# BreakOutBoard_Cyclone.net
KiCad netlist of a schematic drawn in Altium Designer
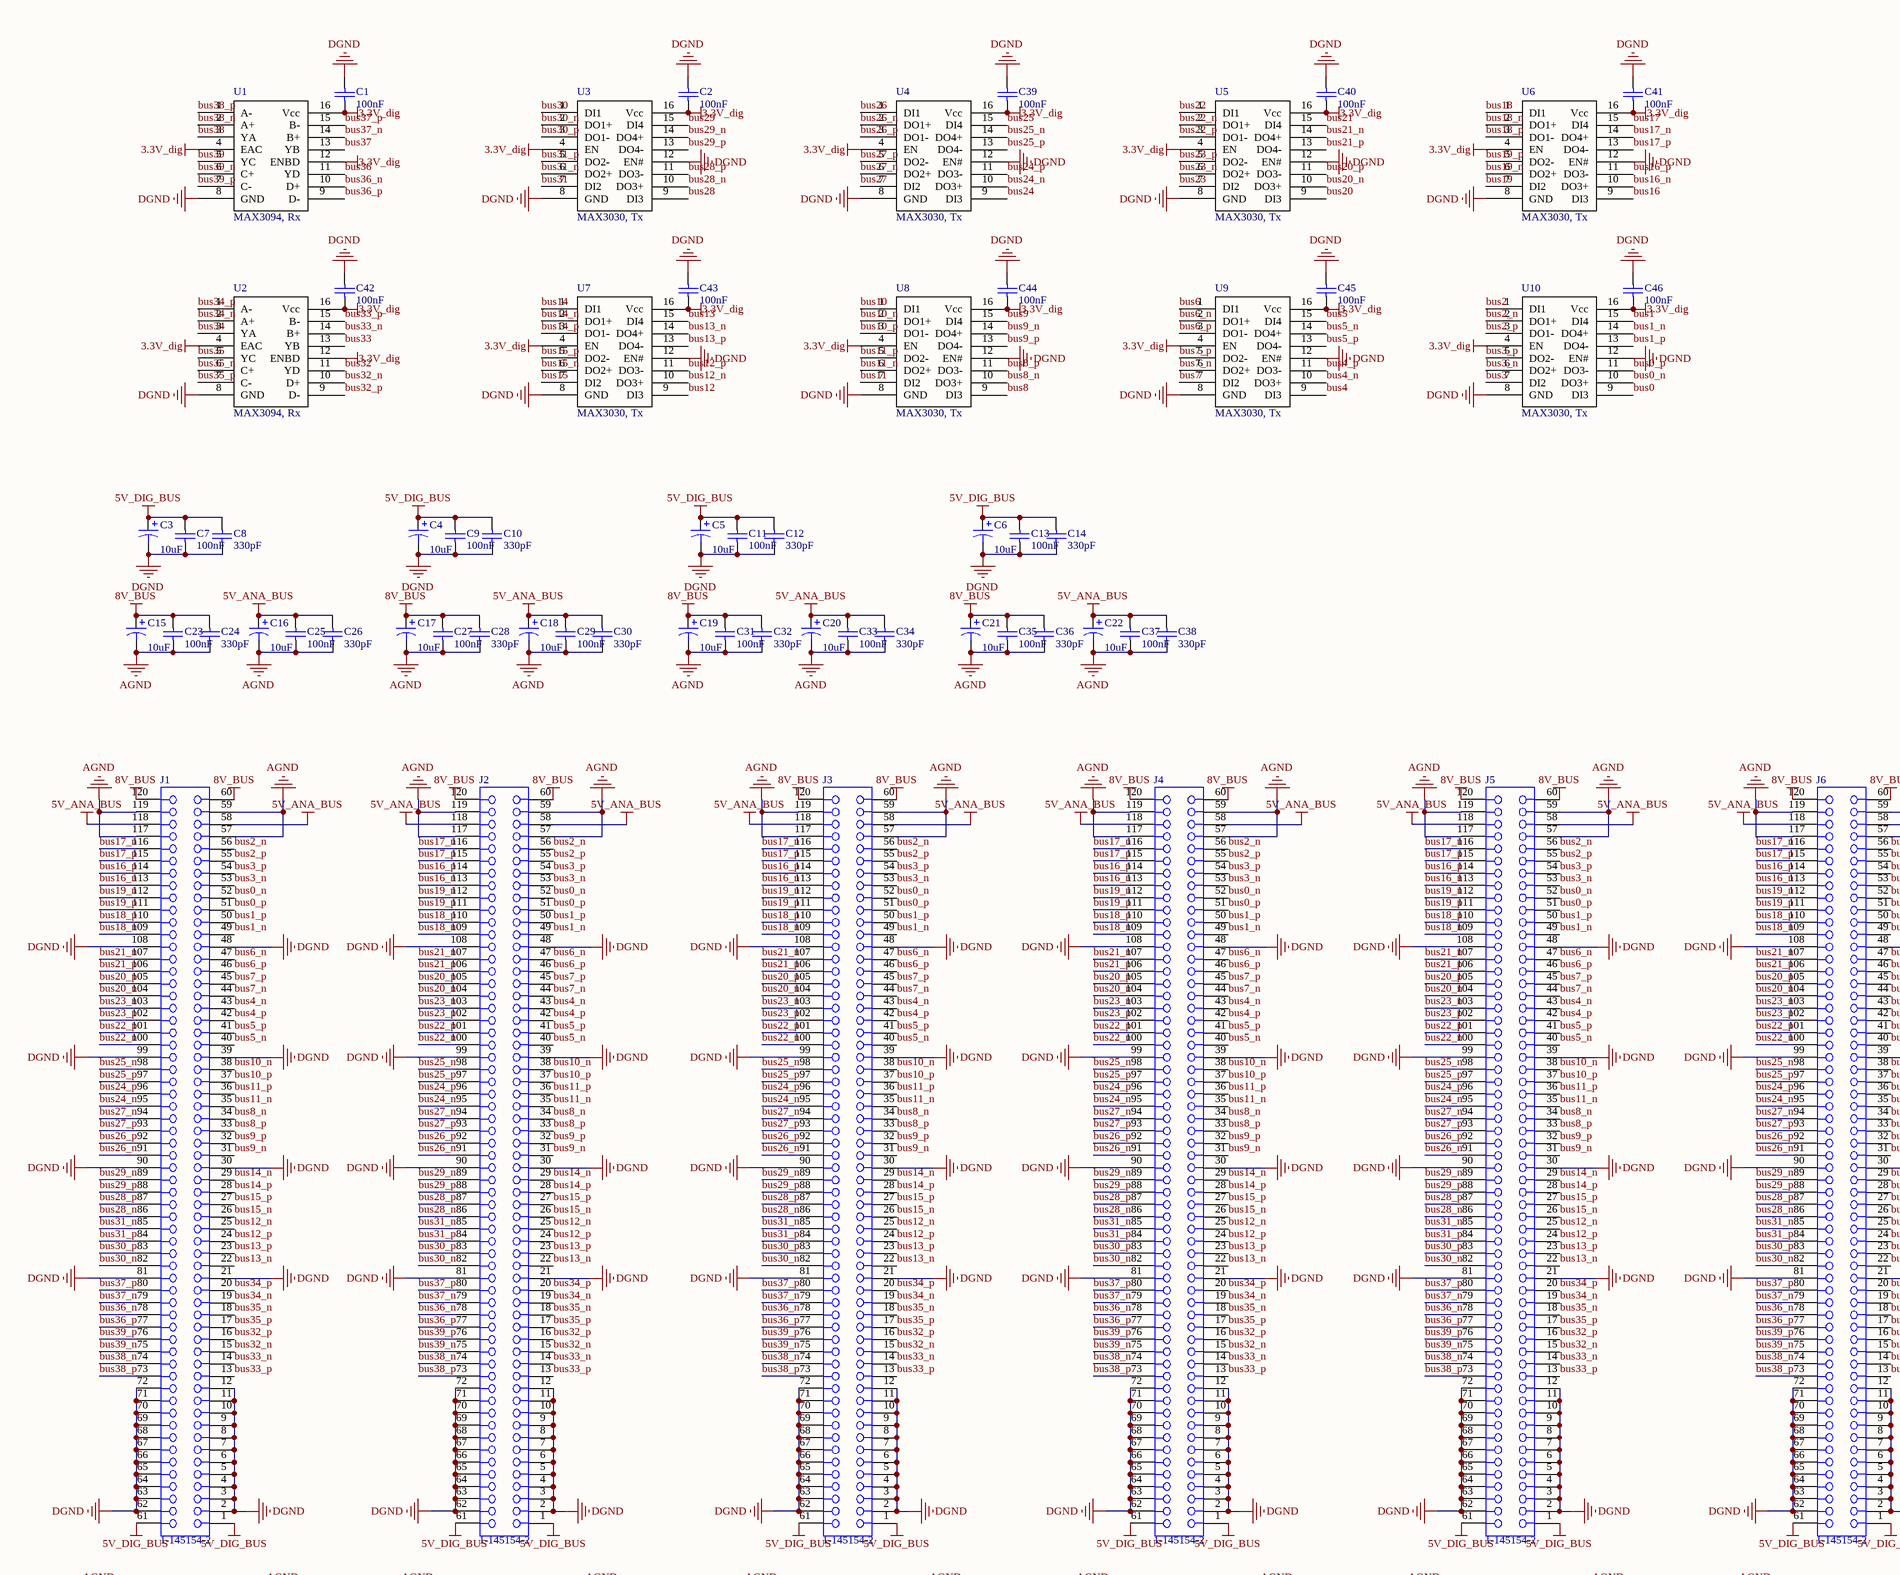
[diagram p0: BreakOutBoard_Cyclone.SchDoc, top left]
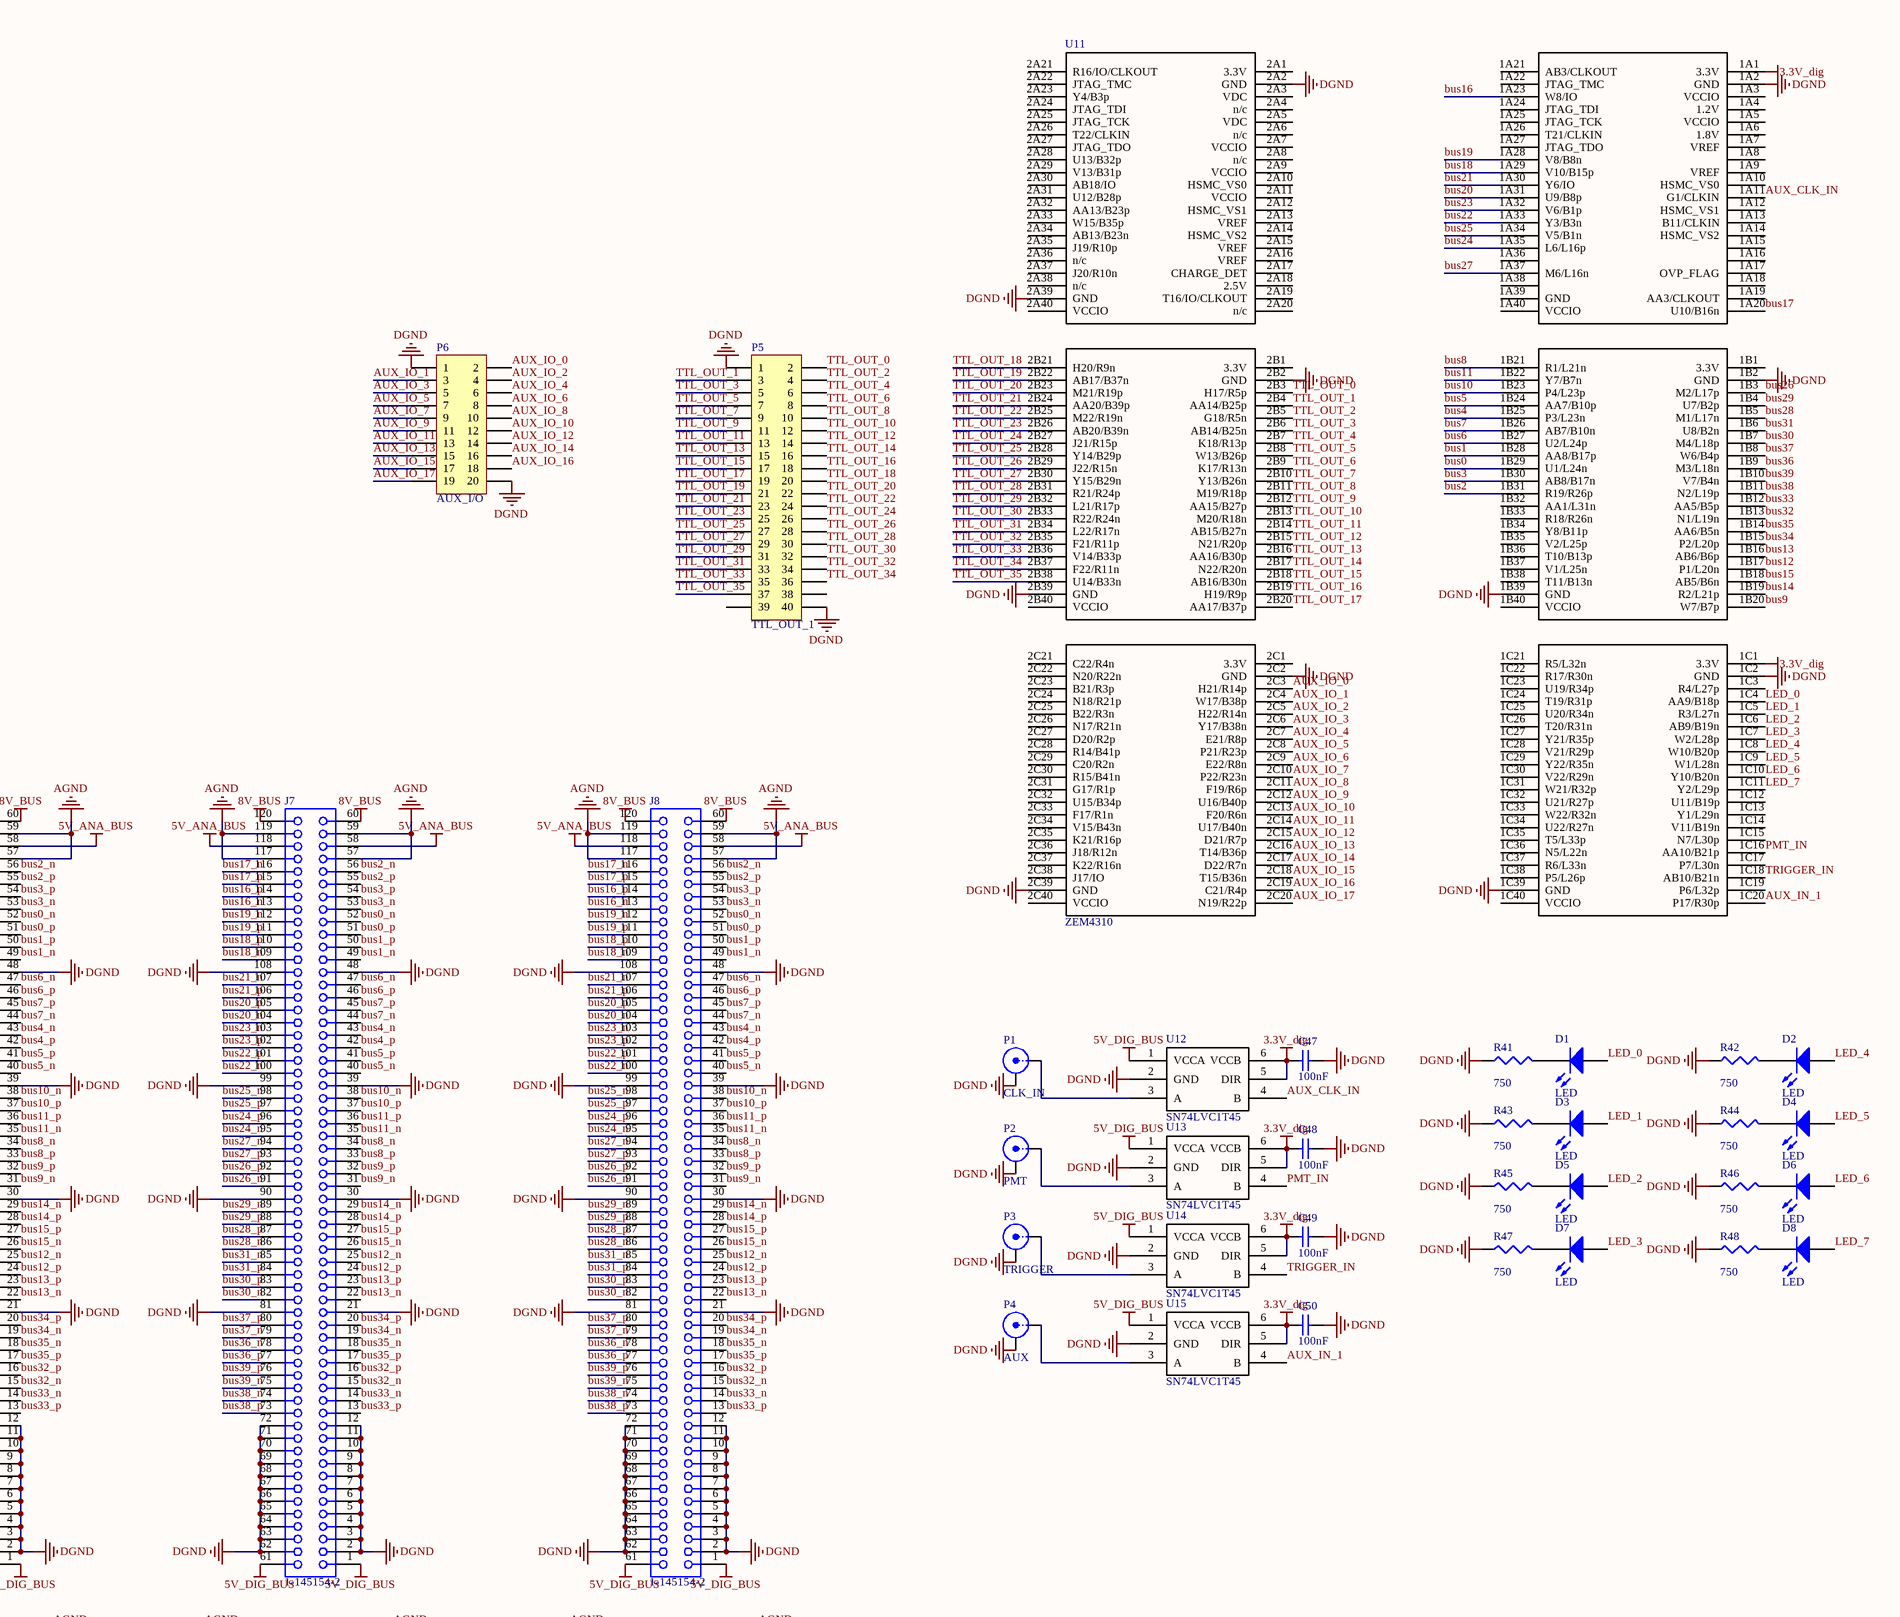
[diagram p1: BreakOutBoard_Cyclone.SchDoc, top right]
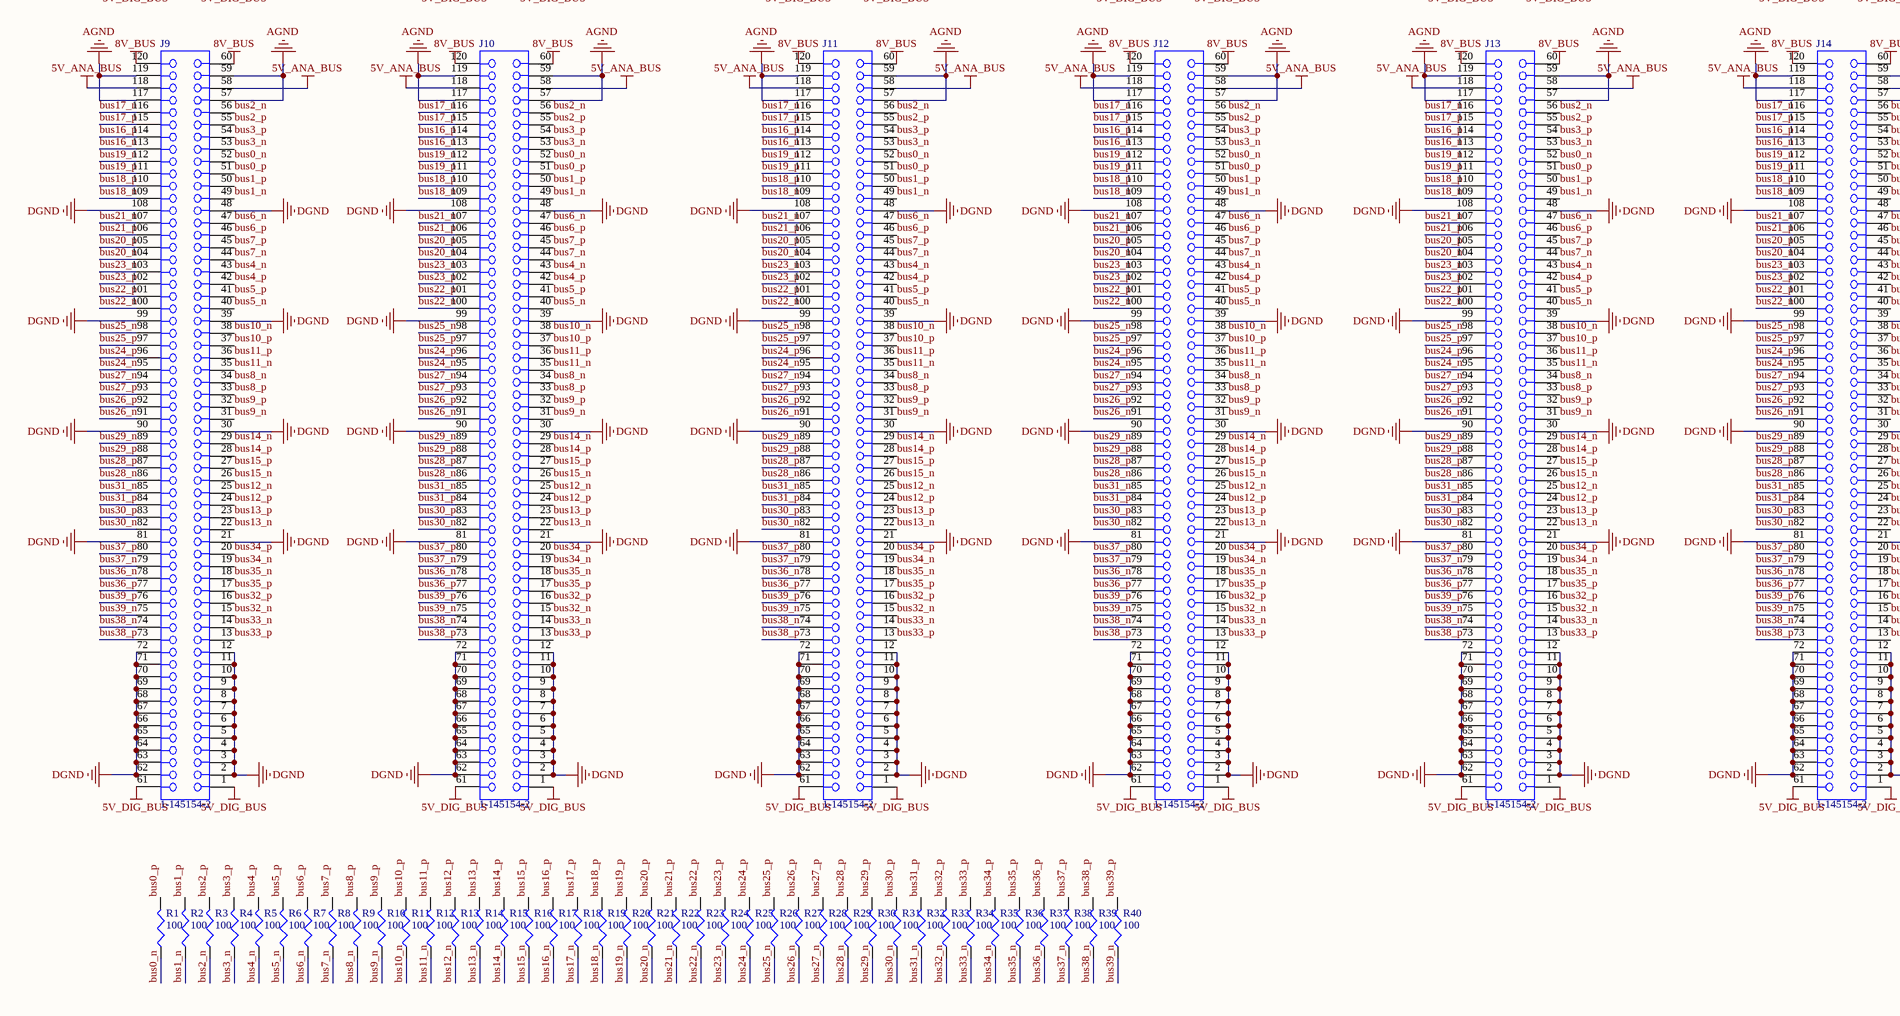
[diagram p2: BreakOutBoard_Cyclone.SchDoc, bottom left]
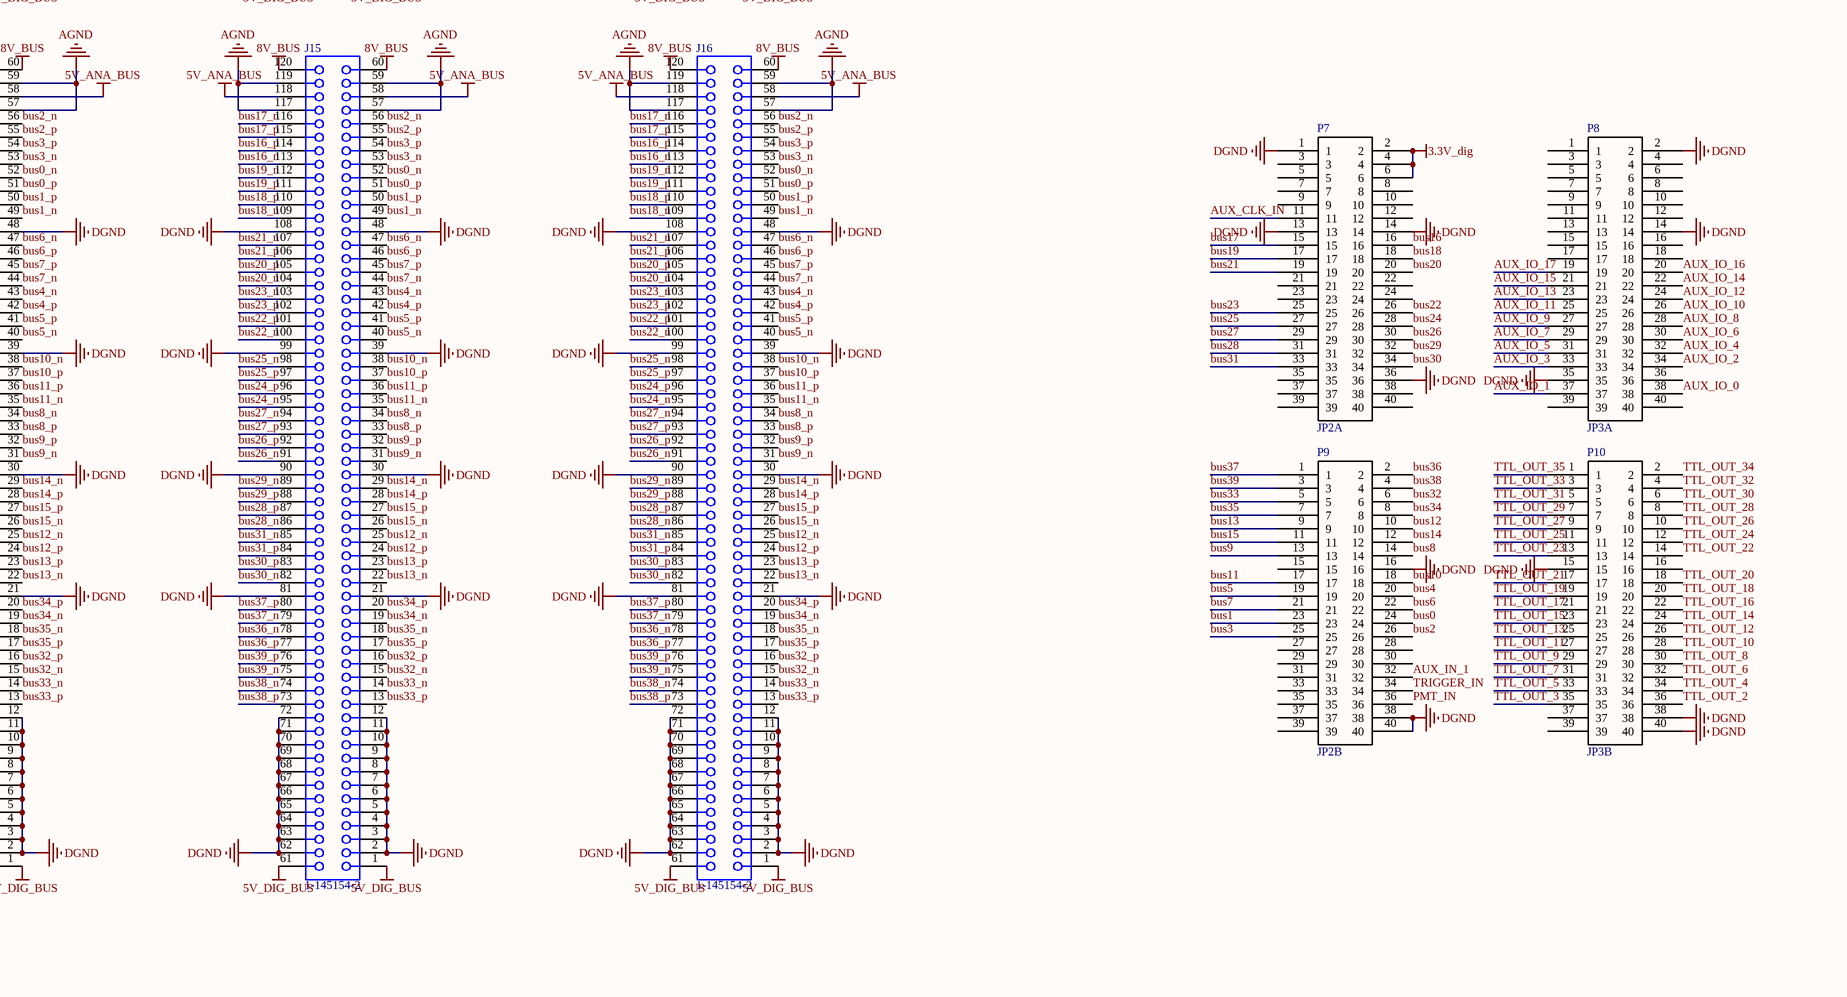
[diagram p3: BreakOutBoard_Cyclone.SchDoc, bottom right]

(export (version "E")
  (design (tool "Eeschema 10.0.6"))
  (components
    (comp (ref "C1")
      (value "100nF")
      (footprint "CAPC2012L")
      (description "Capacitor (Semiconductor SIM Model)")
      (fields (field (name "Comment") "Cap Semi") (field (name "PUBLISHER") "Altium Limited"))
      (libsource (lib "Miscellaneous Devices") (part "Cap Semi"))
    )
    (comp (ref "C2")
      (value "100nF")
      (footprint "CAPC2012L")
      (description "Capacitor (Semiconductor SIM Model)")
      (fields (field (name "Comment") "Cap Semi") (field (name "PUBLISHER") "Altium Limited"))
      (libsource (lib "Miscellaneous Devices") (part "Cap Semi"))
    )
    (comp (ref "C3")
      (value "10uF")
      (footprint "B")
      (description "Polarized Capacitor (Radial)")
      (fields
        (field (name "VOLTAGE") "16V")
        (field (name "Comment") "Cap Pol1")
        (field (name "PUBLISHER") "Altium Limited")
      )
      (libsource (lib "Miscellaneous Devices") (part "Cap Pol1"))
    )
    (comp (ref "C4")
      (value "10uF")
      (footprint "B")
      (description "Polarized Capacitor (Radial)")
      (fields
        (field (name "VOLTAGE") "16V")
        (field (name "Comment") "Cap Pol1")
        (field (name "PUBLISHER") "Altium Limited")
      )
      (libsource (lib "Miscellaneous Devices") (part "Cap Pol1"))
    )
    (comp (ref "C5")
      (value "10uF")
      (footprint "B")
      (description "Polarized Capacitor (Radial)")
      (fields
        (field (name "VOLTAGE") "16V")
        (field (name "Comment") "Cap Pol1")
        (field (name "PUBLISHER") "Altium Limited")
      )
      (libsource (lib "Miscellaneous Devices") (part "Cap Pol1"))
    )
    (comp (ref "C6")
      (value "10uF")
      (footprint "B")
      (description "Polarized Capacitor (Radial)")
      (fields
        (field (name "VOLTAGE") "16V")
        (field (name "Comment") "Cap Pol1")
        (field (name "PUBLISHER") "Altium Limited")
      )
      (libsource (lib "Miscellaneous Devices") (part "Cap Pol1"))
    )
    (comp (ref "C7")
      (value "100nF")
      (footprint "CAPC2012L")
      (description "Capacitor (Semiconductor SIM Model)")
      (fields (field (name "Comment") "Cap Semi") (field (name "PUBLISHER") "Altium Limited"))
      (libsource (lib "Miscellaneous Devices") (part "Cap Semi"))
    )
    (comp (ref "C8")
      (value "330pF")
      (footprint "CAPC2012L")
      (description "Capacitor (Semiconductor SIM Model)")
      (fields (field (name "Comment") "Cap Semi") (field (name "PUBLISHER") "Altium Limited"))
      (libsource (lib "Miscellaneous Devices") (part "Cap Semi"))
    )
    (comp (ref "C9")
      (value "100nF")
      (footprint "CAPC2012L")
      (description "Capacitor (Semiconductor SIM Model)")
      (fields (field (name "Comment") "Cap Semi") (field (name "PUBLISHER") "Altium Limited"))
      (libsource (lib "Miscellaneous Devices") (part "Cap Semi"))
    )
    (comp (ref "C10")
      (value "330pF")
      (footprint "CAPC2012L")
      (description "Capacitor (Semiconductor SIM Model)")
      (fields (field (name "Comment") "Cap Semi") (field (name "PUBLISHER") "Altium Limited"))
      (libsource (lib "Miscellaneous Devices") (part "Cap Semi"))
    )
    (comp (ref "C11")
      (value "100nF")
      (footprint "CAPC2012L")
      (description "Capacitor (Semiconductor SIM Model)")
      (fields (field (name "Comment") "Cap Semi") (field (name "PUBLISHER") "Altium Limited"))
      (libsource (lib "Miscellaneous Devices") (part "Cap Semi"))
    )
    (comp (ref "C12")
      (value "330pF")
      (footprint "CAPC2012L")
      (description "Capacitor (Semiconductor SIM Model)")
      (fields (field (name "Comment") "Cap Semi") (field (name "PUBLISHER") "Altium Limited"))
      (libsource (lib "Miscellaneous Devices") (part "Cap Semi"))
    )
    (comp (ref "C13")
      (value "100nF")
      (footprint "CAPC2012L")
      (description "Capacitor (Semiconductor SIM Model)")
      (fields (field (name "Comment") "Cap Semi") (field (name "PUBLISHER") "Altium Limited"))
      (libsource (lib "Miscellaneous Devices") (part "Cap Semi"))
    )
    (comp (ref "C14")
      (value "330pF")
      (footprint "CAPC2012L")
      (description "Capacitor (Semiconductor SIM Model)")
      (fields (field (name "Comment") "Cap Semi") (field (name "PUBLISHER") "Altium Limited"))
      (libsource (lib "Miscellaneous Devices") (part "Cap Semi"))
    )
    (comp (ref "C15")
      (value "10uF")
      (footprint "B")
      (description "Polarized Capacitor (Radial)")
      (fields
        (field (name "VOLTAGE") "16V")
        (field (name "Comment") "Cap Pol1")
        (field (name "PUBLISHER") "Altium Limited")
      )
      (libsource (lib "Miscellaneous Devices") (part "Cap Pol1"))
    )
    (comp (ref "C16")
      (value "10uF")
      (footprint "B")
      (description "Polarized Capacitor (Radial)")
      (fields
        (field (name "VOLTAGE") "16V")
        (field (name "Comment") "Cap Pol1")
        (field (name "PUBLISHER") "Altium Limited")
      )
      (libsource (lib "Miscellaneous Devices") (part "Cap Pol1"))
    )
    (comp (ref "C17")
      (value "10uF")
      (footprint "B")
      (description "Polarized Capacitor (Radial)")
      (fields
        (field (name "VOLTAGE") "16V")
        (field (name "Comment") "Cap Pol1")
        (field (name "PUBLISHER") "Altium Limited")
      )
      (libsource (lib "Miscellaneous Devices") (part "Cap Pol1"))
    )
    (comp (ref "C18")
      (value "10uF")
      (footprint "B")
      (description "Polarized Capacitor (Radial)")
      (fields
        (field (name "VOLTAGE") "16V")
        (field (name "Comment") "Cap Pol1")
        (field (name "PUBLISHER") "Altium Limited")
      )
      (libsource (lib "Miscellaneous Devices") (part "Cap Pol1"))
    )
    (comp (ref "C19")
      (value "10uF")
      (footprint "B")
      (description "Polarized Capacitor (Radial)")
      (fields
        (field (name "VOLTAGE") "16V")
        (field (name "Comment") "Cap Pol1")
        (field (name "PUBLISHER") "Altium Limited")
      )
      (libsource (lib "Miscellaneous Devices") (part "Cap Pol1"))
    )
    (comp (ref "C20")
      (value "10uF")
      (footprint "B")
      (description "Polarized Capacitor (Radial)")
      (fields
        (field (name "VOLTAGE") "16V")
        (field (name "Comment") "Cap Pol1")
        (field (name "PUBLISHER") "Altium Limited")
      )
      (libsource (lib "Miscellaneous Devices") (part "Cap Pol1"))
    )
    (comp (ref "C21")
      (value "10uF")
      (footprint "B")
      (description "Polarized Capacitor (Radial)")
      (fields
        (field (name "VOLTAGE") "16V")
        (field (name "Comment") "Cap Pol1")
        (field (name "PUBLISHER") "Altium Limited")
      )
      (libsource (lib "Miscellaneous Devices") (part "Cap Pol1"))
    )
    (comp (ref "C22")
      (value "10uF")
      (footprint "B")
      (description "Polarized Capacitor (Radial)")
      (fields
        (field (name "VOLTAGE") "16V")
        (field (name "Comment") "Cap Pol1")
        (field (name "PUBLISHER") "Altium Limited")
      )
      (libsource (lib "Miscellaneous Devices") (part "Cap Pol1"))
    )
    (comp (ref "C23")
      (value "100nF")
      (footprint "CAPC2012L")
      (description "Capacitor (Semiconductor SIM Model)")
      (fields (field (name "Comment") "Cap Semi") (field (name "PUBLISHER") "Altium Limited"))
      (libsource (lib "Miscellaneous Devices") (part "Cap Semi"))
    )
    (comp (ref "C24")
      (value "330pF")
      (footprint "CAPC2012L")
      (description "Capacitor (Semiconductor SIM Model)")
      (fields (field (name "Comment") "Cap Semi") (field (name "PUBLISHER") "Altium Limited"))
      (libsource (lib "Miscellaneous Devices") (part "Cap Semi"))
    )
    (comp (ref "C25")
      (value "100nF")
      (footprint "CAPC2012L")
      (description "Capacitor (Semiconductor SIM Model)")
      (fields (field (name "Comment") "Cap Semi") (field (name "PUBLISHER") "Altium Limited"))
      (libsource (lib "Miscellaneous Devices") (part "Cap Semi"))
    )
    (comp (ref "C26")
      (value "330pF")
      (footprint "CAPC2012L")
      (description "Capacitor (Semiconductor SIM Model)")
      (fields (field (name "Comment") "Cap Semi") (field (name "PUBLISHER") "Altium Limited"))
      (libsource (lib "Miscellaneous Devices") (part "Cap Semi"))
    )
    (comp (ref "C27")
      (value "100nF")
      (footprint "CAPC2012L")
      (description "Capacitor (Semiconductor SIM Model)")
      (fields (field (name "Comment") "Cap Semi") (field (name "PUBLISHER") "Altium Limited"))
      (libsource (lib "Miscellaneous Devices") (part "Cap Semi"))
    )
    (comp (ref "C28")
      (value "330pF")
      (footprint "CAPC2012L")
      (description "Capacitor (Semiconductor SIM Model)")
      (fields (field (name "Comment") "Cap Semi") (field (name "PUBLISHER") "Altium Limited"))
      (libsource (lib "Miscellaneous Devices") (part "Cap Semi"))
    )
    (comp (ref "C29")
      (value "100nF")
      (footprint "CAPC2012L")
      (description "Capacitor (Semiconductor SIM Model)")
      (fields (field (name "Comment") "Cap Semi") (field (name "PUBLISHER") "Altium Limited"))
      (libsource (lib "Miscellaneous Devices") (part "Cap Semi"))
    )
    (comp (ref "C30")
      (value "330pF")
      (footprint "CAPC2012L")
      (description "Capacitor (Semiconductor SIM Model)")
      (fields (field (name "Comment") "Cap Semi") (field (name "PUBLISHER") "Altium Limited"))
      (libsource (lib "Miscellaneous Devices") (part "Cap Semi"))
    )
    (comp (ref "C31")
      (value "100nF")
      (footprint "CAPC2012L")
      (description "Capacitor (Semiconductor SIM Model)")
      (fields (field (name "Comment") "Cap Semi") (field (name "PUBLISHER") "Altium Limited"))
      (libsource (lib "Miscellaneous Devices") (part "Cap Semi"))
    )
    (comp (ref "C32")
      (value "330pF")
      (footprint "CAPC2012L")
      (description "Capacitor (Semiconductor SIM Model)")
      (fields (field (name "Comment") "Cap Semi") (field (name "PUBLISHER") "Altium Limited"))
      (libsource (lib "Miscellaneous Devices") (part "Cap Semi"))
    )
    (comp (ref "C33")
      (value "100nF")
      (footprint "CAPC2012L")
      (description "Capacitor (Semiconductor SIM Model)")
      (fields (field (name "Comment") "Cap Semi") (field (name "PUBLISHER") "Altium Limited"))
      (libsource (lib "Miscellaneous Devices") (part "Cap Semi"))
    )
    (comp (ref "C34")
      (value "330pF")
      (footprint "CAPC2012L")
      (description "Capacitor (Semiconductor SIM Model)")
      (fields (field (name "Comment") "Cap Semi") (field (name "PUBLISHER") "Altium Limited"))
      (libsource (lib "Miscellaneous Devices") (part "Cap Semi"))
    )
    (comp (ref "C35")
      (value "100nF")
      (footprint "CAPC2012L")
      (description "Capacitor (Semiconductor SIM Model)")
      (fields (field (name "Comment") "Cap Semi") (field (name "PUBLISHER") "Altium Limited"))
      (libsource (lib "Miscellaneous Devices") (part "Cap Semi"))
    )
    (comp (ref "C36")
      (value "330pF")
      (footprint "CAPC2012L")
      (description "Capacitor (Semiconductor SIM Model)")
      (fields (field (name "Comment") "Cap Semi") (field (name "PUBLISHER") "Altium Limited"))
      (libsource (lib "Miscellaneous Devices") (part "Cap Semi"))
    )
    (comp (ref "C37")
      (value "100nF")
      (footprint "CAPC2012L")
      (description "Capacitor (Semiconductor SIM Model)")
      (fields (field (name "Comment") "Cap Semi") (field (name "PUBLISHER") "Altium Limited"))
      (libsource (lib "Miscellaneous Devices") (part "Cap Semi"))
    )
    (comp (ref "C38")
      (value "330pF")
      (footprint "CAPC2012L")
      (description "Capacitor (Semiconductor SIM Model)")
      (fields (field (name "Comment") "Cap Semi") (field (name "PUBLISHER") "Altium Limited"))
      (libsource (lib "Miscellaneous Devices") (part "Cap Semi"))
    )
    (comp (ref "C39")
      (value "100nF")
      (footprint "CAPC2012L")
      (description "Capacitor (Semiconductor SIM Model)")
      (fields (field (name "Comment") "Cap Semi") (field (name "PUBLISHER") "Altium Limited"))
      (libsource (lib "Miscellaneous Devices") (part "Cap Semi"))
    )
    (comp (ref "C40")
      (value "100nF")
      (footprint "CAPC2012L")
      (description "Capacitor (Semiconductor SIM Model)")
      (fields (field (name "Comment") "Cap Semi") (field (name "PUBLISHER") "Altium Limited"))
      (libsource (lib "Miscellaneous Devices") (part "Cap Semi"))
    )
    (comp (ref "C41")
      (value "100nF")
      (footprint "CAPC2012L")
      (description "Capacitor (Semiconductor SIM Model)")
      (fields (field (name "Comment") "Cap Semi") (field (name "PUBLISHER") "Altium Limited"))
      (libsource (lib "Miscellaneous Devices") (part "Cap Semi"))
    )
    (comp (ref "C42")
      (value "100nF")
      (footprint "CAPC2012L")
      (description "Capacitor (Semiconductor SIM Model)")
      (fields (field (name "Comment") "Cap Semi") (field (name "PUBLISHER") "Altium Limited"))
      (libsource (lib "Miscellaneous Devices") (part "Cap Semi"))
    )
    (comp (ref "C43")
      (value "100nF")
      (footprint "CAPC2012L")
      (description "Capacitor (Semiconductor SIM Model)")
      (fields (field (name "Comment") "Cap Semi") (field (name "PUBLISHER") "Altium Limited"))
      (libsource (lib "Miscellaneous Devices") (part "Cap Semi"))
    )
    (comp (ref "C44")
      (value "100nF")
      (footprint "CAPC2012L")
      (description "Capacitor (Semiconductor SIM Model)")
      (fields (field (name "Comment") "Cap Semi") (field (name "PUBLISHER") "Altium Limited"))
      (libsource (lib "Miscellaneous Devices") (part "Cap Semi"))
    )
    (comp (ref "C45")
      (value "100nF")
      (footprint "CAPC2012L")
      (description "Capacitor (Semiconductor SIM Model)")
      (fields (field (name "Comment") "Cap Semi") (field (name "PUBLISHER") "Altium Limited"))
      (libsource (lib "Miscellaneous Devices") (part "Cap Semi"))
    )
    (comp (ref "C46")
      (value "100nF")
      (footprint "CAPC2012L")
      (description "Capacitor (Semiconductor SIM Model)")
      (fields (field (name "Comment") "Cap Semi") (field (name "PUBLISHER") "Altium Limited"))
      (libsource (lib "Miscellaneous Devices") (part "Cap Semi"))
    )
    (comp (ref "C47")
      (value "100nF")
      (footprint "CAPC2012L")
      (description "Capacitor (Semiconductor SIM Model)")
      (fields (field (name "Comment") "Cap Semi") (field (name "PUBLISHER") "Altium Limited"))
      (libsource (lib "Miscellaneous Devices") (part "Cap Semi"))
    )
    (comp (ref "C48")
      (value "100nF")
      (footprint "CAPC2012L")
      (description "Capacitor (Semiconductor SIM Model)")
      (fields (field (name "Comment") "Cap Semi") (field (name "PUBLISHER") "Altium Limited"))
      (libsource (lib "Miscellaneous Devices") (part "Cap Semi"))
    )
    (comp (ref "C49")
      (value "100nF")
      (footprint "CAPC2012L")
      (description "Capacitor (Semiconductor SIM Model)")
      (fields (field (name "Comment") "Cap Semi") (field (name "PUBLISHER") "Altium Limited"))
      (libsource (lib "Miscellaneous Devices") (part "Cap Semi"))
    )
    (comp (ref "C50")
      (value "100nF")
      (footprint "CAPC2012L")
      (description "Capacitor (Semiconductor SIM Model)")
      (fields (field (name "Comment") "Cap Semi") (field (name "PUBLISHER") "Altium Limited"))
      (libsource (lib "Miscellaneous Devices") (part "Cap Semi"))
    )
    (comp (ref "D1")
      (value "LED")
      (footprint "RESC2012M")
      (description "Typical BLUE SiC LED")
      (fields (field (name "PUBLISHER") "Altium Limited"))
      (libsource (lib "Miscellaneous Devices") (part "LED3"))
    )
    (comp (ref "D2")
      (value "LED")
      (footprint "RESC2012M")
      (description "Typical BLUE SiC LED")
      (fields (field (name "PUBLISHER") "Altium Limited"))
      (libsource (lib "Miscellaneous Devices") (part "LED3"))
    )
    (comp (ref "D3")
      (value "LED")
      (footprint "RESC2012M")
      (description "Typical BLUE SiC LED")
      (fields (field (name "PUBLISHER") "Altium Limited"))
      (libsource (lib "Miscellaneous Devices") (part "LED3"))
    )
    (comp (ref "D4")
      (value "LED")
      (footprint "RESC2012M")
      (description "Typical BLUE SiC LED")
      (fields (field (name "PUBLISHER") "Altium Limited"))
      (libsource (lib "Miscellaneous Devices") (part "LED3"))
    )
    (comp (ref "D5")
      (value "LED")
      (footprint "RESC2012M")
      (description "Typical BLUE SiC LED")
      (fields (field (name "PUBLISHER") "Altium Limited"))
      (libsource (lib "Miscellaneous Devices") (part "LED3"))
    )
    (comp (ref "D6")
      (value "LED")
      (footprint "RESC2012M")
      (description "Typical BLUE SiC LED")
      (fields (field (name "PUBLISHER") "Altium Limited"))
      (libsource (lib "Miscellaneous Devices") (part "LED3"))
    )
    (comp (ref "D7")
      (value "LED")
      (footprint "RESC2012M")
      (description "Typical BLUE SiC LED")
      (fields (field (name "PUBLISHER") "Altium Limited"))
      (libsource (lib "Miscellaneous Devices") (part "LED3"))
    )
    (comp (ref "D8")
      (value "LED")
      (footprint "RESC2012M")
      (description "Typical BLUE SiC LED")
      (fields (field (name "PUBLISHER") "Altium Limited"))
      (libsource (lib "Miscellaneous Devices") (part "LED3"))
    )
    (comp (ref "J1")
      (value "1-145154-2")
      (footprint "1-145154-2")
      (description "Connector Assembly, 60 Dual Position, 1.27 [.050] Series, Standard Edge")
      (fields (field (name "VOLTAGE") "3.3V, 5V") (field (name "PUBLISHER") "Altium Limited"))
      (libsource (lib "AMP Card Edge 050 Series PCI") (part "1-145154-2"))
    )
    (comp (ref "J2")
      (value "1-145154-2")
      (footprint "1-145154-2")
      (description "Connector Assembly, 60 Dual Position, 1.27 [.050] Series, Standard Edge")
      (fields (field (name "VOLTAGE") "3.3V, 5V") (field (name "PUBLISHER") "Altium Limited"))
      (libsource (lib "AMP Card Edge 050 Series PCI") (part "1-145154-2"))
    )
    (comp (ref "J3")
      (value "1-145154-2")
      (footprint "1-145154-2")
      (description "Connector Assembly, 60 Dual Position, 1.27 [.050] Series, Standard Edge")
      (fields (field (name "VOLTAGE") "3.3V, 5V") (field (name "PUBLISHER") "Altium Limited"))
      (libsource (lib "AMP Card Edge 050 Series PCI") (part "1-145154-2"))
    )
    (comp (ref "J4")
      (value "1-145154-2")
      (footprint "1-145154-2")
      (description "Connector Assembly, 60 Dual Position, 1.27 [.050] Series, Standard Edge")
      (fields (field (name "VOLTAGE") "3.3V, 5V") (field (name "PUBLISHER") "Altium Limited"))
      (libsource (lib "AMP Card Edge 050 Series PCI") (part "1-145154-2"))
    )
    (comp (ref "J5")
      (value "1-145154-2")
      (footprint "1-145154-2")
      (description "Connector Assembly, 60 Dual Position, 1.27 [.050] Series, Standard Edge")
      (fields (field (name "VOLTAGE") "3.3V, 5V") (field (name "PUBLISHER") "Altium Limited"))
      (libsource (lib "AMP Card Edge 050 Series PCI") (part "1-145154-2"))
    )
    (comp (ref "J6")
      (value "1-145154-2")
      (footprint "1-145154-2")
      (description "Connector Assembly, 60 Dual Position, 1.27 [.050] Series, Standard Edge")
      (fields (field (name "VOLTAGE") "3.3V, 5V") (field (name "PUBLISHER") "Altium Limited"))
      (libsource (lib "AMP Card Edge 050 Series PCI") (part "1-145154-2"))
    )
    (comp (ref "J7")
      (value "1-145154-2")
      (footprint "1-145154-2")
      (description "Connector Assembly, 60 Dual Position, 1.27 [.050] Series, Standard Edge")
      (fields (field (name "VOLTAGE") "3.3V, 5V") (field (name "PUBLISHER") "Altium Limited"))
      (libsource (lib "AMP Card Edge 050 Series PCI") (part "1-145154-2"))
    )
    (comp (ref "J8")
      (value "1-145154-2")
      (footprint "1-145154-2")
      (description "Connector Assembly, 60 Dual Position, 1.27 [.050] Series, Standard Edge")
      (fields (field (name "VOLTAGE") "3.3V, 5V") (field (name "PUBLISHER") "Altium Limited"))
      (libsource (lib "AMP Card Edge 050 Series PCI") (part "1-145154-2"))
    )
    (comp (ref "J9")
      (value "1-145154-2")
      (footprint "1-145154-2")
      (description "Connector Assembly, 60 Dual Position, 1.27 [.050] Series, Standard Edge")
      (fields (field (name "VOLTAGE") "3.3V, 5V") (field (name "PUBLISHER") "Altium Limited"))
      (libsource (lib "AMP Card Edge 050 Series PCI") (part "1-145154-2"))
    )
    (comp (ref "J10")
      (value "1-145154-2")
      (footprint "1-145154-2")
      (description "Connector Assembly, 60 Dual Position, 1.27 [.050] Series, Standard Edge")
      (fields (field (name "VOLTAGE") "3.3V, 5V") (field (name "PUBLISHER") "Altium Limited"))
      (libsource (lib "AMP Card Edge 050 Series PCI") (part "1-145154-2"))
    )
    (comp (ref "J11")
      (value "1-145154-2")
      (footprint "1-145154-2")
      (description "Connector Assembly, 60 Dual Position, 1.27 [.050] Series, Standard Edge")
      (fields (field (name "VOLTAGE") "3.3V, 5V") (field (name "PUBLISHER") "Altium Limited"))
      (libsource (lib "AMP Card Edge 050 Series PCI") (part "1-145154-2"))
    )
    (comp (ref "J12")
      (value "1-145154-2")
      (footprint "1-145154-2")
      (description "Connector Assembly, 60 Dual Position, 1.27 [.050] Series, Standard Edge")
      (fields (field (name "VOLTAGE") "3.3V, 5V") (field (name "PUBLISHER") "Altium Limited"))
      (libsource (lib "AMP Card Edge 050 Series PCI") (part "1-145154-2"))
    )
    (comp (ref "J13")
      (value "1-145154-2")
      (footprint "1-145154-2")
      (description "Connector Assembly, 60 Dual Position, 1.27 [.050] Series, Standard Edge")
      (fields (field (name "VOLTAGE") "3.3V, 5V") (field (name "PUBLISHER") "Altium Limited"))
      (libsource (lib "AMP Card Edge 050 Series PCI") (part "1-145154-2"))
    )
    (comp (ref "J14")
      (value "1-145154-2")
      (footprint "1-145154-2")
      (description "Connector Assembly, 60 Dual Position, 1.27 [.050] Series, Standard Edge")
      (fields (field (name "VOLTAGE") "3.3V, 5V") (field (name "PUBLISHER") "Altium Limited"))
      (libsource (lib "AMP Card Edge 050 Series PCI") (part "1-145154-2"))
    )
    (comp (ref "J15")
      (value "1-145154-2")
      (footprint "1-145154-2")
      (description "Connector Assembly, 60 Dual Position, 1.27 [.050] Series, Standard Edge")
      (fields (field (name "VOLTAGE") "3.3V, 5V") (field (name "PUBLISHER") "Altium Limited"))
      (libsource (lib "AMP Card Edge 050 Series PCI") (part "1-145154-2"))
    )
    (comp (ref "J16")
      (value "1-145154-2")
      (footprint "1-145154-2")
      (description "Connector Assembly, 60 Dual Position, 1.27 [.050] Series, Standard Edge")
      (fields (field (name "VOLTAGE") "3.3V, 5V") (field (name "PUBLISHER") "Altium Limited"))
      (libsource (lib "AMP Card Edge 050 Series PCI") (part "1-145154-2"))
    )
    (comp (ref "P1")
      (value "CLK_IN")
      (footprint "BNC_RA CON")
      (description "BNC Elbow Connector")
      (fields (field (name "PUBLISHER") "Altium Limited"))
      (libsource (lib "Miscellaneous Connectors") (part "BNC"))
    )
    (comp (ref "P2")
      (value "PMT")
      (footprint "BNC_RA CON")
      (description "BNC Elbow Connector")
      (fields (field (name "PUBLISHER") "Altium Limited"))
      (libsource (lib "Miscellaneous Connectors") (part "BNC"))
    )
    (comp (ref "P3")
      (value "TRIGGER")
      (footprint "BNC_RA CON")
      (description "BNC Elbow Connector")
      (fields (field (name "PUBLISHER") "Altium Limited"))
      (libsource (lib "Miscellaneous Connectors") (part "BNC"))
    )
    (comp (ref "P4")
      (value "AUX")
      (footprint "BNC_RA CON")
      (description "BNC Elbow Connector")
      (fields (field (name "PUBLISHER") "Altium Limited"))
      (libsource (lib "Miscellaneous Connectors") (part "BNC"))
    )
    (comp (ref "P5")
      (value "TTL_OUT_1")
      (footprint "HDR2X20")
      (description "Header, 20-Pin, Dual row")
      (fields (field (name "PUBLISHER") "Altium Limited"))
      (libsource (lib "Miscellaneous Connectors") (part "Header 20X2"))
    )
    (comp (ref "P6")
      (value "AUX_I/O")
      (footprint "HDR2X10")
      (description "Header, 10-Pin, Dual row")
      (fields (field (name "PUBLISHER") "Altium Limited"))
      (libsource (lib "Miscellaneous Connectors") (part "Header 10X2"))
    )
    (comp (ref "P7")
      (value "JP2A")
      (footprint "connector_40pos_2mm")
      (description "2 mm connector 40 positions")
      (fields (field (name "PUBLISHER") "Altium Limited"))
      (libsource (lib "HH_chips") (part "CONN_40_2mm"))
    )
    (comp (ref "P8")
      (value "JP3A")
      (footprint "connector_40pos_2mm")
      (description "2 mm connector 40 positions")
      (fields (field (name "PUBLISHER") "Altium Limited"))
      (libsource (lib "HH_chips") (part "CONN_40_2mm"))
    )
    (comp (ref "P9")
      (value "JP2B")
      (footprint "connector_40pos_2mm")
      (description "2 mm connector 40 positions")
      (fields (field (name "PUBLISHER") "Altium Limited"))
      (libsource (lib "HH_chips") (part "CONN_40_2mm"))
    )
    (comp (ref "P10")
      (value "JP3B")
      (footprint "connector_40pos_2mm")
      (description "2 mm connector 40 positions")
      (fields (field (name "PUBLISHER") "Altium Limited"))
      (libsource (lib "HH_chips") (part "CONN_40_2mm"))
    )
    (comp (ref "R1")
      (value "100")
      (footprint "RESC3216L")
      (description "Resistor")
      (fields (field (name "PUBLISHER") "Altium Limited"))
      (libsource (lib "Miscellaneous Devices") (part "Res3"))
    )
    (comp (ref "R2")
      (value "100")
      (footprint "RESC3216L")
      (description "Resistor")
      (fields (field (name "PUBLISHER") "Altium Limited"))
      (libsource (lib "Miscellaneous Devices") (part "Res3"))
    )
    (comp (ref "R3")
      (value "100")
      (footprint "RESC3216L")
      (description "Resistor")
      (fields (field (name "PUBLISHER") "Altium Limited"))
      (libsource (lib "Miscellaneous Devices") (part "Res3"))
    )
    (comp (ref "R4")
      (value "100")
      (footprint "RESC3216L")
      (description "Resistor")
      (fields (field (name "PUBLISHER") "Altium Limited"))
      (libsource (lib "Miscellaneous Devices") (part "Res3"))
    )
    (comp (ref "R5")
      (value "100")
      (footprint "RESC3216L")
      (description "Resistor")
      (fields (field (name "PUBLISHER") "Altium Limited"))
      (libsource (lib "Miscellaneous Devices") (part "Res3"))
    )
    (comp (ref "R6")
      (value "100")
      (footprint "RESC3216L")
      (description "Resistor")
      (fields (field (name "PUBLISHER") "Altium Limited"))
      (libsource (lib "Miscellaneous Devices") (part "Res3"))
    )
    (comp (ref "R7")
      (value "100")
      (footprint "RESC3216L")
      (description "Resistor")
      (fields (field (name "PUBLISHER") "Altium Limited"))
      (libsource (lib "Miscellaneous Devices") (part "Res3"))
    )
    (comp (ref "R8")
      (value "100")
      (footprint "RESC3216L")
      (description "Resistor")
      (fields (field (name "PUBLISHER") "Altium Limited"))
      (libsource (lib "Miscellaneous Devices") (part "Res3"))
    )
    (comp (ref "R9")
      (value "100")
      (footprint "RESC3216L")
      (description "Resistor")
      (fields (field (name "PUBLISHER") "Altium Limited"))
      (libsource (lib "Miscellaneous Devices") (part "Res3"))
    )
    (comp (ref "R10")
      (value "100")
      (footprint "RESC3216L")
      (description "Resistor")
      (fields (field (name "PUBLISHER") "Altium Limited"))
      (libsource (lib "Miscellaneous Devices") (part "Res3"))
    )
    (comp (ref "R11")
      (value "100")
      (footprint "RESC3216L")
      (description "Resistor")
      (fields (field (name "PUBLISHER") "Altium Limited"))
      (libsource (lib "Miscellaneous Devices") (part "Res3"))
    )
    (comp (ref "R12")
      (value "100")
      (footprint "RESC3216L")
      (description "Resistor")
      (fields (field (name "PUBLISHER") "Altium Limited"))
      (libsource (lib "Miscellaneous Devices") (part "Res3"))
    )
    (comp (ref "R13")
      (value "100")
      (footprint "RESC3216L")
      (description "Resistor")
      (fields (field (name "PUBLISHER") "Altium Limited"))
      (libsource (lib "Miscellaneous Devices") (part "Res3"))
    )
    (comp (ref "R14")
      (value "100")
      (footprint "RESC3216L")
      (description "Resistor")
      (fields (field (name "PUBLISHER") "Altium Limited"))
      (libsource (lib "Miscellaneous Devices") (part "Res3"))
    )
    (comp (ref "R15")
      (value "100")
      (footprint "RESC3216L")
      (description "Resistor")
      (fields (field (name "PUBLISHER") "Altium Limited"))
      (libsource (lib "Miscellaneous Devices") (part "Res3"))
    )
    (comp (ref "R16")
      (value "100")
      (footprint "RESC3216L")
      (description "Resistor")
      (fields (field (name "PUBLISHER") "Altium Limited"))
      (libsource (lib "Miscellaneous Devices") (part "Res3"))
    )
    (comp (ref "R17")
      (value "100")
      (footprint "RESC3216L")
      (description "Resistor")
      (fields (field (name "PUBLISHER") "Altium Limited"))
      (libsource (lib "Miscellaneous Devices") (part "Res3"))
    )
    (comp (ref "R18")
      (value "100")
      (footprint "RESC3216L")
      (description "Resistor")
      (fields (field (name "PUBLISHER") "Altium Limited"))
      (libsource (lib "Miscellaneous Devices") (part "Res3"))
    )
    (comp (ref "R19")
      (value "100")
      (footprint "RESC3216L")
      (description "Resistor")
      (fields (field (name "PUBLISHER") "Altium Limited"))
      (libsource (lib "Miscellaneous Devices") (part "Res3"))
    )
    (comp (ref "R20")
      (value "100")
      (footprint "RESC3216L")
      (description "Resistor")
      (fields (field (name "PUBLISHER") "Altium Limited"))
      (libsource (lib "Miscellaneous Devices") (part "Res3"))
    )
    (comp (ref "R21")
      (value "100")
      (footprint "RESC3216L")
      (description "Resistor")
      (fields (field (name "PUBLISHER") "Altium Limited"))
      (libsource (lib "Miscellaneous Devices") (part "Res3"))
    )
    (comp (ref "R22")
      (value "100")
      (footprint "RESC3216L")
      (description "Resistor")
      (fields (field (name "PUBLISHER") "Altium Limited"))
      (libsource (lib "Miscellaneous Devices") (part "Res3"))
    )
    (comp (ref "R23")
      (value "100")
      (footprint "RESC3216L")
      (description "Resistor")
      (fields (field (name "PUBLISHER") "Altium Limited"))
      (libsource (lib "Miscellaneous Devices") (part "Res3"))
    )
    (comp (ref "R24")
      (value "100")
      (footprint "RESC3216L")
      (description "Resistor")
      (fields (field (name "PUBLISHER") "Altium Limited"))
      (libsource (lib "Miscellaneous Devices") (part "Res3"))
    )
    (comp (ref "R25")
      (value "100")
      (footprint "RESC3216L")
      (description "Resistor")
      (fields (field (name "PUBLISHER") "Altium Limited"))
      (libsource (lib "Miscellaneous Devices") (part "Res3"))
    )
    (comp (ref "R26")
      (value "100")
      (footprint "RESC3216L")
      (description "Resistor")
      (fields (field (name "PUBLISHER") "Altium Limited"))
      (libsource (lib "Miscellaneous Devices") (part "Res3"))
    )
    (comp (ref "R27")
      (value "100")
      (footprint "RESC3216L")
      (description "Resistor")
      (fields (field (name "PUBLISHER") "Altium Limited"))
      (libsource (lib "Miscellaneous Devices") (part "Res3"))
    )
    (comp (ref "R28")
      (value "100")
      (footprint "RESC3216L")
      (description "Resistor")
      (fields (field (name "PUBLISHER") "Altium Limited"))
      (libsource (lib "Miscellaneous Devices") (part "Res3"))
    )
    (comp (ref "R29")
      (value "100")
      (footprint "RESC3216L")
      (description "Resistor")
      (fields (field (name "PUBLISHER") "Altium Limited"))
      (libsource (lib "Miscellaneous Devices") (part "Res3"))
    )
    (comp (ref "R30")
      (value "100")
      (footprint "RESC3216L")
      (description "Resistor")
      (fields (field (name "PUBLISHER") "Altium Limited"))
      (libsource (lib "Miscellaneous Devices") (part "Res3"))
    )
    (comp (ref "R31")
      (value "100")
      (footprint "RESC3216L")
      (description "Resistor")
      (fields (field (name "PUBLISHER") "Altium Limited"))
      (libsource (lib "Miscellaneous Devices") (part "Res3"))
    )
    (comp (ref "R32")
      (value "100")
      (footprint "RESC3216L")
      (description "Resistor")
      (fields (field (name "PUBLISHER") "Altium Limited"))
      (libsource (lib "Miscellaneous Devices") (part "Res3"))
    )
    (comp (ref "R33")
      (value "100")
      (footprint "RESC3216L")
      (description "Resistor")
      (fields (field (name "PUBLISHER") "Altium Limited"))
      (libsource (lib "Miscellaneous Devices") (part "Res3"))
    )
    (comp (ref "R34")
      (value "100")
      (footprint "RESC3216L")
      (description "Resistor")
      (fields (field (name "PUBLISHER") "Altium Limited"))
      (libsource (lib "Miscellaneous Devices") (part "Res3"))
    )
    (comp (ref "R35")
      (value "100")
      (footprint "RESC3216L")
      (description "Resistor")
      (fields (field (name "PUBLISHER") "Altium Limited"))
      (libsource (lib "Miscellaneous Devices") (part "Res3"))
    )
    (comp (ref "R36")
      (value "100")
      (footprint "RESC3216L")
      (description "Resistor")
      (fields (field (name "PUBLISHER") "Altium Limited"))
      (libsource (lib "Miscellaneous Devices") (part "Res3"))
    )
    (comp (ref "R37")
      (value "100")
      (footprint "RESC3216L")
      (description "Resistor")
      (fields (field (name "PUBLISHER") "Altium Limited"))
      (libsource (lib "Miscellaneous Devices") (part "Res3"))
    )
    (comp (ref "R38")
      (value "100")
      (footprint "RESC3216L")
      (description "Resistor")
      (fields (field (name "PUBLISHER") "Altium Limited"))
      (libsource (lib "Miscellaneous Devices") (part "Res3"))
    )
    (comp (ref "R39")
      (value "100")
      (footprint "RESC3216L")
      (description "Resistor")
      (fields (field (name "PUBLISHER") "Altium Limited"))
      (libsource (lib "Miscellaneous Devices") (part "Res3"))
    )
    (comp (ref "R40")
      (value "100")
      (footprint "RESC3216L")
      (description "Resistor")
      (fields (field (name "PUBLISHER") "Altium Limited"))
      (libsource (lib "Miscellaneous Devices") (part "Res3"))
    )
    (comp (ref "R41")
      (value "750")
      (footprint "RESC2012M")
      (description "Resistor")
      (fields (field (name "Comment") "Res3") (field (name "PUBLISHER") "Altium Limited"))
      (libsource (lib "Miscellaneous Devices") (part "Res3"))
    )
    (comp (ref "R42")
      (value "750")
      (footprint "RESC2012M")
      (description "Resistor")
      (fields (field (name "Comment") "Res3") (field (name "PUBLISHER") "Altium Limited"))
      (libsource (lib "Miscellaneous Devices") (part "Res3"))
    )
    (comp (ref "R43")
      (value "750")
      (footprint "RESC2012M")
      (description "Resistor")
      (fields (field (name "Comment") "Res3") (field (name "PUBLISHER") "Altium Limited"))
      (libsource (lib "Miscellaneous Devices") (part "Res3"))
    )
    (comp (ref "R44")
      (value "750")
      (footprint "RESC2012M")
      (description "Resistor")
      (fields (field (name "Comment") "Res3") (field (name "PUBLISHER") "Altium Limited"))
      (libsource (lib "Miscellaneous Devices") (part "Res3"))
    )
    (comp (ref "R45")
      (value "750")
      (footprint "RESC2012M")
      (description "Resistor")
      (fields (field (name "Comment") "Res3") (field (name "PUBLISHER") "Altium Limited"))
      (libsource (lib "Miscellaneous Devices") (part "Res3"))
    )
    (comp (ref "R46")
      (value "750")
      (footprint "RESC2012M")
      (description "Resistor")
      (fields (field (name "Comment") "Res3") (field (name "PUBLISHER") "Altium Limited"))
      (libsource (lib "Miscellaneous Devices") (part "Res3"))
    )
    (comp (ref "R47")
      (value "750")
      (footprint "RESC2012M")
      (description "Resistor")
      (fields (field (name "Comment") "Res3") (field (name "PUBLISHER") "Altium Limited"))
      (libsource (lib "Miscellaneous Devices") (part "Res3"))
    )
    (comp (ref "R48")
      (value "750")
      (footprint "RESC2012M")
      (description "Resistor")
      (fields (field (name "Comment") "Res3") (field (name "PUBLISHER") "Altium Limited"))
      (libsource (lib "Miscellaneous Devices") (part "Res3"))
    )
    (comp (ref "U1")
      (value "MAX3094, Rx")
      (footprint "NSO16_N")
      (description "Differential Line Receivers")
      (libsource (lib "HH_chips") (part "MAX3094"))
    )
    (comp (ref "U2")
      (value "MAX3094, Rx")
      (footprint "NSO16_N")
      (description "Differential Line Receivers")
      (libsource (lib "HH_chips") (part "MAX3094"))
    )
    (comp (ref "U3")
      (value "MAX3030, Tx")
      (footprint "NSO16_N")
      (description "Differential Line Transmitter")
      (libsource (lib "HH_chips") (part "MAX3030"))
    )
    (comp (ref "U4")
      (value "MAX3030, Tx")
      (footprint "NSO16_N")
      (description "Differential Line Transmitter")
      (libsource (lib "HH_chips") (part "MAX3030"))
    )
    (comp (ref "U5")
      (value "MAX3030, Tx")
      (footprint "NSO16_N")
      (description "Differential Line Transmitter")
      (libsource (lib "HH_chips") (part "MAX3030"))
    )
    (comp (ref "U6")
      (value "MAX3030, Tx")
      (footprint "NSO16_N")
      (description "Differential Line Transmitter")
      (libsource (lib "HH_chips") (part "MAX3030"))
    )
    (comp (ref "U7")
      (value "MAX3030, Tx")
      (footprint "NSO16_N")
      (description "Differential Line Transmitter")
      (libsource (lib "HH_chips") (part "MAX3030"))
    )
    (comp (ref "U8")
      (value "MAX3030, Tx")
      (footprint "NSO16_N")
      (description "Differential Line Transmitter")
      (libsource (lib "HH_chips") (part "MAX3030"))
    )
    (comp (ref "U9")
      (value "MAX3030, Tx")
      (footprint "NSO16_N")
      (description "Differential Line Transmitter")
      (libsource (lib "HH_chips") (part "MAX3030"))
    )
    (comp (ref "U10")
      (value "MAX3030, Tx")
      (footprint "NSO16_N")
      (description "Differential Line Transmitter")
      (libsource (lib "HH_chips") (part "MAX3030"))
    )
    (comp (ref "U11")
      (value "ZEM4310")
      (footprint "ZEM4310")
      (description "ZEM4310 breakout module")
      (libsource (lib "HH_chips") (part "ZEM4310"))
    )
    (comp (ref "U12")
      (value "SN74LVC1T45")
      (footprint "SOT23-6")
      (description "Logic Translator (Bidirectional)")
      (libsource (lib "HH_chips") (part "SN74LVC1T45"))
    )
    (comp (ref "U13")
      (value "SN74LVC1T45")
      (footprint "SOT23-6")
      (description "Logic Translator (Bidirectional)")
      (libsource (lib "HH_chips") (part "SN74LVC1T45"))
    )
    (comp (ref "U14")
      (value "SN74LVC1T45")
      (footprint "SOT23-6")
      (description "Logic Translator (Bidirectional)")
      (libsource (lib "HH_chips") (part "SN74LVC1T45"))
    )
    (comp (ref "U15")
      (value "SN74LVC1T45")
      (footprint "SOT23-6")
      (description "Logic Translator (Bidirectional)")
      (libsource (lib "HH_chips") (part "SN74LVC1T45"))
    )
  )
  (nets
    (net (code "1") (name "/AUX_CLK_IN") (class "Default")
      (node (ref "P7") (pin "11") (pinfunction "11_11") (pintype "passive"))
      (node (ref "U11") (pin "1A11") (pinfunction "G1/CLKIN_1A11") (pintype "passive"))
      (node (ref "U12") (pin "4") (pinfunction "B_4") (pintype "passive"))
    )
    (net (code "2") (name "/AUX_IN_1") (class "Default")
      (node (ref "P9") (pin "32") (pinfunction "32_32") (pintype "passive"))
      (node (ref "U11") (pin "1C20") (pinfunction "P17/R30p_1C20") (pintype "passive"))
      (node (ref "U15") (pin "4") (pinfunction "B_4") (pintype "passive"))
    )
    (net (code "3") (name "/AUX_IO_0") (class "Default")
      (node (ref "P6") (pin "2") (pinfunction "2_2") (pintype "passive"))
      (node (ref "P8") (pin "38") (pinfunction "38_38") (pintype "passive"))
      (node (ref "U11") (pin "2C3") (pinfunction "H21/R14p_2C3") (pintype "passive"))
    )
    (net (code "4") (name "/AUX_IO_1") (class "Default")
      (node (ref "P6") (pin "3") (pinfunction "3_3") (pintype "passive"))
      (node (ref "P8") (pin "37") (pinfunction "37_37") (pintype "passive"))
      (node (ref "U11") (pin "2C4") (pinfunction "W17/B38p_2C4") (pintype "passive"))
    )
    (net (code "5") (name "/AUX_IO_2") (class "Default")
      (node (ref "P6") (pin "4") (pinfunction "4_4") (pintype "passive"))
      (node (ref "P8") (pin "34") (pinfunction "34_34") (pintype "passive"))
      (node (ref "U11") (pin "2C5") (pinfunction "H22/R14n_2C5") (pintype "passive"))
    )
    (net (code "6") (name "/AUX_IO_3") (class "Default")
      (node (ref "P6") (pin "5") (pinfunction "5_5") (pintype "passive"))
      (node (ref "P8") (pin "33") (pinfunction "33_33") (pintype "passive"))
      (node (ref "U11") (pin "2C6") (pinfunction "Y17/B38n_2C6") (pintype "passive"))
    )
    (net (code "7") (name "/AUX_IO_4") (class "Default")
      (node (ref "P6") (pin "6") (pinfunction "6_6") (pintype "passive"))
      (node (ref "P8") (pin "32") (pinfunction "32_32") (pintype "passive"))
      (node (ref "U11") (pin "2C7") (pinfunction "E21/R8p_2C7") (pintype "passive"))
    )
    (net (code "8") (name "/AUX_IO_5") (class "Default")
      (node (ref "P6") (pin "7") (pinfunction "7_7") (pintype "passive"))
      (node (ref "P8") (pin "31") (pinfunction "31_31") (pintype "passive"))
      (node (ref "U11") (pin "2C8") (pinfunction "P21/R23p_2C8") (pintype "passive"))
    )
    (net (code "9") (name "/AUX_IO_6") (class "Default")
      (node (ref "P6") (pin "8") (pinfunction "8_8") (pintype "passive"))
      (node (ref "P8") (pin "30") (pinfunction "30_30") (pintype "passive"))
      (node (ref "U11") (pin "2C9") (pinfunction "E22/R8n_2C9") (pintype "passive"))
    )
    (net (code "10") (name "/AUX_IO_7") (class "Default")
      (node (ref "P6") (pin "9") (pinfunction "9_9") (pintype "passive"))
      (node (ref "P8") (pin "29") (pinfunction "29_29") (pintype "passive"))
      (node (ref "U11") (pin "2C10") (pinfunction "P22/R23n_2C10") (pintype "passive"))
    )
    (net (code "11") (name "/AUX_IO_8") (class "Default")
      (node (ref "P6") (pin "10") (pinfunction "10_10") (pintype "passive"))
      (node (ref "P8") (pin "28") (pinfunction "28_28") (pintype "passive"))
      (node (ref "U11") (pin "2C11") (pinfunction "F19/R6p_2C11") (pintype "passive"))
    )
    (net (code "12") (name "/AUX_IO_9") (class "Default")
      (node (ref "P6") (pin "11") (pinfunction "11_11") (pintype "passive"))
      (node (ref "P8") (pin "27") (pinfunction "27_27") (pintype "passive"))
      (node (ref "U11") (pin "2C12") (pinfunction "U16/B40p_2C12") (pintype "passive"))
    )
    (net (code "13") (name "/AUX_IO_10") (class "Default")
      (node (ref "P6") (pin "12") (pinfunction "12_12") (pintype "passive"))
      (node (ref "P8") (pin "26") (pinfunction "26_26") (pintype "passive"))
      (node (ref "U11") (pin "2C13") (pinfunction "F20/R6n_2C13") (pintype "passive"))
    )
    (net (code "14") (name "/AUX_IO_11") (class "Default")
      (node (ref "P6") (pin "13") (pinfunction "13_13") (pintype "passive"))
      (node (ref "P8") (pin "25") (pinfunction "25_25") (pintype "passive"))
      (node (ref "U11") (pin "2C14") (pinfunction "U17/B40n_2C14") (pintype "passive"))
    )
    (net (code "15") (name "/AUX_IO_12") (class "Default")
      (node (ref "P6") (pin "14") (pinfunction "14_14") (pintype "passive"))
      (node (ref "P8") (pin "24") (pinfunction "24_24") (pintype "passive"))
      (node (ref "U11") (pin "2C15") (pinfunction "D21/R7p_2C15") (pintype "passive"))
    )
    (net (code "16") (name "/AUX_IO_13") (class "Default")
      (node (ref "P6") (pin "15") (pinfunction "15_15") (pintype "passive"))
      (node (ref "P8") (pin "23") (pinfunction "23_23") (pintype "passive"))
      (node (ref "U11") (pin "2C16") (pinfunction "T14/B36p_2C16") (pintype "passive"))
    )
    (net (code "17") (name "/AUX_IO_14") (class "Default")
      (node (ref "P6") (pin "16") (pinfunction "16_16") (pintype "passive"))
      (node (ref "P8") (pin "22") (pinfunction "22_22") (pintype "passive"))
      (node (ref "U11") (pin "2C17") (pinfunction "D22/R7n_2C17") (pintype "passive"))
    )
    (net (code "18") (name "/AUX_IO_15") (class "Default")
      (node (ref "P6") (pin "17") (pinfunction "17_17") (pintype "passive"))
      (node (ref "P8") (pin "21") (pinfunction "21_21") (pintype "passive"))
      (node (ref "U11") (pin "2C18") (pinfunction "T15/B36n_2C18") (pintype "passive"))
    )
    (net (code "19") (name "/AUX_IO_16") (class "Default")
      (node (ref "P6") (pin "18") (pinfunction "18_18") (pintype "passive"))
      (node (ref "P8") (pin "20") (pinfunction "20_20") (pintype "passive"))
      (node (ref "U11") (pin "2C19") (pinfunction "C21/R4p_2C19") (pintype "passive"))
    )
    (net (code "20") (name "/AUX_IO_17") (class "Default")
      (node (ref "P6") (pin "19") (pinfunction "19_19") (pintype "passive"))
      (node (ref "P8") (pin "19") (pinfunction "19_19") (pintype "passive"))
      (node (ref "U11") (pin "2C20") (pinfunction "N19/R22p_2C20") (pintype "passive"))
    )
    (net (code "21") (name "/LED_0") (class "Default")
      (node (ref "D1") (pin "1") (pinfunction "A_1") (pintype "passive"))
      (node (ref "U11") (pin "1C4") (pinfunction "AA9/B18p_1C4") (pintype "passive"))
    )
    (net (code "22") (name "/LED_1") (class "Default")
      (node (ref "D3") (pin "1") (pinfunction "A_1") (pintype "passive"))
      (node (ref "U11") (pin "1C5") (pinfunction "R3/L27n_1C5") (pintype "passive"))
    )
    (net (code "23") (name "/LED_2") (class "Default")
      (node (ref "D5") (pin "1") (pinfunction "A_1") (pintype "passive"))
      (node (ref "U11") (pin "1C6") (pinfunction "AB9/B19n_1C6") (pintype "passive"))
    )
    (net (code "24") (name "/LED_3") (class "Default")
      (node (ref "D7") (pin "1") (pinfunction "A_1") (pintype "passive"))
      (node (ref "U11") (pin "1C7") (pinfunction "W2/L28p_1C7") (pintype "passive"))
    )
    (net (code "25") (name "/LED_4") (class "Default")
      (node (ref "D2") (pin "1") (pinfunction "A_1") (pintype "passive"))
      (node (ref "U11") (pin "1C8") (pinfunction "W10/B20p_1C8") (pintype "passive"))
    )
    (net (code "26") (name "/LED_5") (class "Default")
      (node (ref "D4") (pin "1") (pinfunction "A_1") (pintype "passive"))
      (node (ref "U11") (pin "1C9") (pinfunction "W1/L28n_1C9") (pintype "passive"))
    )
    (net (code "27") (name "/LED_6") (class "Default")
      (node (ref "D6") (pin "1") (pinfunction "A_1") (pintype "passive"))
      (node (ref "U11") (pin "1C10") (pinfunction "Y10/B20n_1C10") (pintype "passive"))
    )
    (net (code "28") (name "/LED_7") (class "Default")
      (node (ref "D8") (pin "1") (pinfunction "A_1") (pintype "passive"))
      (node (ref "U11") (pin "1C11") (pinfunction "Y2/L29p_1C11") (pintype "passive"))
    )
    (net (code "29") (name "/PMT_IN") (class "Default")
      (node (ref "P9") (pin "36") (pinfunction "36_36") (pintype "passive"))
      (node (ref "U11") (pin "1C16") (pinfunction "AA10/B21p_1C16") (pintype "passive"))
      (node (ref "U13") (pin "4") (pinfunction "B_4") (pintype "passive"))
    )
    (net (code "30") (name "/TRIGGER_IN") (class "Default")
      (node (ref "P9") (pin "34") (pinfunction "34_34") (pintype "passive"))
      (node (ref "U11") (pin "1C18") (pinfunction "AB10/B21n_1C18") (pintype "passive"))
      (node (ref "U14") (pin "4") (pinfunction "B_4") (pintype "passive"))
    )
    (net (code "31") (name "/TTL_OUT_0") (class "Default")
      (node (ref "P5") (pin "2") (pinfunction "2_2") (pintype "passive"))
      (node (ref "U11") (pin "2B3") (pinfunction "H17/R5p_2B3") (pintype "passive"))
    )
    (net (code "32") (name "/TTL_OUT_1") (class "Default")
      (node (ref "P5") (pin "3") (pinfunction "3_3") (pintype "passive"))
      (node (ref "U11") (pin "2B4") (pinfunction "AA14/B25p_2B4") (pintype "passive"))
    )
    (net (code "33") (name "/TTL_OUT_2") (class "Default")
      (node (ref "P10") (pin "36") (pinfunction "36_36") (pintype "passive"))
      (node (ref "P5") (pin "4") (pinfunction "4_4") (pintype "passive"))
      (node (ref "U11") (pin "2B5") (pinfunction "G18/R5n_2B5") (pintype "passive"))
    )
    (net (code "34") (name "/TTL_OUT_3") (class "Default")
      (node (ref "P10") (pin "35") (pinfunction "35_35") (pintype "passive"))
      (node (ref "P5") (pin "5") (pinfunction "5_5") (pintype "passive"))
      (node (ref "U11") (pin "2B6") (pinfunction "AB14/B25n_2B6") (pintype "passive"))
    )
    (net (code "35") (name "/TTL_OUT_4") (class "Default")
      (node (ref "P10") (pin "34") (pinfunction "34_34") (pintype "passive"))
      (node (ref "P5") (pin "6") (pinfunction "6_6") (pintype "passive"))
      (node (ref "U11") (pin "2B7") (pinfunction "K18/R13p_2B7") (pintype "passive"))
    )
    (net (code "36") (name "/TTL_OUT_5") (class "Default")
      (node (ref "P10") (pin "33") (pinfunction "33_33") (pintype "passive"))
      (node (ref "P5") (pin "7") (pinfunction "7_7") (pintype "passive"))
      (node (ref "U11") (pin "2B8") (pinfunction "W13/B26p_2B8") (pintype "passive"))
    )
    (net (code "37") (name "/TTL_OUT_6") (class "Default")
      (node (ref "P10") (pin "32") (pinfunction "32_32") (pintype "passive"))
      (node (ref "P5") (pin "8") (pinfunction "8_8") (pintype "passive"))
      (node (ref "U11") (pin "2B9") (pinfunction "K17/R13n_2B9") (pintype "passive"))
    )
    (net (code "38") (name "/TTL_OUT_7") (class "Default")
      (node (ref "P10") (pin "31") (pinfunction "31_31") (pintype "passive"))
      (node (ref "P5") (pin "9") (pinfunction "9_9") (pintype "passive"))
      (node (ref "U11") (pin "2B10") (pinfunction "Y13/B26n_2B10") (pintype "passive"))
    )
    (net (code "39") (name "/TTL_OUT_8") (class "Default")
      (node (ref "P10") (pin "30") (pinfunction "30_30") (pintype "passive"))
      (node (ref "P5") (pin "10") (pinfunction "10_10") (pintype "passive"))
      (node (ref "U11") (pin "2B11") (pinfunction "M19/R18p_2B11") (pintype "passive"))
    )
    (net (code "40") (name "/TTL_OUT_9") (class "Default")
      (node (ref "P10") (pin "29") (pinfunction "29_29") (pintype "passive"))
      (node (ref "P5") (pin "11") (pinfunction "11_11") (pintype "passive"))
      (node (ref "U11") (pin "2B12") (pinfunction "AA15/B27p_2B12") (pintype "passive"))
    )
    (net (code "41") (name "/TTL_OUT_10") (class "Default")
      (node (ref "P10") (pin "28") (pinfunction "28_28") (pintype "passive"))
      (node (ref "P5") (pin "12") (pinfunction "12_12") (pintype "passive"))
      (node (ref "U11") (pin "2B13") (pinfunction "M20/R18n_2B13") (pintype "passive"))
    )
    (net (code "42") (name "/TTL_OUT_11") (class "Default")
      (node (ref "P10") (pin "27") (pinfunction "27_27") (pintype "passive"))
      (node (ref "P5") (pin "13") (pinfunction "13_13") (pintype "passive"))
      (node (ref "U11") (pin "2B14") (pinfunction "AB15/B27n_2B14") (pintype "passive"))
    )
    (net (code "43") (name "/TTL_OUT_12") (class "Default")
      (node (ref "P10") (pin "26") (pinfunction "26_26") (pintype "passive"))
      (node (ref "P5") (pin "14") (pinfunction "14_14") (pintype "passive"))
      (node (ref "U11") (pin "2B15") (pinfunction "N21/R20p_2B15") (pintype "passive"))
    )
    (net (code "44") (name "/TTL_OUT_13") (class "Default")
      (node (ref "P10") (pin "25") (pinfunction "25_25") (pintype "passive"))
      (node (ref "P5") (pin "15") (pinfunction "15_15") (pintype "passive"))
      (node (ref "U11") (pin "2B16") (pinfunction "AA16/B30p_2B16") (pintype "passive"))
    )
    (net (code "45") (name "/TTL_OUT_14") (class "Default")
      (node (ref "P10") (pin "24") (pinfunction "24_24") (pintype "passive"))
      (node (ref "P5") (pin "16") (pinfunction "16_16") (pintype "passive"))
      (node (ref "U11") (pin "2B17") (pinfunction "N22/R20n_2B17") (pintype "passive"))
    )
    (net (code "46") (name "/TTL_OUT_15") (class "Default")
      (node (ref "P10") (pin "23") (pinfunction "23_23") (pintype "passive"))
      (node (ref "P5") (pin "17") (pinfunction "17_17") (pintype "passive"))
      (node (ref "U11") (pin "2B18") (pinfunction "AB16/B30n_2B18") (pintype "passive"))
    )
    (net (code "47") (name "/TTL_OUT_16") (class "Default")
      (node (ref "P10") (pin "22") (pinfunction "22_22") (pintype "passive"))
      (node (ref "P5") (pin "18") (pinfunction "18_18") (pintype "passive"))
      (node (ref "U11") (pin "2B19") (pinfunction "H19/R9p_2B19") (pintype "passive"))
    )
    (net (code "48") (name "/TTL_OUT_17") (class "Default")
      (node (ref "P10") (pin "21") (pinfunction "21_21") (pintype "passive"))
      (node (ref "P5") (pin "19") (pinfunction "19_19") (pintype "passive"))
      (node (ref "U11") (pin "2B20") (pinfunction "AA17/B37p_2B20") (pintype "passive"))
    )
    (net (code "49") (name "/TTL_OUT_18") (class "Default")
      (node (ref "P10") (pin "20") (pinfunction "20_20") (pintype "passive"))
      (node (ref "P5") (pin "20") (pinfunction "20_20") (pintype "passive"))
      (node (ref "U11") (pin "2B21") (pinfunction "H20/R9n_2B21") (pintype "passive"))
    )
    (net (code "50") (name "/TTL_OUT_19") (class "Default")
      (node (ref "P10") (pin "19") (pinfunction "19_19") (pintype "passive"))
      (node (ref "P5") (pin "21") (pinfunction "21_21") (pintype "passive"))
      (node (ref "U11") (pin "2B22") (pinfunction "AB17/B37n_2B22") (pintype "passive"))
    )
    (net (code "51") (name "/TTL_OUT_20") (class "Default")
      (node (ref "P10") (pin "18") (pinfunction "18_18") (pintype "passive"))
      (node (ref "P5") (pin "22") (pinfunction "22_22") (pintype "passive"))
      (node (ref "U11") (pin "2B23") (pinfunction "M21/R19p_2B23") (pintype "passive"))
    )
    (net (code "52") (name "/TTL_OUT_21") (class "Default")
      (node (ref "P10") (pin "17") (pinfunction "17_17") (pintype "passive"))
      (node (ref "P5") (pin "23") (pinfunction "23_23") (pintype "passive"))
      (node (ref "U11") (pin "2B24") (pinfunction "AA20/B39p_2B24") (pintype "passive"))
    )
    (net (code "53") (name "/TTL_OUT_22") (class "Default")
      (node (ref "P10") (pin "14") (pinfunction "14_14") (pintype "passive"))
      (node (ref "P5") (pin "24") (pinfunction "24_24") (pintype "passive"))
      (node (ref "U11") (pin "2B25") (pinfunction "M22/R19n_2B25") (pintype "passive"))
    )
    (net (code "54") (name "/TTL_OUT_23") (class "Default")
      (node (ref "P10") (pin "13") (pinfunction "13_13") (pintype "passive"))
      (node (ref "P5") (pin "25") (pinfunction "25_25") (pintype "passive"))
      (node (ref "U11") (pin "2B26") (pinfunction "AB20/B39n_2B26") (pintype "passive"))
    )
    (net (code "55") (name "/TTL_OUT_24") (class "Default")
      (node (ref "P10") (pin "12") (pinfunction "12_12") (pintype "passive"))
      (node (ref "P5") (pin "26") (pinfunction "26_26") (pintype "passive"))
      (node (ref "U11") (pin "2B27") (pinfunction "J21/R15p_2B27") (pintype "passive"))
    )
    (net (code "56") (name "/TTL_OUT_25") (class "Default")
      (node (ref "P10") (pin "11") (pinfunction "11_11") (pintype "passive"))
      (node (ref "P5") (pin "27") (pinfunction "27_27") (pintype "passive"))
      (node (ref "U11") (pin "2B28") (pinfunction "Y14/B29p_2B28") (pintype "passive"))
    )
    (net (code "57") (name "/TTL_OUT_26") (class "Default")
      (node (ref "P10") (pin "10") (pinfunction "10_10") (pintype "passive"))
      (node (ref "P5") (pin "28") (pinfunction "28_28") (pintype "passive"))
      (node (ref "U11") (pin "2B29") (pinfunction "J22/R15n_2B29") (pintype "passive"))
    )
    (net (code "58") (name "/TTL_OUT_27") (class "Default")
      (node (ref "P10") (pin "9") (pinfunction "9_9") (pintype "passive"))
      (node (ref "P5") (pin "29") (pinfunction "29_29") (pintype "passive"))
      (node (ref "U11") (pin "2B30") (pinfunction "Y15/B29n_2B30") (pintype "passive"))
    )
    (net (code "59") (name "/TTL_OUT_28") (class "Default")
      (node (ref "P10") (pin "8") (pinfunction "8_8") (pintype "passive"))
      (node (ref "P5") (pin "30") (pinfunction "30_30") (pintype "passive"))
      (node (ref "U11") (pin "2B31") (pinfunction "R21/R24p_2B31") (pintype "passive"))
    )
    (net (code "60") (name "/TTL_OUT_29") (class "Default")
      (node (ref "P10") (pin "7") (pinfunction "7_7") (pintype "passive"))
      (node (ref "P5") (pin "31") (pinfunction "31_31") (pintype "passive"))
      (node (ref "U11") (pin "2B32") (pinfunction "L21/R17p_2B32") (pintype "passive"))
    )
    (net (code "61") (name "/TTL_OUT_30") (class "Default")
      (node (ref "P10") (pin "6") (pinfunction "6_6") (pintype "passive"))
      (node (ref "P5") (pin "32") (pinfunction "32_32") (pintype "passive"))
      (node (ref "U11") (pin "2B33") (pinfunction "R22/R24n_2B33") (pintype "passive"))
    )
    (net (code "62") (name "/TTL_OUT_31") (class "Default")
      (node (ref "P10") (pin "5") (pinfunction "5_5") (pintype "passive"))
      (node (ref "P5") (pin "33") (pinfunction "33_33") (pintype "passive"))
      (node (ref "U11") (pin "2B34") (pinfunction "L22/R17n_2B34") (pintype "passive"))
    )
    (net (code "63") (name "/TTL_OUT_32") (class "Default")
      (node (ref "P10") (pin "4") (pinfunction "4_4") (pintype "passive"))
      (node (ref "P5") (pin "34") (pinfunction "34_34") (pintype "passive"))
      (node (ref "U11") (pin "2B35") (pinfunction "F21/R11p_2B35") (pintype "passive"))
    )
    (net (code "64") (name "/TTL_OUT_33") (class "Default")
      (node (ref "P10") (pin "3") (pinfunction "3_3") (pintype "passive"))
      (node (ref "P5") (pin "35") (pinfunction "35_35") (pintype "passive"))
      (node (ref "U11") (pin "2B36") (pinfunction "V14/B33p_2B36") (pintype "passive"))
    )
    (net (code "65") (name "/TTL_OUT_34") (class "Default")
      (node (ref "P10") (pin "2") (pinfunction "2_2") (pintype "passive"))
      (node (ref "P5") (pin "36") (pinfunction "36_36") (pintype "passive"))
      (node (ref "U11") (pin "2B37") (pinfunction "F22/R11n_2B37") (pintype "passive"))
    )
    (net (code "66") (name "/TTL_OUT_35") (class "Default")
      (node (ref "P10") (pin "1") (pinfunction "1_1") (pintype "passive"))
      (node (ref "P5") (pin "37") (pinfunction "37_37") (pintype "passive"))
      (node (ref "U11") (pin "2B38") (pinfunction "U14/B33n_2B38") (pintype "passive"))
    )
    (net (code "67") (name "/bus0") (class "Default")
      (node (ref "P9") (pin "24") (pinfunction "24_24") (pintype "passive"))
      (node (ref "U10") (pin "9") (pinfunction "DI3_9") (pintype "passive"))
      (node (ref "U11") (pin "1B29") (pinfunction "U1/L24n_1B29") (pintype "passive"))
    )
    (net (code "68") (name "/bus0_n") (class "Default")
      (node (ref "J1") (pin "52") (pinfunction "A52_52") (pintype "passive"))
      (node (ref "J10") (pin "52") (pinfunction "A52_52") (pintype "passive"))
      (node (ref "J11") (pin "52") (pinfunction "A52_52") (pintype "passive"))
      (node (ref "J12") (pin "52") (pinfunction "A52_52") (pintype "passive"))
      (node (ref "J13") (pin "52") (pinfunction "A52_52") (pintype "passive"))
      (node (ref "J14") (pin "52") (pinfunction "A52_52") (pintype "passive"))
      (node (ref "J15") (pin "52") (pinfunction "A52_52") (pintype "passive"))
      (node (ref "J16") (pin "52") (pinfunction "A52_52") (pintype "passive"))
      (node (ref "J2") (pin "52") (pinfunction "A52_52") (pintype "passive"))
      (node (ref "J3") (pin "52") (pinfunction "A52_52") (pintype "passive"))
      (node (ref "J4") (pin "52") (pinfunction "A52_52") (pintype "passive"))
      (node (ref "J5") (pin "52") (pinfunction "A52_52") (pintype "passive"))
      (node (ref "J6") (pin "52") (pinfunction "A52_52") (pintype "passive"))
      (node (ref "J7") (pin "52") (pinfunction "A52_52") (pintype "passive"))
      (node (ref "J8") (pin "52") (pinfunction "A52_52") (pintype "passive"))
      (node (ref "J9") (pin "52") (pinfunction "A52_52") (pintype "passive"))
      (node (ref "R1") (pin "1") (pinfunction "1_1") (pintype "passive"))
      (node (ref "U10") (pin "10") (pinfunction "DO3+_10") (pintype "passive"))
    )
    (net (code "69") (name "/bus0_p") (class "Default")
      (node (ref "J1") (pin "51") (pinfunction "A51_51") (pintype "passive"))
      (node (ref "J10") (pin "51") (pinfunction "A51_51") (pintype "passive"))
      (node (ref "J11") (pin "51") (pinfunction "A51_51") (pintype "passive"))
      (node (ref "J12") (pin "51") (pinfunction "A51_51") (pintype "passive"))
      (node (ref "J13") (pin "51") (pinfunction "A51_51") (pintype "passive"))
      (node (ref "J14") (pin "51") (pinfunction "A51_51") (pintype "passive"))
      (node (ref "J15") (pin "51") (pinfunction "A51_51") (pintype "passive"))
      (node (ref "J16") (pin "51") (pinfunction "A51_51") (pintype "passive"))
      (node (ref "J2") (pin "51") (pinfunction "A51_51") (pintype "passive"))
      (node (ref "J3") (pin "51") (pinfunction "A51_51") (pintype "passive"))
      (node (ref "J4") (pin "51") (pinfunction "A51_51") (pintype "passive"))
      (node (ref "J5") (pin "51") (pinfunction "A51_51") (pintype "passive"))
      (node (ref "J6") (pin "51") (pinfunction "A51_51") (pintype "passive"))
      (node (ref "J7") (pin "51") (pinfunction "A51_51") (pintype "passive"))
      (node (ref "J8") (pin "51") (pinfunction "A51_51") (pintype "passive"))
      (node (ref "J9") (pin "51") (pinfunction "A51_51") (pintype "passive"))
      (node (ref "R1") (pin "2") (pinfunction "2_2") (pintype "passive"))
      (node (ref "U10") (pin "11") (pinfunction "DO3-_11") (pintype "passive"))
    )
    (net (code "70") (name "/bus1") (class "Default")
      (node (ref "P9") (pin "23") (pinfunction "23_23") (pintype "passive"))
      (node (ref "U10") (pin "15") (pinfunction "DI4_15") (pintype "passive"))
      (node (ref "U11") (pin "1B28") (pinfunction "AA8/B17p_1B28") (pintype "passive"))
    )
    (net (code "71") (name "/bus1_n") (class "Default")
      (node (ref "J1") (pin "49") (pinfunction "A49_49") (pintype "passive"))
      (node (ref "J10") (pin "49") (pinfunction "A49_49") (pintype "passive"))
      (node (ref "J11") (pin "49") (pinfunction "A49_49") (pintype "passive"))
      (node (ref "J12") (pin "49") (pinfunction "A49_49") (pintype "passive"))
      (node (ref "J13") (pin "49") (pinfunction "A49_49") (pintype "passive"))
      (node (ref "J14") (pin "49") (pinfunction "A49_49") (pintype "passive"))
      (node (ref "J15") (pin "49") (pinfunction "A49_49") (pintype "passive"))
      (node (ref "J16") (pin "49") (pinfunction "A49_49") (pintype "passive"))
      (node (ref "J2") (pin "49") (pinfunction "A49_49") (pintype "passive"))
      (node (ref "J3") (pin "49") (pinfunction "A49_49") (pintype "passive"))
      (node (ref "J4") (pin "49") (pinfunction "A49_49") (pintype "passive"))
      (node (ref "J5") (pin "49") (pinfunction "A49_49") (pintype "passive"))
      (node (ref "J6") (pin "49") (pinfunction "A49_49") (pintype "passive"))
      (node (ref "J7") (pin "49") (pinfunction "A49_49") (pintype "passive"))
      (node (ref "J8") (pin "49") (pinfunction "A49_49") (pintype "passive"))
      (node (ref "J9") (pin "49") (pinfunction "A49_49") (pintype "passive"))
      (node (ref "R2") (pin "1") (pinfunction "1_1") (pintype "passive"))
      (node (ref "U10") (pin "14") (pinfunction "DO4+_14") (pintype "passive"))
    )
    (net (code "72") (name "/bus1_p") (class "Default")
      (node (ref "J1") (pin "50") (pinfunction "A50_50") (pintype "passive"))
      (node (ref "J10") (pin "50") (pinfunction "A50_50") (pintype "passive"))
      (node (ref "J11") (pin "50") (pinfunction "A50_50") (pintype "passive"))
      (node (ref "J12") (pin "50") (pinfunction "A50_50") (pintype "passive"))
      (node (ref "J13") (pin "50") (pinfunction "A50_50") (pintype "passive"))
      (node (ref "J14") (pin "50") (pinfunction "A50_50") (pintype "passive"))
      (node (ref "J15") (pin "50") (pinfunction "A50_50") (pintype "passive"))
      (node (ref "J16") (pin "50") (pinfunction "A50_50") (pintype "passive"))
      (node (ref "J2") (pin "50") (pinfunction "A50_50") (pintype "passive"))
      (node (ref "J3") (pin "50") (pinfunction "A50_50") (pintype "passive"))
      (node (ref "J4") (pin "50") (pinfunction "A50_50") (pintype "passive"))
      (node (ref "J5") (pin "50") (pinfunction "A50_50") (pintype "passive"))
      (node (ref "J6") (pin "50") (pinfunction "A50_50") (pintype "passive"))
      (node (ref "J7") (pin "50") (pinfunction "A50_50") (pintype "passive"))
      (node (ref "J8") (pin "50") (pinfunction "A50_50") (pintype "passive"))
      (node (ref "J9") (pin "50") (pinfunction "A50_50") (pintype "passive"))
      (node (ref "R2") (pin "2") (pinfunction "2_2") (pintype "passive"))
      (node (ref "U10") (pin "13") (pinfunction "DO4-_13") (pintype "passive"))
    )
    (net (code "73") (name "/bus2") (class "Default")
      (node (ref "P9") (pin "26") (pinfunction "26_26") (pintype "passive"))
      (node (ref "U10") (pin "1") (pinfunction "DI1_1") (pintype "passive"))
      (node (ref "U11") (pin "1B31") (pinfunction "R19/R26p_1B31") (pintype "passive"))
    )
    (net (code "74") (name "/bus2_n") (class "Default")
      (node (ref "J1") (pin "56") (pinfunction "A56_56") (pintype "passive"))
      (node (ref "J10") (pin "56") (pinfunction "A56_56") (pintype "passive"))
      (node (ref "J11") (pin "56") (pinfunction "A56_56") (pintype "passive"))
      (node (ref "J12") (pin "56") (pinfunction "A56_56") (pintype "passive"))
      (node (ref "J13") (pin "56") (pinfunction "A56_56") (pintype "passive"))
      (node (ref "J14") (pin "56") (pinfunction "A56_56") (pintype "passive"))
      (node (ref "J15") (pin "56") (pinfunction "A56_56") (pintype "passive"))
      (node (ref "J16") (pin "56") (pinfunction "A56_56") (pintype "passive"))
      (node (ref "J2") (pin "56") (pinfunction "A56_56") (pintype "passive"))
      (node (ref "J3") (pin "56") (pinfunction "A56_56") (pintype "passive"))
      (node (ref "J4") (pin "56") (pinfunction "A56_56") (pintype "passive"))
      (node (ref "J5") (pin "56") (pinfunction "A56_56") (pintype "passive"))
      (node (ref "J6") (pin "56") (pinfunction "A56_56") (pintype "passive"))
      (node (ref "J7") (pin "56") (pinfunction "A56_56") (pintype "passive"))
      (node (ref "J8") (pin "56") (pinfunction "A56_56") (pintype "passive"))
      (node (ref "J9") (pin "56") (pinfunction "A56_56") (pintype "passive"))
      (node (ref "R3") (pin "1") (pinfunction "1_1") (pintype "passive"))
      (node (ref "U10") (pin "2") (pinfunction "DO1+_2") (pintype "passive"))
    )
    (net (code "75") (name "/bus2_p") (class "Default")
      (node (ref "J1") (pin "55") (pinfunction "A55_55") (pintype "passive"))
      (node (ref "J10") (pin "55") (pinfunction "A55_55") (pintype "passive"))
      (node (ref "J11") (pin "55") (pinfunction "A55_55") (pintype "passive"))
      (node (ref "J12") (pin "55") (pinfunction "A55_55") (pintype "passive"))
      (node (ref "J13") (pin "55") (pinfunction "A55_55") (pintype "passive"))
      (node (ref "J14") (pin "55") (pinfunction "A55_55") (pintype "passive"))
      (node (ref "J15") (pin "55") (pinfunction "A55_55") (pintype "passive"))
      (node (ref "J16") (pin "55") (pinfunction "A55_55") (pintype "passive"))
      (node (ref "J2") (pin "55") (pinfunction "A55_55") (pintype "passive"))
      (node (ref "J3") (pin "55") (pinfunction "A55_55") (pintype "passive"))
      (node (ref "J4") (pin "55") (pinfunction "A55_55") (pintype "passive"))
      (node (ref "J5") (pin "55") (pinfunction "A55_55") (pintype "passive"))
      (node (ref "J6") (pin "55") (pinfunction "A55_55") (pintype "passive"))
      (node (ref "J7") (pin "55") (pinfunction "A55_55") (pintype "passive"))
      (node (ref "J8") (pin "55") (pinfunction "A55_55") (pintype "passive"))
      (node (ref "J9") (pin "55") (pinfunction "A55_55") (pintype "passive"))
      (node (ref "R3") (pin "2") (pinfunction "2_2") (pintype "passive"))
      (node (ref "U10") (pin "3") (pinfunction "DO1-_3") (pintype "passive"))
    )
    (net (code "76") (name "/bus3") (class "Default")
      (node (ref "P9") (pin "25") (pinfunction "25_25") (pintype "passive"))
      (node (ref "U10") (pin "7") (pinfunction "DI2_7") (pintype "passive"))
      (node (ref "U11") (pin "1B30") (pinfunction "AB8/B17n_1B30") (pintype "passive"))
    )
    (net (code "77") (name "/bus3_n") (class "Default")
      (node (ref "J1") (pin "53") (pinfunction "A53_53") (pintype "passive"))
      (node (ref "J10") (pin "53") (pinfunction "A53_53") (pintype "passive"))
      (node (ref "J11") (pin "53") (pinfunction "A53_53") (pintype "passive"))
      (node (ref "J12") (pin "53") (pinfunction "A53_53") (pintype "passive"))
      (node (ref "J13") (pin "53") (pinfunction "A53_53") (pintype "passive"))
      (node (ref "J14") (pin "53") (pinfunction "A53_53") (pintype "passive"))
      (node (ref "J15") (pin "53") (pinfunction "A53_53") (pintype "passive"))
      (node (ref "J16") (pin "53") (pinfunction "A53_53") (pintype "passive"))
      (node (ref "J2") (pin "53") (pinfunction "A53_53") (pintype "passive"))
      (node (ref "J3") (pin "53") (pinfunction "A53_53") (pintype "passive"))
      (node (ref "J4") (pin "53") (pinfunction "A53_53") (pintype "passive"))
      (node (ref "J5") (pin "53") (pinfunction "A53_53") (pintype "passive"))
      (node (ref "J6") (pin "53") (pinfunction "A53_53") (pintype "passive"))
      (node (ref "J7") (pin "53") (pinfunction "A53_53") (pintype "passive"))
      (node (ref "J8") (pin "53") (pinfunction "A53_53") (pintype "passive"))
      (node (ref "J9") (pin "53") (pinfunction "A53_53") (pintype "passive"))
      (node (ref "R4") (pin "1") (pinfunction "1_1") (pintype "passive"))
      (node (ref "U10") (pin "6") (pinfunction "DO2+_6") (pintype "passive"))
    )
    (net (code "78") (name "/bus3_p") (class "Default")
      (node (ref "J1") (pin "54") (pinfunction "A54_54") (pintype "passive"))
      (node (ref "J10") (pin "54") (pinfunction "A54_54") (pintype "passive"))
      (node (ref "J11") (pin "54") (pinfunction "A54_54") (pintype "passive"))
      (node (ref "J12") (pin "54") (pinfunction "A54_54") (pintype "passive"))
      (node (ref "J13") (pin "54") (pinfunction "A54_54") (pintype "passive"))
      (node (ref "J14") (pin "54") (pinfunction "A54_54") (pintype "passive"))
      (node (ref "J15") (pin "54") (pinfunction "A54_54") (pintype "passive"))
      (node (ref "J16") (pin "54") (pinfunction "A54_54") (pintype "passive"))
      (node (ref "J2") (pin "54") (pinfunction "A54_54") (pintype "passive"))
      (node (ref "J3") (pin "54") (pinfunction "A54_54") (pintype "passive"))
      (node (ref "J4") (pin "54") (pinfunction "A54_54") (pintype "passive"))
      (node (ref "J5") (pin "54") (pinfunction "A54_54") (pintype "passive"))
      (node (ref "J6") (pin "54") (pinfunction "A54_54") (pintype "passive"))
      (node (ref "J7") (pin "54") (pinfunction "A54_54") (pintype "passive"))
      (node (ref "J8") (pin "54") (pinfunction "A54_54") (pintype "passive"))
      (node (ref "J9") (pin "54") (pinfunction "A54_54") (pintype "passive"))
      (node (ref "R4") (pin "2") (pinfunction "2_2") (pintype "passive"))
      (node (ref "U10") (pin "5") (pinfunction "DO2-_5") (pintype "passive"))
    )
    (net (code "79") (name "/bus4") (class "Default")
      (node (ref "P9") (pin "20") (pinfunction "20_20") (pintype "passive"))
      (node (ref "U11") (pin "1B25") (pinfunction "P3/L23n_1B25") (pintype "passive"))
      (node (ref "U9") (pin "9") (pinfunction "DI3_9") (pintype "passive"))
    )
    (net (code "80") (name "/bus4_n") (class "Default")
      (node (ref "J1") (pin "43") (pinfunction "A43_43") (pintype "passive"))
      (node (ref "J10") (pin "43") (pinfunction "A43_43") (pintype "passive"))
      (node (ref "J11") (pin "43") (pinfunction "A43_43") (pintype "passive"))
      (node (ref "J12") (pin "43") (pinfunction "A43_43") (pintype "passive"))
      (node (ref "J13") (pin "43") (pinfunction "A43_43") (pintype "passive"))
      (node (ref "J14") (pin "43") (pinfunction "A43_43") (pintype "passive"))
      (node (ref "J15") (pin "43") (pinfunction "A43_43") (pintype "passive"))
      (node (ref "J16") (pin "43") (pinfunction "A43_43") (pintype "passive"))
      (node (ref "J2") (pin "43") (pinfunction "A43_43") (pintype "passive"))
      (node (ref "J3") (pin "43") (pinfunction "A43_43") (pintype "passive"))
      (node (ref "J4") (pin "43") (pinfunction "A43_43") (pintype "passive"))
      (node (ref "J5") (pin "43") (pinfunction "A43_43") (pintype "passive"))
      (node (ref "J6") (pin "43") (pinfunction "A43_43") (pintype "passive"))
      (node (ref "J7") (pin "43") (pinfunction "A43_43") (pintype "passive"))
      (node (ref "J8") (pin "43") (pinfunction "A43_43") (pintype "passive"))
      (node (ref "J9") (pin "43") (pinfunction "A43_43") (pintype "passive"))
      (node (ref "R5") (pin "1") (pinfunction "1_1") (pintype "passive"))
      (node (ref "U9") (pin "10") (pinfunction "DO3+_10") (pintype "passive"))
    )
    (net (code "81") (name "/bus4_p") (class "Default")
      (node (ref "J1") (pin "42") (pinfunction "A42_42") (pintype "passive"))
      (node (ref "J10") (pin "42") (pinfunction "A42_42") (pintype "passive"))
      (node (ref "J11") (pin "42") (pinfunction "A42_42") (pintype "passive"))
      (node (ref "J12") (pin "42") (pinfunction "A42_42") (pintype "passive"))
      (node (ref "J13") (pin "42") (pinfunction "A42_42") (pintype "passive"))
      (node (ref "J14") (pin "42") (pinfunction "A42_42") (pintype "passive"))
      (node (ref "J15") (pin "42") (pinfunction "A42_42") (pintype "passive"))
      (node (ref "J16") (pin "42") (pinfunction "A42_42") (pintype "passive"))
      (node (ref "J2") (pin "42") (pinfunction "A42_42") (pintype "passive"))
      (node (ref "J3") (pin "42") (pinfunction "A42_42") (pintype "passive"))
      (node (ref "J4") (pin "42") (pinfunction "A42_42") (pintype "passive"))
      (node (ref "J5") (pin "42") (pinfunction "A42_42") (pintype "passive"))
      (node (ref "J6") (pin "42") (pinfunction "A42_42") (pintype "passive"))
      (node (ref "J7") (pin "42") (pinfunction "A42_42") (pintype "passive"))
      (node (ref "J8") (pin "42") (pinfunction "A42_42") (pintype "passive"))
      (node (ref "J9") (pin "42") (pinfunction "A42_42") (pintype "passive"))
      (node (ref "R5") (pin "2") (pinfunction "2_2") (pintype "passive"))
      (node (ref "U9") (pin "11") (pinfunction "DO3-_11") (pintype "passive"))
    )
    (net (code "82") (name "/bus5") (class "Default")
      (node (ref "P9") (pin "19") (pinfunction "19_19") (pintype "passive"))
      (node (ref "U11") (pin "1B24") (pinfunction "AA7/B10p_1B24") (pintype "passive"))
      (node (ref "U9") (pin "15") (pinfunction "DI4_15") (pintype "passive"))
    )
    (net (code "83") (name "/bus5_n") (class "Default")
      (node (ref "J1") (pin "40") (pinfunction "A40_40") (pintype "passive"))
      (node (ref "J10") (pin "40") (pinfunction "A40_40") (pintype "passive"))
      (node (ref "J11") (pin "40") (pinfunction "A40_40") (pintype "passive"))
      (node (ref "J12") (pin "40") (pinfunction "A40_40") (pintype "passive"))
      (node (ref "J13") (pin "40") (pinfunction "A40_40") (pintype "passive"))
      (node (ref "J14") (pin "40") (pinfunction "A40_40") (pintype "passive"))
      (node (ref "J15") (pin "40") (pinfunction "A40_40") (pintype "passive"))
      (node (ref "J16") (pin "40") (pinfunction "A40_40") (pintype "passive"))
      (node (ref "J2") (pin "40") (pinfunction "A40_40") (pintype "passive"))
      (node (ref "J3") (pin "40") (pinfunction "A40_40") (pintype "passive"))
      (node (ref "J4") (pin "40") (pinfunction "A40_40") (pintype "passive"))
      (node (ref "J5") (pin "40") (pinfunction "A40_40") (pintype "passive"))
      (node (ref "J6") (pin "40") (pinfunction "A40_40") (pintype "passive"))
      (node (ref "J7") (pin "40") (pinfunction "A40_40") (pintype "passive"))
      (node (ref "J8") (pin "40") (pinfunction "A40_40") (pintype "passive"))
      (node (ref "J9") (pin "40") (pinfunction "A40_40") (pintype "passive"))
      (node (ref "R6") (pin "1") (pinfunction "1_1") (pintype "passive"))
      (node (ref "U9") (pin "14") (pinfunction "DO4+_14") (pintype "passive"))
    )
    (net (code "84") (name "/bus5_p") (class "Default")
      (node (ref "J1") (pin "41") (pinfunction "A41_41") (pintype "passive"))
      (node (ref "J10") (pin "41") (pinfunction "A41_41") (pintype "passive"))
      (node (ref "J11") (pin "41") (pinfunction "A41_41") (pintype "passive"))
      (node (ref "J12") (pin "41") (pinfunction "A41_41") (pintype "passive"))
      (node (ref "J13") (pin "41") (pinfunction "A41_41") (pintype "passive"))
      (node (ref "J14") (pin "41") (pinfunction "A41_41") (pintype "passive"))
      (node (ref "J15") (pin "41") (pinfunction "A41_41") (pintype "passive"))
      (node (ref "J16") (pin "41") (pinfunction "A41_41") (pintype "passive"))
      (node (ref "J2") (pin "41") (pinfunction "A41_41") (pintype "passive"))
      (node (ref "J3") (pin "41") (pinfunction "A41_41") (pintype "passive"))
      (node (ref "J4") (pin "41") (pinfunction "A41_41") (pintype "passive"))
      (node (ref "J5") (pin "41") (pinfunction "A41_41") (pintype "passive"))
      (node (ref "J6") (pin "41") (pinfunction "A41_41") (pintype "passive"))
      (node (ref "J7") (pin "41") (pinfunction "A41_41") (pintype "passive"))
      (node (ref "J8") (pin "41") (pinfunction "A41_41") (pintype "passive"))
      (node (ref "J9") (pin "41") (pinfunction "A41_41") (pintype "passive"))
      (node (ref "R6") (pin "2") (pinfunction "2_2") (pintype "passive"))
      (node (ref "U9") (pin "13") (pinfunction "DO4-_13") (pintype "passive"))
    )
    (net (code "85") (name "/bus6") (class "Default")
      (node (ref "P9") (pin "22") (pinfunction "22_22") (pintype "passive"))
      (node (ref "U11") (pin "1B27") (pinfunction "U2/L24p_1B27") (pintype "passive"))
      (node (ref "U9") (pin "1") (pinfunction "DI1_1") (pintype "passive"))
    )
    (net (code "86") (name "/bus6_n") (class "Default")
      (node (ref "J1") (pin "47") (pinfunction "A47_47") (pintype "passive"))
      (node (ref "J10") (pin "47") (pinfunction "A47_47") (pintype "passive"))
      (node (ref "J11") (pin "47") (pinfunction "A47_47") (pintype "passive"))
      (node (ref "J12") (pin "47") (pinfunction "A47_47") (pintype "passive"))
      (node (ref "J13") (pin "47") (pinfunction "A47_47") (pintype "passive"))
      (node (ref "J14") (pin "47") (pinfunction "A47_47") (pintype "passive"))
      (node (ref "J15") (pin "47") (pinfunction "A47_47") (pintype "passive"))
      (node (ref "J16") (pin "47") (pinfunction "A47_47") (pintype "passive"))
      (node (ref "J2") (pin "47") (pinfunction "A47_47") (pintype "passive"))
      (node (ref "J3") (pin "47") (pinfunction "A47_47") (pintype "passive"))
      (node (ref "J4") (pin "47") (pinfunction "A47_47") (pintype "passive"))
      (node (ref "J5") (pin "47") (pinfunction "A47_47") (pintype "passive"))
      (node (ref "J6") (pin "47") (pinfunction "A47_47") (pintype "passive"))
      (node (ref "J7") (pin "47") (pinfunction "A47_47") (pintype "passive"))
      (node (ref "J8") (pin "47") (pinfunction "A47_47") (pintype "passive"))
      (node (ref "J9") (pin "47") (pinfunction "A47_47") (pintype "passive"))
      (node (ref "R7") (pin "1") (pinfunction "1_1") (pintype "passive"))
      (node (ref "U9") (pin "2") (pinfunction "DO1+_2") (pintype "passive"))
    )
    (net (code "87") (name "/bus6_p") (class "Default")
      (node (ref "J1") (pin "46") (pinfunction "A46_46") (pintype "passive"))
      (node (ref "J10") (pin "46") (pinfunction "A46_46") (pintype "passive"))
      (node (ref "J11") (pin "46") (pinfunction "A46_46") (pintype "passive"))
      (node (ref "J12") (pin "46") (pinfunction "A46_46") (pintype "passive"))
      (node (ref "J13") (pin "46") (pinfunction "A46_46") (pintype "passive"))
      (node (ref "J14") (pin "46") (pinfunction "A46_46") (pintype "passive"))
      (node (ref "J15") (pin "46") (pinfunction "A46_46") (pintype "passive"))
      (node (ref "J16") (pin "46") (pinfunction "A46_46") (pintype "passive"))
      (node (ref "J2") (pin "46") (pinfunction "A46_46") (pintype "passive"))
      (node (ref "J3") (pin "46") (pinfunction "A46_46") (pintype "passive"))
      (node (ref "J4") (pin "46") (pinfunction "A46_46") (pintype "passive"))
      (node (ref "J5") (pin "46") (pinfunction "A46_46") (pintype "passive"))
      (node (ref "J6") (pin "46") (pinfunction "A46_46") (pintype "passive"))
      (node (ref "J7") (pin "46") (pinfunction "A46_46") (pintype "passive"))
      (node (ref "J8") (pin "46") (pinfunction "A46_46") (pintype "passive"))
      (node (ref "J9") (pin "46") (pinfunction "A46_46") (pintype "passive"))
      (node (ref "R7") (pin "2") (pinfunction "2_2") (pintype "passive"))
      (node (ref "U9") (pin "3") (pinfunction "DO1-_3") (pintype "passive"))
    )
    (net (code "88") (name "/bus7") (class "Default")
      (node (ref "P9") (pin "21") (pinfunction "21_21") (pintype "passive"))
      (node (ref "U11") (pin "1B26") (pinfunction "AB7/B10n_1B26") (pintype "passive"))
      (node (ref "U9") (pin "7") (pinfunction "DI2_7") (pintype "passive"))
    )
    (net (code "89") (name "/bus7_n") (class "Default")
      (node (ref "J1") (pin "44") (pinfunction "A44_44") (pintype "passive"))
      (node (ref "J10") (pin "44") (pinfunction "A44_44") (pintype "passive"))
      (node (ref "J11") (pin "44") (pinfunction "A44_44") (pintype "passive"))
      (node (ref "J12") (pin "44") (pinfunction "A44_44") (pintype "passive"))
      (node (ref "J13") (pin "44") (pinfunction "A44_44") (pintype "passive"))
      (node (ref "J14") (pin "44") (pinfunction "A44_44") (pintype "passive"))
      (node (ref "J15") (pin "44") (pinfunction "A44_44") (pintype "passive"))
      (node (ref "J16") (pin "44") (pinfunction "A44_44") (pintype "passive"))
      (node (ref "J2") (pin "44") (pinfunction "A44_44") (pintype "passive"))
      (node (ref "J3") (pin "44") (pinfunction "A44_44") (pintype "passive"))
      (node (ref "J4") (pin "44") (pinfunction "A44_44") (pintype "passive"))
      (node (ref "J5") (pin "44") (pinfunction "A44_44") (pintype "passive"))
      (node (ref "J6") (pin "44") (pinfunction "A44_44") (pintype "passive"))
      (node (ref "J7") (pin "44") (pinfunction "A44_44") (pintype "passive"))
      (node (ref "J8") (pin "44") (pinfunction "A44_44") (pintype "passive"))
      (node (ref "J9") (pin "44") (pinfunction "A44_44") (pintype "passive"))
      (node (ref "R8") (pin "1") (pinfunction "1_1") (pintype "passive"))
      (node (ref "U9") (pin "6") (pinfunction "DO2+_6") (pintype "passive"))
    )
    (net (code "90") (name "/bus7_p") (class "Default")
      (node (ref "J1") (pin "45") (pinfunction "A45_45") (pintype "passive"))
      (node (ref "J10") (pin "45") (pinfunction "A45_45") (pintype "passive"))
      (node (ref "J11") (pin "45") (pinfunction "A45_45") (pintype "passive"))
      (node (ref "J12") (pin "45") (pinfunction "A45_45") (pintype "passive"))
      (node (ref "J13") (pin "45") (pinfunction "A45_45") (pintype "passive"))
      (node (ref "J14") (pin "45") (pinfunction "A45_45") (pintype "passive"))
      (node (ref "J15") (pin "45") (pinfunction "A45_45") (pintype "passive"))
      (node (ref "J16") (pin "45") (pinfunction "A45_45") (pintype "passive"))
      (node (ref "J2") (pin "45") (pinfunction "A45_45") (pintype "passive"))
      (node (ref "J3") (pin "45") (pinfunction "A45_45") (pintype "passive"))
      (node (ref "J4") (pin "45") (pinfunction "A45_45") (pintype "passive"))
      (node (ref "J5") (pin "45") (pinfunction "A45_45") (pintype "passive"))
      (node (ref "J6") (pin "45") (pinfunction "A45_45") (pintype "passive"))
      (node (ref "J7") (pin "45") (pinfunction "A45_45") (pintype "passive"))
      (node (ref "J8") (pin "45") (pinfunction "A45_45") (pintype "passive"))
      (node (ref "J9") (pin "45") (pinfunction "A45_45") (pintype "passive"))
      (node (ref "R8") (pin "2") (pinfunction "2_2") (pintype "passive"))
      (node (ref "U9") (pin "5") (pinfunction "DO2-_5") (pintype "passive"))
    )
    (net (code "91") (name "/bus8") (class "Default")
      (node (ref "P9") (pin "14") (pinfunction "14_14") (pintype "passive"))
      (node (ref "U11") (pin "1B21") (pinfunction "R1/L21n_1B21") (pintype "passive"))
      (node (ref "U8") (pin "9") (pinfunction "DI3_9") (pintype "passive"))
    )
    (net (code "92") (name "/bus8_n") (class "Default")
      (node (ref "J1") (pin "34") (pinfunction "A34_34") (pintype "passive"))
      (node (ref "J10") (pin "34") (pinfunction "A34_34") (pintype "passive"))
      (node (ref "J11") (pin "34") (pinfunction "A34_34") (pintype "passive"))
      (node (ref "J12") (pin "34") (pinfunction "A34_34") (pintype "passive"))
      (node (ref "J13") (pin "34") (pinfunction "A34_34") (pintype "passive"))
      (node (ref "J14") (pin "34") (pinfunction "A34_34") (pintype "passive"))
      (node (ref "J15") (pin "34") (pinfunction "A34_34") (pintype "passive"))
      (node (ref "J16") (pin "34") (pinfunction "A34_34") (pintype "passive"))
      (node (ref "J2") (pin "34") (pinfunction "A34_34") (pintype "passive"))
      (node (ref "J3") (pin "34") (pinfunction "A34_34") (pintype "passive"))
      (node (ref "J4") (pin "34") (pinfunction "A34_34") (pintype "passive"))
      (node (ref "J5") (pin "34") (pinfunction "A34_34") (pintype "passive"))
      (node (ref "J6") (pin "34") (pinfunction "A34_34") (pintype "passive"))
      (node (ref "J7") (pin "34") (pinfunction "A34_34") (pintype "passive"))
      (node (ref "J8") (pin "34") (pinfunction "A34_34") (pintype "passive"))
      (node (ref "J9") (pin "34") (pinfunction "A34_34") (pintype "passive"))
      (node (ref "R9") (pin "1") (pinfunction "1_1") (pintype "passive"))
      (node (ref "U8") (pin "10") (pinfunction "DO3+_10") (pintype "passive"))
    )
    (net (code "93") (name "/bus8_p") (class "Default")
      (node (ref "J1") (pin "33") (pinfunction "A33_33") (pintype "passive"))
      (node (ref "J10") (pin "33") (pinfunction "A33_33") (pintype "passive"))
      (node (ref "J11") (pin "33") (pinfunction "A33_33") (pintype "passive"))
      (node (ref "J12") (pin "33") (pinfunction "A33_33") (pintype "passive"))
      (node (ref "J13") (pin "33") (pinfunction "A33_33") (pintype "passive"))
      (node (ref "J14") (pin "33") (pinfunction "A33_33") (pintype "passive"))
      (node (ref "J15") (pin "33") (pinfunction "A33_33") (pintype "passive"))
      (node (ref "J16") (pin "33") (pinfunction "A33_33") (pintype "passive"))
      (node (ref "J2") (pin "33") (pinfunction "A33_33") (pintype "passive"))
      (node (ref "J3") (pin "33") (pinfunction "A33_33") (pintype "passive"))
      (node (ref "J4") (pin "33") (pinfunction "A33_33") (pintype "passive"))
      (node (ref "J5") (pin "33") (pinfunction "A33_33") (pintype "passive"))
      (node (ref "J6") (pin "33") (pinfunction "A33_33") (pintype "passive"))
      (node (ref "J7") (pin "33") (pinfunction "A33_33") (pintype "passive"))
      (node (ref "J8") (pin "33") (pinfunction "A33_33") (pintype "passive"))
      (node (ref "J9") (pin "33") (pinfunction "A33_33") (pintype "passive"))
      (node (ref "R9") (pin "2") (pinfunction "2_2") (pintype "passive"))
      (node (ref "U8") (pin "11") (pinfunction "DO3-_11") (pintype "passive"))
    )
    (net (code "94") (name "/bus9") (class "Default")
      (node (ref "P9") (pin "13") (pinfunction "13_13") (pintype "passive"))
      (node (ref "U11") (pin "1B20") (pinfunction "W7/B7p_1B20") (pintype "passive"))
      (node (ref "U8") (pin "15") (pinfunction "DI4_15") (pintype "passive"))
    )
    (net (code "95") (name "/bus9_n") (class "Default")
      (node (ref "J1") (pin "31") (pinfunction "A31_31") (pintype "passive"))
      (node (ref "J10") (pin "31") (pinfunction "A31_31") (pintype "passive"))
      (node (ref "J11") (pin "31") (pinfunction "A31_31") (pintype "passive"))
      (node (ref "J12") (pin "31") (pinfunction "A31_31") (pintype "passive"))
      (node (ref "J13") (pin "31") (pinfunction "A31_31") (pintype "passive"))
      (node (ref "J14") (pin "31") (pinfunction "A31_31") (pintype "passive"))
      (node (ref "J15") (pin "31") (pinfunction "A31_31") (pintype "passive"))
      (node (ref "J16") (pin "31") (pinfunction "A31_31") (pintype "passive"))
      (node (ref "J2") (pin "31") (pinfunction "A31_31") (pintype "passive"))
      (node (ref "J3") (pin "31") (pinfunction "A31_31") (pintype "passive"))
      (node (ref "J4") (pin "31") (pinfunction "A31_31") (pintype "passive"))
      (node (ref "J5") (pin "31") (pinfunction "A31_31") (pintype "passive"))
      (node (ref "J6") (pin "31") (pinfunction "A31_31") (pintype "passive"))
      (node (ref "J7") (pin "31") (pinfunction "A31_31") (pintype "passive"))
      (node (ref "J8") (pin "31") (pinfunction "A31_31") (pintype "passive"))
      (node (ref "J9") (pin "31") (pinfunction "A31_31") (pintype "passive"))
      (node (ref "R10") (pin "1") (pinfunction "1_1") (pintype "passive"))
      (node (ref "U8") (pin "14") (pinfunction "DO4+_14") (pintype "passive"))
    )
    (net (code "96") (name "/bus9_p") (class "Default")
      (node (ref "J1") (pin "32") (pinfunction "A32_32") (pintype "passive"))
      (node (ref "J10") (pin "32") (pinfunction "A32_32") (pintype "passive"))
      (node (ref "J11") (pin "32") (pinfunction "A32_32") (pintype "passive"))
      (node (ref "J12") (pin "32") (pinfunction "A32_32") (pintype "passive"))
      (node (ref "J13") (pin "32") (pinfunction "A32_32") (pintype "passive"))
      (node (ref "J14") (pin "32") (pinfunction "A32_32") (pintype "passive"))
      (node (ref "J15") (pin "32") (pinfunction "A32_32") (pintype "passive"))
      (node (ref "J16") (pin "32") (pinfunction "A32_32") (pintype "passive"))
      (node (ref "J2") (pin "32") (pinfunction "A32_32") (pintype "passive"))
      (node (ref "J3") (pin "32") (pinfunction "A32_32") (pintype "passive"))
      (node (ref "J4") (pin "32") (pinfunction "A32_32") (pintype "passive"))
      (node (ref "J5") (pin "32") (pinfunction "A32_32") (pintype "passive"))
      (node (ref "J6") (pin "32") (pinfunction "A32_32") (pintype "passive"))
      (node (ref "J7") (pin "32") (pinfunction "A32_32") (pintype "passive"))
      (node (ref "J8") (pin "32") (pinfunction "A32_32") (pintype "passive"))
      (node (ref "J9") (pin "32") (pinfunction "A32_32") (pintype "passive"))
      (node (ref "R10") (pin "2") (pinfunction "2_2") (pintype "passive"))
      (node (ref "U8") (pin "13") (pinfunction "DO4-_13") (pintype "passive"))
    )
    (net (code "97") (name "/bus10") (class "Default")
      (node (ref "P9") (pin "18") (pinfunction "18_18") (pintype "passive"))
      (node (ref "U11") (pin "1B23") (pinfunction "P4/L23p_1B23") (pintype "passive"))
      (node (ref "U8") (pin "1") (pinfunction "DI1_1") (pintype "passive"))
    )
    (net (code "98") (name "/bus10_n") (class "Default")
      (node (ref "J1") (pin "38") (pinfunction "A38_38") (pintype "passive"))
      (node (ref "J10") (pin "38") (pinfunction "A38_38") (pintype "passive"))
      (node (ref "J11") (pin "38") (pinfunction "A38_38") (pintype "passive"))
      (node (ref "J12") (pin "38") (pinfunction "A38_38") (pintype "passive"))
      (node (ref "J13") (pin "38") (pinfunction "A38_38") (pintype "passive"))
      (node (ref "J14") (pin "38") (pinfunction "A38_38") (pintype "passive"))
      (node (ref "J15") (pin "38") (pinfunction "A38_38") (pintype "passive"))
      (node (ref "J16") (pin "38") (pinfunction "A38_38") (pintype "passive"))
      (node (ref "J2") (pin "38") (pinfunction "A38_38") (pintype "passive"))
      (node (ref "J3") (pin "38") (pinfunction "A38_38") (pintype "passive"))
      (node (ref "J4") (pin "38") (pinfunction "A38_38") (pintype "passive"))
      (node (ref "J5") (pin "38") (pinfunction "A38_38") (pintype "passive"))
      (node (ref "J6") (pin "38") (pinfunction "A38_38") (pintype "passive"))
      (node (ref "J7") (pin "38") (pinfunction "A38_38") (pintype "passive"))
      (node (ref "J8") (pin "38") (pinfunction "A38_38") (pintype "passive"))
      (node (ref "J9") (pin "38") (pinfunction "A38_38") (pintype "passive"))
      (node (ref "R11") (pin "1") (pinfunction "1_1") (pintype "passive"))
      (node (ref "U8") (pin "2") (pinfunction "DO1+_2") (pintype "passive"))
    )
    (net (code "99") (name "/bus10_p") (class "Default")
      (node (ref "J1") (pin "37") (pinfunction "A37_37") (pintype "passive"))
      (node (ref "J10") (pin "37") (pinfunction "A37_37") (pintype "passive"))
      (node (ref "J11") (pin "37") (pinfunction "A37_37") (pintype "passive"))
      (node (ref "J12") (pin "37") (pinfunction "A37_37") (pintype "passive"))
      (node (ref "J13") (pin "37") (pinfunction "A37_37") (pintype "passive"))
      (node (ref "J14") (pin "37") (pinfunction "A37_37") (pintype "passive"))
      (node (ref "J15") (pin "37") (pinfunction "A37_37") (pintype "passive"))
      (node (ref "J16") (pin "37") (pinfunction "A37_37") (pintype "passive"))
      (node (ref "J2") (pin "37") (pinfunction "A37_37") (pintype "passive"))
      (node (ref "J3") (pin "37") (pinfunction "A37_37") (pintype "passive"))
      (node (ref "J4") (pin "37") (pinfunction "A37_37") (pintype "passive"))
      (node (ref "J5") (pin "37") (pinfunction "A37_37") (pintype "passive"))
      (node (ref "J6") (pin "37") (pinfunction "A37_37") (pintype "passive"))
      (node (ref "J7") (pin "37") (pinfunction "A37_37") (pintype "passive"))
      (node (ref "J8") (pin "37") (pinfunction "A37_37") (pintype "passive"))
      (node (ref "J9") (pin "37") (pinfunction "A37_37") (pintype "passive"))
      (node (ref "R11") (pin "2") (pinfunction "2_2") (pintype "passive"))
      (node (ref "U8") (pin "3") (pinfunction "DO1-_3") (pintype "passive"))
    )
    (net (code "100") (name "/bus11") (class "Default")
      (node (ref "P9") (pin "17") (pinfunction "17_17") (pintype "passive"))
      (node (ref "U11") (pin "1B22") (pinfunction "Y7/B7n_1B22") (pintype "passive"))
      (node (ref "U8") (pin "7") (pinfunction "DI2_7") (pintype "passive"))
    )
    (net (code "101") (name "/bus11_n") (class "Default")
      (node (ref "J1") (pin "35") (pinfunction "A35_35") (pintype "passive"))
      (node (ref "J10") (pin "35") (pinfunction "A35_35") (pintype "passive"))
      (node (ref "J11") (pin "35") (pinfunction "A35_35") (pintype "passive"))
      (node (ref "J12") (pin "35") (pinfunction "A35_35") (pintype "passive"))
      (node (ref "J13") (pin "35") (pinfunction "A35_35") (pintype "passive"))
      (node (ref "J14") (pin "35") (pinfunction "A35_35") (pintype "passive"))
      (node (ref "J15") (pin "35") (pinfunction "A35_35") (pintype "passive"))
      (node (ref "J16") (pin "35") (pinfunction "A35_35") (pintype "passive"))
      (node (ref "J2") (pin "35") (pinfunction "A35_35") (pintype "passive"))
      (node (ref "J3") (pin "35") (pinfunction "A35_35") (pintype "passive"))
      (node (ref "J4") (pin "35") (pinfunction "A35_35") (pintype "passive"))
      (node (ref "J5") (pin "35") (pinfunction "A35_35") (pintype "passive"))
      (node (ref "J6") (pin "35") (pinfunction "A35_35") (pintype "passive"))
      (node (ref "J7") (pin "35") (pinfunction "A35_35") (pintype "passive"))
      (node (ref "J8") (pin "35") (pinfunction "A35_35") (pintype "passive"))
      (node (ref "J9") (pin "35") (pinfunction "A35_35") (pintype "passive"))
      (node (ref "R12") (pin "1") (pinfunction "1_1") (pintype "passive"))
      (node (ref "U8") (pin "6") (pinfunction "DO2+_6") (pintype "passive"))
    )
    (net (code "102") (name "/bus11_p") (class "Default")
      (node (ref "J1") (pin "36") (pinfunction "A36_36") (pintype "passive"))
      (node (ref "J10") (pin "36") (pinfunction "A36_36") (pintype "passive"))
      (node (ref "J11") (pin "36") (pinfunction "A36_36") (pintype "passive"))
      (node (ref "J12") (pin "36") (pinfunction "A36_36") (pintype "passive"))
      (node (ref "J13") (pin "36") (pinfunction "A36_36") (pintype "passive"))
      (node (ref "J14") (pin "36") (pinfunction "A36_36") (pintype "passive"))
      (node (ref "J15") (pin "36") (pinfunction "A36_36") (pintype "passive"))
      (node (ref "J16") (pin "36") (pinfunction "A36_36") (pintype "passive"))
      (node (ref "J2") (pin "36") (pinfunction "A36_36") (pintype "passive"))
      (node (ref "J3") (pin "36") (pinfunction "A36_36") (pintype "passive"))
      (node (ref "J4") (pin "36") (pinfunction "A36_36") (pintype "passive"))
      (node (ref "J5") (pin "36") (pinfunction "A36_36") (pintype "passive"))
      (node (ref "J6") (pin "36") (pinfunction "A36_36") (pintype "passive"))
      (node (ref "J7") (pin "36") (pinfunction "A36_36") (pintype "passive"))
      (node (ref "J8") (pin "36") (pinfunction "A36_36") (pintype "passive"))
      (node (ref "J9") (pin "36") (pinfunction "A36_36") (pintype "passive"))
      (node (ref "R12") (pin "2") (pinfunction "2_2") (pintype "passive"))
      (node (ref "U8") (pin "5") (pinfunction "DO2-_5") (pintype "passive"))
    )
    (net (code "103") (name "/bus12") (class "Default")
      (node (ref "P9") (pin "10") (pinfunction "10_10") (pintype "passive"))
      (node (ref "U11") (pin "1B17") (pinfunction "P1/L20n_1B17") (pintype "passive"))
      (node (ref "U7") (pin "9") (pinfunction "DI3_9") (pintype "passive"))
    )
    (net (code "104") (name "/bus12_n") (class "Default")
      (node (ref "J1") (pin "25") (pinfunction "A25_25") (pintype "passive"))
      (node (ref "J10") (pin "25") (pinfunction "A25_25") (pintype "passive"))
      (node (ref "J11") (pin "25") (pinfunction "A25_25") (pintype "passive"))
      (node (ref "J12") (pin "25") (pinfunction "A25_25") (pintype "passive"))
      (node (ref "J13") (pin "25") (pinfunction "A25_25") (pintype "passive"))
      (node (ref "J14") (pin "25") (pinfunction "A25_25") (pintype "passive"))
      (node (ref "J15") (pin "25") (pinfunction "A25_25") (pintype "passive"))
      (node (ref "J16") (pin "25") (pinfunction "A25_25") (pintype "passive"))
      (node (ref "J2") (pin "25") (pinfunction "A25_25") (pintype "passive"))
      (node (ref "J3") (pin "25") (pinfunction "A25_25") (pintype "passive"))
      (node (ref "J4") (pin "25") (pinfunction "A25_25") (pintype "passive"))
      (node (ref "J5") (pin "25") (pinfunction "A25_25") (pintype "passive"))
      (node (ref "J6") (pin "25") (pinfunction "A25_25") (pintype "passive"))
      (node (ref "J7") (pin "25") (pinfunction "A25_25") (pintype "passive"))
      (node (ref "J8") (pin "25") (pinfunction "A25_25") (pintype "passive"))
      (node (ref "J9") (pin "25") (pinfunction "A25_25") (pintype "passive"))
      (node (ref "R13") (pin "1") (pinfunction "1_1") (pintype "passive"))
      (node (ref "U7") (pin "10") (pinfunction "DO3+_10") (pintype "passive"))
    )
    (net (code "105") (name "/bus12_p") (class "Default")
      (node (ref "J1") (pin "24") (pinfunction "A24_24") (pintype "passive"))
      (node (ref "J10") (pin "24") (pinfunction "A24_24") (pintype "passive"))
      (node (ref "J11") (pin "24") (pinfunction "A24_24") (pintype "passive"))
      (node (ref "J12") (pin "24") (pinfunction "A24_24") (pintype "passive"))
      (node (ref "J13") (pin "24") (pinfunction "A24_24") (pintype "passive"))
      (node (ref "J14") (pin "24") (pinfunction "A24_24") (pintype "passive"))
      (node (ref "J15") (pin "24") (pinfunction "A24_24") (pintype "passive"))
      (node (ref "J16") (pin "24") (pinfunction "A24_24") (pintype "passive"))
      (node (ref "J2") (pin "24") (pinfunction "A24_24") (pintype "passive"))
      (node (ref "J3") (pin "24") (pinfunction "A24_24") (pintype "passive"))
      (node (ref "J4") (pin "24") (pinfunction "A24_24") (pintype "passive"))
      (node (ref "J5") (pin "24") (pinfunction "A24_24") (pintype "passive"))
      (node (ref "J6") (pin "24") (pinfunction "A24_24") (pintype "passive"))
      (node (ref "J7") (pin "24") (pinfunction "A24_24") (pintype "passive"))
      (node (ref "J8") (pin "24") (pinfunction "A24_24") (pintype "passive"))
      (node (ref "J9") (pin "24") (pinfunction "A24_24") (pintype "passive"))
      (node (ref "R13") (pin "2") (pinfunction "2_2") (pintype "passive"))
      (node (ref "U7") (pin "11") (pinfunction "DO3-_11") (pintype "passive"))
    )
    (net (code "106") (name "/bus13") (class "Default")
      (node (ref "P9") (pin "9") (pinfunction "9_9") (pintype "passive"))
      (node (ref "U11") (pin "1B16") (pinfunction "AB6/B6p_1B16") (pintype "passive"))
      (node (ref "U7") (pin "15") (pinfunction "DI4_15") (pintype "passive"))
    )
    (net (code "107") (name "/bus13_n") (class "Default")
      (node (ref "J1") (pin "22") (pinfunction "A22_22") (pintype "passive"))
      (node (ref "J10") (pin "22") (pinfunction "A22_22") (pintype "passive"))
      (node (ref "J11") (pin "22") (pinfunction "A22_22") (pintype "passive"))
      (node (ref "J12") (pin "22") (pinfunction "A22_22") (pintype "passive"))
      (node (ref "J13") (pin "22") (pinfunction "A22_22") (pintype "passive"))
      (node (ref "J14") (pin "22") (pinfunction "A22_22") (pintype "passive"))
      (node (ref "J15") (pin "22") (pinfunction "A22_22") (pintype "passive"))
      (node (ref "J16") (pin "22") (pinfunction "A22_22") (pintype "passive"))
      (node (ref "J2") (pin "22") (pinfunction "A22_22") (pintype "passive"))
      (node (ref "J3") (pin "22") (pinfunction "A22_22") (pintype "passive"))
      (node (ref "J4") (pin "22") (pinfunction "A22_22") (pintype "passive"))
      (node (ref "J5") (pin "22") (pinfunction "A22_22") (pintype "passive"))
      (node (ref "J6") (pin "22") (pinfunction "A22_22") (pintype "passive"))
      (node (ref "J7") (pin "22") (pinfunction "A22_22") (pintype "passive"))
      (node (ref "J8") (pin "22") (pinfunction "A22_22") (pintype "passive"))
      (node (ref "J9") (pin "22") (pinfunction "A22_22") (pintype "passive"))
      (node (ref "R14") (pin "1") (pinfunction "1_1") (pintype "passive"))
      (node (ref "U7") (pin "14") (pinfunction "DO4+_14") (pintype "passive"))
    )
    (net (code "108") (name "/bus13_p") (class "Default")
      (node (ref "J1") (pin "23") (pinfunction "A23_23") (pintype "passive"))
      (node (ref "J10") (pin "23") (pinfunction "A23_23") (pintype "passive"))
      (node (ref "J11") (pin "23") (pinfunction "A23_23") (pintype "passive"))
      (node (ref "J12") (pin "23") (pinfunction "A23_23") (pintype "passive"))
      (node (ref "J13") (pin "23") (pinfunction "A23_23") (pintype "passive"))
      (node (ref "J14") (pin "23") (pinfunction "A23_23") (pintype "passive"))
      (node (ref "J15") (pin "23") (pinfunction "A23_23") (pintype "passive"))
      (node (ref "J16") (pin "23") (pinfunction "A23_23") (pintype "passive"))
      (node (ref "J2") (pin "23") (pinfunction "A23_23") (pintype "passive"))
      (node (ref "J3") (pin "23") (pinfunction "A23_23") (pintype "passive"))
      (node (ref "J4") (pin "23") (pinfunction "A23_23") (pintype "passive"))
      (node (ref "J5") (pin "23") (pinfunction "A23_23") (pintype "passive"))
      (node (ref "J6") (pin "23") (pinfunction "A23_23") (pintype "passive"))
      (node (ref "J7") (pin "23") (pinfunction "A23_23") (pintype "passive"))
      (node (ref "J8") (pin "23") (pinfunction "A23_23") (pintype "passive"))
      (node (ref "J9") (pin "23") (pinfunction "A23_23") (pintype "passive"))
      (node (ref "R14") (pin "2") (pinfunction "2_2") (pintype "passive"))
      (node (ref "U7") (pin "13") (pinfunction "DO4-_13") (pintype "passive"))
    )
    (net (code "109") (name "/bus14") (class "Default")
      (node (ref "P9") (pin "12") (pinfunction "12_12") (pintype "passive"))
      (node (ref "U11") (pin "1B19") (pinfunction "R2/L21p_1B19") (pintype "passive"))
      (node (ref "U7") (pin "1") (pinfunction "DI1_1") (pintype "passive"))
    )
    (net (code "110") (name "/bus14_n") (class "Default")
      (node (ref "J1") (pin "29") (pinfunction "A29_29") (pintype "passive"))
      (node (ref "J10") (pin "29") (pinfunction "A29_29") (pintype "passive"))
      (node (ref "J11") (pin "29") (pinfunction "A29_29") (pintype "passive"))
      (node (ref "J12") (pin "29") (pinfunction "A29_29") (pintype "passive"))
      (node (ref "J13") (pin "29") (pinfunction "A29_29") (pintype "passive"))
      (node (ref "J14") (pin "29") (pinfunction "A29_29") (pintype "passive"))
      (node (ref "J15") (pin "29") (pinfunction "A29_29") (pintype "passive"))
      (node (ref "J16") (pin "29") (pinfunction "A29_29") (pintype "passive"))
      (node (ref "J2") (pin "29") (pinfunction "A29_29") (pintype "passive"))
      (node (ref "J3") (pin "29") (pinfunction "A29_29") (pintype "passive"))
      (node (ref "J4") (pin "29") (pinfunction "A29_29") (pintype "passive"))
      (node (ref "J5") (pin "29") (pinfunction "A29_29") (pintype "passive"))
      (node (ref "J6") (pin "29") (pinfunction "A29_29") (pintype "passive"))
      (node (ref "J7") (pin "29") (pinfunction "A29_29") (pintype "passive"))
      (node (ref "J8") (pin "29") (pinfunction "A29_29") (pintype "passive"))
      (node (ref "J9") (pin "29") (pinfunction "A29_29") (pintype "passive"))
      (node (ref "R15") (pin "1") (pinfunction "1_1") (pintype "passive"))
      (node (ref "U7") (pin "2") (pinfunction "DO1+_2") (pintype "passive"))
    )
    (net (code "111") (name "/bus14_p") (class "Default")
      (node (ref "J1") (pin "28") (pinfunction "A28_28") (pintype "passive"))
      (node (ref "J10") (pin "28") (pinfunction "A28_28") (pintype "passive"))
      (node (ref "J11") (pin "28") (pinfunction "A28_28") (pintype "passive"))
      (node (ref "J12") (pin "28") (pinfunction "A28_28") (pintype "passive"))
      (node (ref "J13") (pin "28") (pinfunction "A28_28") (pintype "passive"))
      (node (ref "J14") (pin "28") (pinfunction "A28_28") (pintype "passive"))
      (node (ref "J15") (pin "28") (pinfunction "A28_28") (pintype "passive"))
      (node (ref "J16") (pin "28") (pinfunction "A28_28") (pintype "passive"))
      (node (ref "J2") (pin "28") (pinfunction "A28_28") (pintype "passive"))
      (node (ref "J3") (pin "28") (pinfunction "A28_28") (pintype "passive"))
      (node (ref "J4") (pin "28") (pinfunction "A28_28") (pintype "passive"))
      (node (ref "J5") (pin "28") (pinfunction "A28_28") (pintype "passive"))
      (node (ref "J6") (pin "28") (pinfunction "A28_28") (pintype "passive"))
      (node (ref "J7") (pin "28") (pinfunction "A28_28") (pintype "passive"))
      (node (ref "J8") (pin "28") (pinfunction "A28_28") (pintype "passive"))
      (node (ref "J9") (pin "28") (pinfunction "A28_28") (pintype "passive"))
      (node (ref "R15") (pin "2") (pinfunction "2_2") (pintype "passive"))
      (node (ref "U7") (pin "3") (pinfunction "DO1-_3") (pintype "passive"))
    )
    (net (code "112") (name "/bus15") (class "Default")
      (node (ref "P9") (pin "11") (pinfunction "11_11") (pintype "passive"))
      (node (ref "U11") (pin "1B18") (pinfunction "AB5/B6n_1B18") (pintype "passive"))
      (node (ref "U7") (pin "7") (pinfunction "DI2_7") (pintype "passive"))
    )
    (net (code "113") (name "/bus15_n") (class "Default")
      (node (ref "J1") (pin "26") (pinfunction "A26_26") (pintype "passive"))
      (node (ref "J10") (pin "26") (pinfunction "A26_26") (pintype "passive"))
      (node (ref "J11") (pin "26") (pinfunction "A26_26") (pintype "passive"))
      (node (ref "J12") (pin "26") (pinfunction "A26_26") (pintype "passive"))
      (node (ref "J13") (pin "26") (pinfunction "A26_26") (pintype "passive"))
      (node (ref "J14") (pin "26") (pinfunction "A26_26") (pintype "passive"))
      (node (ref "J15") (pin "26") (pinfunction "A26_26") (pintype "passive"))
      (node (ref "J16") (pin "26") (pinfunction "A26_26") (pintype "passive"))
      (node (ref "J2") (pin "26") (pinfunction "A26_26") (pintype "passive"))
      (node (ref "J3") (pin "26") (pinfunction "A26_26") (pintype "passive"))
      (node (ref "J4") (pin "26") (pinfunction "A26_26") (pintype "passive"))
      (node (ref "J5") (pin "26") (pinfunction "A26_26") (pintype "passive"))
      (node (ref "J6") (pin "26") (pinfunction "A26_26") (pintype "passive"))
      (node (ref "J7") (pin "26") (pinfunction "A26_26") (pintype "passive"))
      (node (ref "J8") (pin "26") (pinfunction "A26_26") (pintype "passive"))
      (node (ref "J9") (pin "26") (pinfunction "A26_26") (pintype "passive"))
      (node (ref "R16") (pin "1") (pinfunction "1_1") (pintype "passive"))
      (node (ref "U7") (pin "6") (pinfunction "DO2+_6") (pintype "passive"))
    )
    (net (code "114") (name "/bus15_p") (class "Default")
      (node (ref "J1") (pin "27") (pinfunction "A27_27") (pintype "passive"))
      (node (ref "J10") (pin "27") (pinfunction "A27_27") (pintype "passive"))
      (node (ref "J11") (pin "27") (pinfunction "A27_27") (pintype "passive"))
      (node (ref "J12") (pin "27") (pinfunction "A27_27") (pintype "passive"))
      (node (ref "J13") (pin "27") (pinfunction "A27_27") (pintype "passive"))
      (node (ref "J14") (pin "27") (pinfunction "A27_27") (pintype "passive"))
      (node (ref "J15") (pin "27") (pinfunction "A27_27") (pintype "passive"))
      (node (ref "J16") (pin "27") (pinfunction "A27_27") (pintype "passive"))
      (node (ref "J2") (pin "27") (pinfunction "A27_27") (pintype "passive"))
      (node (ref "J3") (pin "27") (pinfunction "A27_27") (pintype "passive"))
      (node (ref "J4") (pin "27") (pinfunction "A27_27") (pintype "passive"))
      (node (ref "J5") (pin "27") (pinfunction "A27_27") (pintype "passive"))
      (node (ref "J6") (pin "27") (pinfunction "A27_27") (pintype "passive"))
      (node (ref "J7") (pin "27") (pinfunction "A27_27") (pintype "passive"))
      (node (ref "J8") (pin "27") (pinfunction "A27_27") (pintype "passive"))
      (node (ref "J9") (pin "27") (pinfunction "A27_27") (pintype "passive"))
      (node (ref "R16") (pin "2") (pinfunction "2_2") (pintype "passive"))
      (node (ref "U7") (pin "5") (pinfunction "DO2-_5") (pintype "passive"))
    )
    (net (code "115") (name "/bus16") (class "Default")
      (node (ref "P7") (pin "16") (pinfunction "16_16") (pintype "passive"))
      (node (ref "U11") (pin "1A23") (pinfunction "W8/IO_1A23") (pintype "passive"))
      (node (ref "U6") (pin "9") (pinfunction "DI3_9") (pintype "passive"))
    )
    (net (code "116") (name "/bus16_n") (class "Default")
      (node (ref "J1") (pin "113") (pinfunction "B53_113") (pintype "passive"))
      (node (ref "J10") (pin "113") (pinfunction "B53_113") (pintype "passive"))
      (node (ref "J11") (pin "113") (pinfunction "B53_113") (pintype "passive"))
      (node (ref "J12") (pin "113") (pinfunction "B53_113") (pintype "passive"))
      (node (ref "J13") (pin "113") (pinfunction "B53_113") (pintype "passive"))
      (node (ref "J14") (pin "113") (pinfunction "B53_113") (pintype "passive"))
      (node (ref "J15") (pin "113") (pinfunction "B53_113") (pintype "passive"))
      (node (ref "J16") (pin "113") (pinfunction "B53_113") (pintype "passive"))
      (node (ref "J2") (pin "113") (pinfunction "B53_113") (pintype "passive"))
      (node (ref "J3") (pin "113") (pinfunction "B53_113") (pintype "passive"))
      (node (ref "J4") (pin "113") (pinfunction "B53_113") (pintype "passive"))
      (node (ref "J5") (pin "113") (pinfunction "B53_113") (pintype "passive"))
      (node (ref "J6") (pin "113") (pinfunction "B53_113") (pintype "passive"))
      (node (ref "J7") (pin "113") (pinfunction "B53_113") (pintype "passive"))
      (node (ref "J8") (pin "113") (pinfunction "B53_113") (pintype "passive"))
      (node (ref "J9") (pin "113") (pinfunction "B53_113") (pintype "passive"))
      (node (ref "R17") (pin "1") (pinfunction "1_1") (pintype "passive"))
      (node (ref "U6") (pin "10") (pinfunction "DO3+_10") (pintype "passive"))
    )
    (net (code "117") (name "/bus16_p") (class "Default")
      (node (ref "J1") (pin "114") (pinfunction "B54_114") (pintype "passive"))
      (node (ref "J10") (pin "114") (pinfunction "B54_114") (pintype "passive"))
      (node (ref "J11") (pin "114") (pinfunction "B54_114") (pintype "passive"))
      (node (ref "J12") (pin "114") (pinfunction "B54_114") (pintype "passive"))
      (node (ref "J13") (pin "114") (pinfunction "B54_114") (pintype "passive"))
      (node (ref "J14") (pin "114") (pinfunction "B54_114") (pintype "passive"))
      (node (ref "J15") (pin "114") (pinfunction "B54_114") (pintype "passive"))
      (node (ref "J16") (pin "114") (pinfunction "B54_114") (pintype "passive"))
      (node (ref "J2") (pin "114") (pinfunction "B54_114") (pintype "passive"))
      (node (ref "J3") (pin "114") (pinfunction "B54_114") (pintype "passive"))
      (node (ref "J4") (pin "114") (pinfunction "B54_114") (pintype "passive"))
      (node (ref "J5") (pin "114") (pinfunction "B54_114") (pintype "passive"))
      (node (ref "J6") (pin "114") (pinfunction "B54_114") (pintype "passive"))
      (node (ref "J7") (pin "114") (pinfunction "B54_114") (pintype "passive"))
      (node (ref "J8") (pin "114") (pinfunction "B54_114") (pintype "passive"))
      (node (ref "J9") (pin "114") (pinfunction "B54_114") (pintype "passive"))
      (node (ref "R17") (pin "2") (pinfunction "2_2") (pintype "passive"))
      (node (ref "U6") (pin "11") (pinfunction "DO3-_11") (pintype "passive"))
    )
    (net (code "118") (name "/bus17") (class "Default")
      (node (ref "P7") (pin "15") (pinfunction "15_15") (pintype "passive"))
      (node (ref "U11") (pin "1A20") (pinfunction "U10/B16n_1A20") (pintype "passive"))
      (node (ref "U6") (pin "15") (pinfunction "DI4_15") (pintype "passive"))
    )
    (net (code "119") (name "/bus17_n") (class "Default")
      (node (ref "J1") (pin "116") (pinfunction "B56_116") (pintype "passive"))
      (node (ref "J10") (pin "116") (pinfunction "B56_116") (pintype "passive"))
      (node (ref "J11") (pin "116") (pinfunction "B56_116") (pintype "passive"))
      (node (ref "J12") (pin "116") (pinfunction "B56_116") (pintype "passive"))
      (node (ref "J13") (pin "116") (pinfunction "B56_116") (pintype "passive"))
      (node (ref "J14") (pin "116") (pinfunction "B56_116") (pintype "passive"))
      (node (ref "J15") (pin "116") (pinfunction "B56_116") (pintype "passive"))
      (node (ref "J16") (pin "116") (pinfunction "B56_116") (pintype "passive"))
      (node (ref "J2") (pin "116") (pinfunction "B56_116") (pintype "passive"))
      (node (ref "J3") (pin "116") (pinfunction "B56_116") (pintype "passive"))
      (node (ref "J4") (pin "116") (pinfunction "B56_116") (pintype "passive"))
      (node (ref "J5") (pin "116") (pinfunction "B56_116") (pintype "passive"))
      (node (ref "J6") (pin "116") (pinfunction "B56_116") (pintype "passive"))
      (node (ref "J7") (pin "116") (pinfunction "B56_116") (pintype "passive"))
      (node (ref "J8") (pin "116") (pinfunction "B56_116") (pintype "passive"))
      (node (ref "J9") (pin "116") (pinfunction "B56_116") (pintype "passive"))
      (node (ref "R18") (pin "1") (pinfunction "1_1") (pintype "passive"))
      (node (ref "U6") (pin "14") (pinfunction "DO4+_14") (pintype "passive"))
    )
    (net (code "120") (name "/bus17_p") (class "Default")
      (node (ref "J1") (pin "115") (pinfunction "B55_115") (pintype "passive"))
      (node (ref "J10") (pin "115") (pinfunction "B55_115") (pintype "passive"))
      (node (ref "J11") (pin "115") (pinfunction "B55_115") (pintype "passive"))
      (node (ref "J12") (pin "115") (pinfunction "B55_115") (pintype "passive"))
      (node (ref "J13") (pin "115") (pinfunction "B55_115") (pintype "passive"))
      (node (ref "J14") (pin "115") (pinfunction "B55_115") (pintype "passive"))
      (node (ref "J15") (pin "115") (pinfunction "B55_115") (pintype "passive"))
      (node (ref "J16") (pin "115") (pinfunction "B55_115") (pintype "passive"))
      (node (ref "J2") (pin "115") (pinfunction "B55_115") (pintype "passive"))
      (node (ref "J3") (pin "115") (pinfunction "B55_115") (pintype "passive"))
      (node (ref "J4") (pin "115") (pinfunction "B55_115") (pintype "passive"))
      (node (ref "J5") (pin "115") (pinfunction "B55_115") (pintype "passive"))
      (node (ref "J6") (pin "115") (pinfunction "B55_115") (pintype "passive"))
      (node (ref "J7") (pin "115") (pinfunction "B55_115") (pintype "passive"))
      (node (ref "J8") (pin "115") (pinfunction "B55_115") (pintype "passive"))
      (node (ref "J9") (pin "115") (pinfunction "B55_115") (pintype "passive"))
      (node (ref "R18") (pin "2") (pinfunction "2_2") (pintype "passive"))
      (node (ref "U6") (pin "13") (pinfunction "DO4-_13") (pintype "passive"))
    )
    (net (code "121") (name "/bus18") (class "Default")
      (node (ref "P7") (pin "18") (pinfunction "18_18") (pintype "passive"))
      (node (ref "U11") (pin "1A29") (pinfunction "V10/B15p_1A29") (pintype "passive"))
      (node (ref "U6") (pin "1") (pinfunction "DI1_1") (pintype "passive"))
    )
    (net (code "122") (name "/bus18_n") (class "Default")
      (node (ref "J1") (pin "109") (pinfunction "B49_109") (pintype "passive"))
      (node (ref "J10") (pin "109") (pinfunction "B49_109") (pintype "passive"))
      (node (ref "J11") (pin "109") (pinfunction "B49_109") (pintype "passive"))
      (node (ref "J12") (pin "109") (pinfunction "B49_109") (pintype "passive"))
      (node (ref "J13") (pin "109") (pinfunction "B49_109") (pintype "passive"))
      (node (ref "J14") (pin "109") (pinfunction "B49_109") (pintype "passive"))
      (node (ref "J15") (pin "109") (pinfunction "B49_109") (pintype "passive"))
      (node (ref "J16") (pin "109") (pinfunction "B49_109") (pintype "passive"))
      (node (ref "J2") (pin "109") (pinfunction "B49_109") (pintype "passive"))
      (node (ref "J3") (pin "109") (pinfunction "B49_109") (pintype "passive"))
      (node (ref "J4") (pin "109") (pinfunction "B49_109") (pintype "passive"))
      (node (ref "J5") (pin "109") (pinfunction "B49_109") (pintype "passive"))
      (node (ref "J6") (pin "109") (pinfunction "B49_109") (pintype "passive"))
      (node (ref "J7") (pin "109") (pinfunction "B49_109") (pintype "passive"))
      (node (ref "J8") (pin "109") (pinfunction "B49_109") (pintype "passive"))
      (node (ref "J9") (pin "109") (pinfunction "B49_109") (pintype "passive"))
      (node (ref "R19") (pin "1") (pinfunction "1_1") (pintype "passive"))
      (node (ref "U6") (pin "2") (pinfunction "DO1+_2") (pintype "passive"))
    )
    (net (code "123") (name "/bus18_p") (class "Default")
      (node (ref "J1") (pin "110") (pinfunction "B50_110") (pintype "passive"))
      (node (ref "J10") (pin "110") (pinfunction "B50_110") (pintype "passive"))
      (node (ref "J11") (pin "110") (pinfunction "B50_110") (pintype "passive"))
      (node (ref "J12") (pin "110") (pinfunction "B50_110") (pintype "passive"))
      (node (ref "J13") (pin "110") (pinfunction "B50_110") (pintype "passive"))
      (node (ref "J14") (pin "110") (pinfunction "B50_110") (pintype "passive"))
      (node (ref "J15") (pin "110") (pinfunction "B50_110") (pintype "passive"))
      (node (ref "J16") (pin "110") (pinfunction "B50_110") (pintype "passive"))
      (node (ref "J2") (pin "110") (pinfunction "B50_110") (pintype "passive"))
      (node (ref "J3") (pin "110") (pinfunction "B50_110") (pintype "passive"))
      (node (ref "J4") (pin "110") (pinfunction "B50_110") (pintype "passive"))
      (node (ref "J5") (pin "110") (pinfunction "B50_110") (pintype "passive"))
      (node (ref "J6") (pin "110") (pinfunction "B50_110") (pintype "passive"))
      (node (ref "J7") (pin "110") (pinfunction "B50_110") (pintype "passive"))
      (node (ref "J8") (pin "110") (pinfunction "B50_110") (pintype "passive"))
      (node (ref "J9") (pin "110") (pinfunction "B50_110") (pintype "passive"))
      (node (ref "R19") (pin "2") (pinfunction "2_2") (pintype "passive"))
      (node (ref "U6") (pin "3") (pinfunction "DO1-_3") (pintype "passive"))
    )
    (net (code "124") (name "/bus19") (class "Default")
      (node (ref "P7") (pin "17") (pinfunction "17_17") (pintype "passive"))
      (node (ref "U11") (pin "1A28") (pinfunction "V8/B8n_1A28") (pintype "passive"))
      (node (ref "U6") (pin "7") (pinfunction "DI2_7") (pintype "passive"))
    )
    (net (code "125") (name "/bus19_n") (class "Default")
      (node (ref "J1") (pin "112") (pinfunction "B52_112") (pintype "passive"))
      (node (ref "J10") (pin "112") (pinfunction "B52_112") (pintype "passive"))
      (node (ref "J11") (pin "112") (pinfunction "B52_112") (pintype "passive"))
      (node (ref "J12") (pin "112") (pinfunction "B52_112") (pintype "passive"))
      (node (ref "J13") (pin "112") (pinfunction "B52_112") (pintype "passive"))
      (node (ref "J14") (pin "112") (pinfunction "B52_112") (pintype "passive"))
      (node (ref "J15") (pin "112") (pinfunction "B52_112") (pintype "passive"))
      (node (ref "J16") (pin "112") (pinfunction "B52_112") (pintype "passive"))
      (node (ref "J2") (pin "112") (pinfunction "B52_112") (pintype "passive"))
      (node (ref "J3") (pin "112") (pinfunction "B52_112") (pintype "passive"))
      (node (ref "J4") (pin "112") (pinfunction "B52_112") (pintype "passive"))
      (node (ref "J5") (pin "112") (pinfunction "B52_112") (pintype "passive"))
      (node (ref "J6") (pin "112") (pinfunction "B52_112") (pintype "passive"))
      (node (ref "J7") (pin "112") (pinfunction "B52_112") (pintype "passive"))
      (node (ref "J8") (pin "112") (pinfunction "B52_112") (pintype "passive"))
      (node (ref "J9") (pin "112") (pinfunction "B52_112") (pintype "passive"))
      (node (ref "R20") (pin "1") (pinfunction "1_1") (pintype "passive"))
      (node (ref "U6") (pin "6") (pinfunction "DO2+_6") (pintype "passive"))
    )
    (net (code "126") (name "/bus19_p") (class "Default")
      (node (ref "J1") (pin "111") (pinfunction "B51_111") (pintype "passive"))
      (node (ref "J10") (pin "111") (pinfunction "B51_111") (pintype "passive"))
      (node (ref "J11") (pin "111") (pinfunction "B51_111") (pintype "passive"))
      (node (ref "J12") (pin "111") (pinfunction "B51_111") (pintype "passive"))
      (node (ref "J13") (pin "111") (pinfunction "B51_111") (pintype "passive"))
      (node (ref "J14") (pin "111") (pinfunction "B51_111") (pintype "passive"))
      (node (ref "J15") (pin "111") (pinfunction "B51_111") (pintype "passive"))
      (node (ref "J16") (pin "111") (pinfunction "B51_111") (pintype "passive"))
      (node (ref "J2") (pin "111") (pinfunction "B51_111") (pintype "passive"))
      (node (ref "J3") (pin "111") (pinfunction "B51_111") (pintype "passive"))
      (node (ref "J4") (pin "111") (pinfunction "B51_111") (pintype "passive"))
      (node (ref "J5") (pin "111") (pinfunction "B51_111") (pintype "passive"))
      (node (ref "J6") (pin "111") (pinfunction "B51_111") (pintype "passive"))
      (node (ref "J7") (pin "111") (pinfunction "B51_111") (pintype "passive"))
      (node (ref "J8") (pin "111") (pinfunction "B51_111") (pintype "passive"))
      (node (ref "J9") (pin "111") (pinfunction "B51_111") (pintype "passive"))
      (node (ref "R20") (pin "2") (pinfunction "2_2") (pintype "passive"))
      (node (ref "U6") (pin "5") (pinfunction "DO2-_5") (pintype "passive"))
    )
    (net (code "127") (name "/bus20") (class "Default")
      (node (ref "P7") (pin "20") (pinfunction "20_20") (pintype "passive"))
      (node (ref "U11") (pin "1A31") (pinfunction "U9/B8p_1A31") (pintype "passive"))
      (node (ref "U5") (pin "9") (pinfunction "DI3_9") (pintype "passive"))
    )
    (net (code "128") (name "/bus20_n") (class "Default")
      (node (ref "J1") (pin "104") (pinfunction "B44_104") (pintype "passive"))
      (node (ref "J10") (pin "104") (pinfunction "B44_104") (pintype "passive"))
      (node (ref "J11") (pin "104") (pinfunction "B44_104") (pintype "passive"))
      (node (ref "J12") (pin "104") (pinfunction "B44_104") (pintype "passive"))
      (node (ref "J13") (pin "104") (pinfunction "B44_104") (pintype "passive"))
      (node (ref "J14") (pin "104") (pinfunction "B44_104") (pintype "passive"))
      (node (ref "J15") (pin "104") (pinfunction "B44_104") (pintype "passive"))
      (node (ref "J16") (pin "104") (pinfunction "B44_104") (pintype "passive"))
      (node (ref "J2") (pin "104") (pinfunction "B44_104") (pintype "passive"))
      (node (ref "J3") (pin "104") (pinfunction "B44_104") (pintype "passive"))
      (node (ref "J4") (pin "104") (pinfunction "B44_104") (pintype "passive"))
      (node (ref "J5") (pin "104") (pinfunction "B44_104") (pintype "passive"))
      (node (ref "J6") (pin "104") (pinfunction "B44_104") (pintype "passive"))
      (node (ref "J7") (pin "104") (pinfunction "B44_104") (pintype "passive"))
      (node (ref "J8") (pin "104") (pinfunction "B44_104") (pintype "passive"))
      (node (ref "J9") (pin "104") (pinfunction "B44_104") (pintype "passive"))
      (node (ref "R21") (pin "1") (pinfunction "1_1") (pintype "passive"))
      (node (ref "U5") (pin "10") (pinfunction "DO3+_10") (pintype "passive"))
    )
    (net (code "129") (name "/bus20_p") (class "Default")
      (node (ref "J1") (pin "105") (pinfunction "B45_105") (pintype "passive"))
      (node (ref "J10") (pin "105") (pinfunction "B45_105") (pintype "passive"))
      (node (ref "J11") (pin "105") (pinfunction "B45_105") (pintype "passive"))
      (node (ref "J12") (pin "105") (pinfunction "B45_105") (pintype "passive"))
      (node (ref "J13") (pin "105") (pinfunction "B45_105") (pintype "passive"))
      (node (ref "J14") (pin "105") (pinfunction "B45_105") (pintype "passive"))
      (node (ref "J15") (pin "105") (pinfunction "B45_105") (pintype "passive"))
      (node (ref "J16") (pin "105") (pinfunction "B45_105") (pintype "passive"))
      (node (ref "J2") (pin "105") (pinfunction "B45_105") (pintype "passive"))
      (node (ref "J3") (pin "105") (pinfunction "B45_105") (pintype "passive"))
      (node (ref "J4") (pin "105") (pinfunction "B45_105") (pintype "passive"))
      (node (ref "J5") (pin "105") (pinfunction "B45_105") (pintype "passive"))
      (node (ref "J6") (pin "105") (pinfunction "B45_105") (pintype "passive"))
      (node (ref "J7") (pin "105") (pinfunction "B45_105") (pintype "passive"))
      (node (ref "J8") (pin "105") (pinfunction "B45_105") (pintype "passive"))
      (node (ref "J9") (pin "105") (pinfunction "B45_105") (pintype "passive"))
      (node (ref "R21") (pin "2") (pinfunction "2_2") (pintype "passive"))
      (node (ref "U5") (pin "11") (pinfunction "DO3-_11") (pintype "passive"))
    )
    (net (code "130") (name "/bus21") (class "Default")
      (node (ref "P7") (pin "19") (pinfunction "19_19") (pintype "passive"))
      (node (ref "U11") (pin "1A30") (pinfunction "Y6/IO_1A30") (pintype "passive"))
      (node (ref "U5") (pin "15") (pinfunction "DI4_15") (pintype "passive"))
    )
    (net (code "131") (name "/bus21_n") (class "Default")
      (node (ref "J1") (pin "107") (pinfunction "B47_107") (pintype "passive"))
      (node (ref "J10") (pin "107") (pinfunction "B47_107") (pintype "passive"))
      (node (ref "J11") (pin "107") (pinfunction "B47_107") (pintype "passive"))
      (node (ref "J12") (pin "107") (pinfunction "B47_107") (pintype "passive"))
      (node (ref "J13") (pin "107") (pinfunction "B47_107") (pintype "passive"))
      (node (ref "J14") (pin "107") (pinfunction "B47_107") (pintype "passive"))
      (node (ref "J15") (pin "107") (pinfunction "B47_107") (pintype "passive"))
      (node (ref "J16") (pin "107") (pinfunction "B47_107") (pintype "passive"))
      (node (ref "J2") (pin "107") (pinfunction "B47_107") (pintype "passive"))
      (node (ref "J3") (pin "107") (pinfunction "B47_107") (pintype "passive"))
      (node (ref "J4") (pin "107") (pinfunction "B47_107") (pintype "passive"))
      (node (ref "J5") (pin "107") (pinfunction "B47_107") (pintype "passive"))
      (node (ref "J6") (pin "107") (pinfunction "B47_107") (pintype "passive"))
      (node (ref "J7") (pin "107") (pinfunction "B47_107") (pintype "passive"))
      (node (ref "J8") (pin "107") (pinfunction "B47_107") (pintype "passive"))
      (node (ref "J9") (pin "107") (pinfunction "B47_107") (pintype "passive"))
      (node (ref "R22") (pin "1") (pinfunction "1_1") (pintype "passive"))
      (node (ref "U5") (pin "14") (pinfunction "DO4+_14") (pintype "passive"))
    )
    (net (code "132") (name "/bus21_p") (class "Default")
      (node (ref "J1") (pin "106") (pinfunction "B46_106") (pintype "passive"))
      (node (ref "J10") (pin "106") (pinfunction "B46_106") (pintype "passive"))
      (node (ref "J11") (pin "106") (pinfunction "B46_106") (pintype "passive"))
      (node (ref "J12") (pin "106") (pinfunction "B46_106") (pintype "passive"))
      (node (ref "J13") (pin "106") (pinfunction "B46_106") (pintype "passive"))
      (node (ref "J14") (pin "106") (pinfunction "B46_106") (pintype "passive"))
      (node (ref "J15") (pin "106") (pinfunction "B46_106") (pintype "passive"))
      (node (ref "J16") (pin "106") (pinfunction "B46_106") (pintype "passive"))
      (node (ref "J2") (pin "106") (pinfunction "B46_106") (pintype "passive"))
      (node (ref "J3") (pin "106") (pinfunction "B46_106") (pintype "passive"))
      (node (ref "J4") (pin "106") (pinfunction "B46_106") (pintype "passive"))
      (node (ref "J5") (pin "106") (pinfunction "B46_106") (pintype "passive"))
      (node (ref "J6") (pin "106") (pinfunction "B46_106") (pintype "passive"))
      (node (ref "J7") (pin "106") (pinfunction "B46_106") (pintype "passive"))
      (node (ref "J8") (pin "106") (pinfunction "B46_106") (pintype "passive"))
      (node (ref "J9") (pin "106") (pinfunction "B46_106") (pintype "passive"))
      (node (ref "R22") (pin "2") (pinfunction "2_2") (pintype "passive"))
      (node (ref "U5") (pin "13") (pinfunction "DO4-_13") (pintype "passive"))
    )
    (net (code "133") (name "/bus22") (class "Default")
      (node (ref "P7") (pin "26") (pinfunction "26_26") (pintype "passive"))
      (node (ref "U11") (pin "1A33") (pinfunction "Y3/B3n_1A33") (pintype "passive"))
      (node (ref "U5") (pin "1") (pinfunction "DI1_1") (pintype "passive"))
    )
    (net (code "134") (name "/bus22_n") (class "Default")
      (node (ref "J1") (pin "100") (pinfunction "B40_100") (pintype "passive"))
      (node (ref "J10") (pin "100") (pinfunction "B40_100") (pintype "passive"))
      (node (ref "J11") (pin "100") (pinfunction "B40_100") (pintype "passive"))
      (node (ref "J12") (pin "100") (pinfunction "B40_100") (pintype "passive"))
      (node (ref "J13") (pin "100") (pinfunction "B40_100") (pintype "passive"))
      (node (ref "J14") (pin "100") (pinfunction "B40_100") (pintype "passive"))
      (node (ref "J15") (pin "100") (pinfunction "B40_100") (pintype "passive"))
      (node (ref "J16") (pin "100") (pinfunction "B40_100") (pintype "passive"))
      (node (ref "J2") (pin "100") (pinfunction "B40_100") (pintype "passive"))
      (node (ref "J3") (pin "100") (pinfunction "B40_100") (pintype "passive"))
      (node (ref "J4") (pin "100") (pinfunction "B40_100") (pintype "passive"))
      (node (ref "J5") (pin "100") (pinfunction "B40_100") (pintype "passive"))
      (node (ref "J6") (pin "100") (pinfunction "B40_100") (pintype "passive"))
      (node (ref "J7") (pin "100") (pinfunction "B40_100") (pintype "passive"))
      (node (ref "J8") (pin "100") (pinfunction "B40_100") (pintype "passive"))
      (node (ref "J9") (pin "100") (pinfunction "B40_100") (pintype "passive"))
      (node (ref "R23") (pin "1") (pinfunction "1_1") (pintype "passive"))
      (node (ref "U5") (pin "2") (pinfunction "DO1+_2") (pintype "passive"))
    )
    (net (code "135") (name "/bus22_p") (class "Default")
      (node (ref "J1") (pin "101") (pinfunction "B41_101") (pintype "passive"))
      (node (ref "J10") (pin "101") (pinfunction "B41_101") (pintype "passive"))
      (node (ref "J11") (pin "101") (pinfunction "B41_101") (pintype "passive"))
      (node (ref "J12") (pin "101") (pinfunction "B41_101") (pintype "passive"))
      (node (ref "J13") (pin "101") (pinfunction "B41_101") (pintype "passive"))
      (node (ref "J14") (pin "101") (pinfunction "B41_101") (pintype "passive"))
      (node (ref "J15") (pin "101") (pinfunction "B41_101") (pintype "passive"))
      (node (ref "J16") (pin "101") (pinfunction "B41_101") (pintype "passive"))
      (node (ref "J2") (pin "101") (pinfunction "B41_101") (pintype "passive"))
      (node (ref "J3") (pin "101") (pinfunction "B41_101") (pintype "passive"))
      (node (ref "J4") (pin "101") (pinfunction "B41_101") (pintype "passive"))
      (node (ref "J5") (pin "101") (pinfunction "B41_101") (pintype "passive"))
      (node (ref "J6") (pin "101") (pinfunction "B41_101") (pintype "passive"))
      (node (ref "J7") (pin "101") (pinfunction "B41_101") (pintype "passive"))
      (node (ref "J8") (pin "101") (pinfunction "B41_101") (pintype "passive"))
      (node (ref "J9") (pin "101") (pinfunction "B41_101") (pintype "passive"))
      (node (ref "R23") (pin "2") (pinfunction "2_2") (pintype "passive"))
      (node (ref "U5") (pin "3") (pinfunction "DO1-_3") (pintype "passive"))
    )
    (net (code "136") (name "/bus23") (class "Default")
      (node (ref "P7") (pin "25") (pinfunction "25_25") (pintype "passive"))
      (node (ref "U11") (pin "1A32") (pinfunction "V6/B1p_1A32") (pintype "passive"))
      (node (ref "U5") (pin "7") (pinfunction "DI2_7") (pintype "passive"))
    )
    (net (code "137") (name "/bus23_n") (class "Default")
      (node (ref "J1") (pin "103") (pinfunction "B43_103") (pintype "passive"))
      (node (ref "J10") (pin "103") (pinfunction "B43_103") (pintype "passive"))
      (node (ref "J11") (pin "103") (pinfunction "B43_103") (pintype "passive"))
      (node (ref "J12") (pin "103") (pinfunction "B43_103") (pintype "passive"))
      (node (ref "J13") (pin "103") (pinfunction "B43_103") (pintype "passive"))
      (node (ref "J14") (pin "103") (pinfunction "B43_103") (pintype "passive"))
      (node (ref "J15") (pin "103") (pinfunction "B43_103") (pintype "passive"))
      (node (ref "J16") (pin "103") (pinfunction "B43_103") (pintype "passive"))
      (node (ref "J2") (pin "103") (pinfunction "B43_103") (pintype "passive"))
      (node (ref "J3") (pin "103") (pinfunction "B43_103") (pintype "passive"))
      (node (ref "J4") (pin "103") (pinfunction "B43_103") (pintype "passive"))
      (node (ref "J5") (pin "103") (pinfunction "B43_103") (pintype "passive"))
      (node (ref "J6") (pin "103") (pinfunction "B43_103") (pintype "passive"))
      (node (ref "J7") (pin "103") (pinfunction "B43_103") (pintype "passive"))
      (node (ref "J8") (pin "103") (pinfunction "B43_103") (pintype "passive"))
      (node (ref "J9") (pin "103") (pinfunction "B43_103") (pintype "passive"))
      (node (ref "R24") (pin "1") (pinfunction "1_1") (pintype "passive"))
      (node (ref "U5") (pin "6") (pinfunction "DO2+_6") (pintype "passive"))
    )
    (net (code "138") (name "/bus23_p") (class "Default")
      (node (ref "J1") (pin "102") (pinfunction "B42_102") (pintype "passive"))
      (node (ref "J10") (pin "102") (pinfunction "B42_102") (pintype "passive"))
      (node (ref "J11") (pin "102") (pinfunction "B42_102") (pintype "passive"))
      (node (ref "J12") (pin "102") (pinfunction "B42_102") (pintype "passive"))
      (node (ref "J13") (pin "102") (pinfunction "B42_102") (pintype "passive"))
      (node (ref "J14") (pin "102") (pinfunction "B42_102") (pintype "passive"))
      (node (ref "J15") (pin "102") (pinfunction "B42_102") (pintype "passive"))
      (node (ref "J16") (pin "102") (pinfunction "B42_102") (pintype "passive"))
      (node (ref "J2") (pin "102") (pinfunction "B42_102") (pintype "passive"))
      (node (ref "J3") (pin "102") (pinfunction "B42_102") (pintype "passive"))
      (node (ref "J4") (pin "102") (pinfunction "B42_102") (pintype "passive"))
      (node (ref "J5") (pin "102") (pinfunction "B42_102") (pintype "passive"))
      (node (ref "J6") (pin "102") (pinfunction "B42_102") (pintype "passive"))
      (node (ref "J7") (pin "102") (pinfunction "B42_102") (pintype "passive"))
      (node (ref "J8") (pin "102") (pinfunction "B42_102") (pintype "passive"))
      (node (ref "J9") (pin "102") (pinfunction "B42_102") (pintype "passive"))
      (node (ref "R24") (pin "2") (pinfunction "2_2") (pintype "passive"))
      (node (ref "U5") (pin "5") (pinfunction "DO2-_5") (pintype "passive"))
    )
    (net (code "139") (name "/bus24") (class "Default")
      (node (ref "P7") (pin "28") (pinfunction "28_28") (pintype "passive"))
      (node (ref "U11") (pin "1A35") (pinfunction "L6/L16p_1A35") (pintype "passive"))
      (node (ref "U4") (pin "9") (pinfunction "DI3_9") (pintype "passive"))
    )
    (net (code "140") (name "/bus24_n") (class "Default")
      (node (ref "J1") (pin "95") (pinfunction "B35_95") (pintype "passive"))
      (node (ref "J10") (pin "95") (pinfunction "B35_95") (pintype "passive"))
      (node (ref "J11") (pin "95") (pinfunction "B35_95") (pintype "passive"))
      (node (ref "J12") (pin "95") (pinfunction "B35_95") (pintype "passive"))
      (node (ref "J13") (pin "95") (pinfunction "B35_95") (pintype "passive"))
      (node (ref "J14") (pin "95") (pinfunction "B35_95") (pintype "passive"))
      (node (ref "J15") (pin "95") (pinfunction "B35_95") (pintype "passive"))
      (node (ref "J16") (pin "95") (pinfunction "B35_95") (pintype "passive"))
      (node (ref "J2") (pin "95") (pinfunction "B35_95") (pintype "passive"))
      (node (ref "J3") (pin "95") (pinfunction "B35_95") (pintype "passive"))
      (node (ref "J4") (pin "95") (pinfunction "B35_95") (pintype "passive"))
      (node (ref "J5") (pin "95") (pinfunction "B35_95") (pintype "passive"))
      (node (ref "J6") (pin "95") (pinfunction "B35_95") (pintype "passive"))
      (node (ref "J7") (pin "95") (pinfunction "B35_95") (pintype "passive"))
      (node (ref "J8") (pin "95") (pinfunction "B35_95") (pintype "passive"))
      (node (ref "J9") (pin "95") (pinfunction "B35_95") (pintype "passive"))
      (node (ref "R25") (pin "1") (pinfunction "1_1") (pintype "passive"))
      (node (ref "U4") (pin "10") (pinfunction "DO3+_10") (pintype "passive"))
    )
    (net (code "141") (name "/bus24_p") (class "Default")
      (node (ref "J1") (pin "96") (pinfunction "B36_96") (pintype "passive"))
      (node (ref "J10") (pin "96") (pinfunction "B36_96") (pintype "passive"))
      (node (ref "J11") (pin "96") (pinfunction "B36_96") (pintype "passive"))
      (node (ref "J12") (pin "96") (pinfunction "B36_96") (pintype "passive"))
      (node (ref "J13") (pin "96") (pinfunction "B36_96") (pintype "passive"))
      (node (ref "J14") (pin "96") (pinfunction "B36_96") (pintype "passive"))
      (node (ref "J15") (pin "96") (pinfunction "B36_96") (pintype "passive"))
      (node (ref "J16") (pin "96") (pinfunction "B36_96") (pintype "passive"))
      (node (ref "J2") (pin "96") (pinfunction "B36_96") (pintype "passive"))
      (node (ref "J3") (pin "96") (pinfunction "B36_96") (pintype "passive"))
      (node (ref "J4") (pin "96") (pinfunction "B36_96") (pintype "passive"))
      (node (ref "J5") (pin "96") (pinfunction "B36_96") (pintype "passive"))
      (node (ref "J6") (pin "96") (pinfunction "B36_96") (pintype "passive"))
      (node (ref "J7") (pin "96") (pinfunction "B36_96") (pintype "passive"))
      (node (ref "J8") (pin "96") (pinfunction "B36_96") (pintype "passive"))
      (node (ref "J9") (pin "96") (pinfunction "B36_96") (pintype "passive"))
      (node (ref "R25") (pin "2") (pinfunction "2_2") (pintype "passive"))
      (node (ref "U4") (pin "11") (pinfunction "DO3-_11") (pintype "passive"))
    )
    (net (code "142") (name "/bus25") (class "Default")
      (node (ref "P7") (pin "27") (pinfunction "27_27") (pintype "passive"))
      (node (ref "U11") (pin "1A34") (pinfunction "V5/B1n_1A34") (pintype "passive"))
      (node (ref "U4") (pin "15") (pinfunction "DI4_15") (pintype "passive"))
    )
    (net (code "143") (name "/bus25_n") (class "Default")
      (node (ref "J1") (pin "98") (pinfunction "B38_98") (pintype "passive"))
      (node (ref "J10") (pin "98") (pinfunction "B38_98") (pintype "passive"))
      (node (ref "J11") (pin "98") (pinfunction "B38_98") (pintype "passive"))
      (node (ref "J12") (pin "98") (pinfunction "B38_98") (pintype "passive"))
      (node (ref "J13") (pin "98") (pinfunction "B38_98") (pintype "passive"))
      (node (ref "J14") (pin "98") (pinfunction "B38_98") (pintype "passive"))
      (node (ref "J15") (pin "98") (pinfunction "B38_98") (pintype "passive"))
      (node (ref "J16") (pin "98") (pinfunction "B38_98") (pintype "passive"))
      (node (ref "J2") (pin "98") (pinfunction "B38_98") (pintype "passive"))
      (node (ref "J3") (pin "98") (pinfunction "B38_98") (pintype "passive"))
      (node (ref "J4") (pin "98") (pinfunction "B38_98") (pintype "passive"))
      (node (ref "J5") (pin "98") (pinfunction "B38_98") (pintype "passive"))
      (node (ref "J6") (pin "98") (pinfunction "B38_98") (pintype "passive"))
      (node (ref "J7") (pin "98") (pinfunction "B38_98") (pintype "passive"))
      (node (ref "J8") (pin "98") (pinfunction "B38_98") (pintype "passive"))
      (node (ref "J9") (pin "98") (pinfunction "B38_98") (pintype "passive"))
      (node (ref "R26") (pin "1") (pinfunction "1_1") (pintype "passive"))
      (node (ref "U4") (pin "14") (pinfunction "DO4+_14") (pintype "passive"))
    )
    (net (code "144") (name "/bus25_p") (class "Default")
      (node (ref "J1") (pin "97") (pinfunction "B37_97") (pintype "passive"))
      (node (ref "J10") (pin "97") (pinfunction "B37_97") (pintype "passive"))
      (node (ref "J11") (pin "97") (pinfunction "B37_97") (pintype "passive"))
      (node (ref "J12") (pin "97") (pinfunction "B37_97") (pintype "passive"))
      (node (ref "J13") (pin "97") (pinfunction "B37_97") (pintype "passive"))
      (node (ref "J14") (pin "97") (pinfunction "B37_97") (pintype "passive"))
      (node (ref "J15") (pin "97") (pinfunction "B37_97") (pintype "passive"))
      (node (ref "J16") (pin "97") (pinfunction "B37_97") (pintype "passive"))
      (node (ref "J2") (pin "97") (pinfunction "B37_97") (pintype "passive"))
      (node (ref "J3") (pin "97") (pinfunction "B37_97") (pintype "passive"))
      (node (ref "J4") (pin "97") (pinfunction "B37_97") (pintype "passive"))
      (node (ref "J5") (pin "97") (pinfunction "B37_97") (pintype "passive"))
      (node (ref "J6") (pin "97") (pinfunction "B37_97") (pintype "passive"))
      (node (ref "J7") (pin "97") (pinfunction "B37_97") (pintype "passive"))
      (node (ref "J8") (pin "97") (pinfunction "B37_97") (pintype "passive"))
      (node (ref "J9") (pin "97") (pinfunction "B37_97") (pintype "passive"))
      (node (ref "R26") (pin "2") (pinfunction "2_2") (pintype "passive"))
      (node (ref "U4") (pin "13") (pinfunction "DO4-_13") (pintype "passive"))
    )
    (net (code "145") (name "/bus26") (class "Default")
      (node (ref "P7") (pin "30") (pinfunction "30_30") (pintype "passive"))
      (node (ref "U11") (pin "1B3") (pinfunction "M2/L17p_1B3") (pintype "passive"))
      (node (ref "U4") (pin "1") (pinfunction "DI1_1") (pintype "passive"))
    )
    (net (code "146") (name "/bus26_n") (class "Default")
      (node (ref "J1") (pin "91") (pinfunction "B31_91") (pintype "passive"))
      (node (ref "J10") (pin "91") (pinfunction "B31_91") (pintype "passive"))
      (node (ref "J11") (pin "91") (pinfunction "B31_91") (pintype "passive"))
      (node (ref "J12") (pin "91") (pinfunction "B31_91") (pintype "passive"))
      (node (ref "J13") (pin "91") (pinfunction "B31_91") (pintype "passive"))
      (node (ref "J14") (pin "91") (pinfunction "B31_91") (pintype "passive"))
      (node (ref "J15") (pin "91") (pinfunction "B31_91") (pintype "passive"))
      (node (ref "J16") (pin "91") (pinfunction "B31_91") (pintype "passive"))
      (node (ref "J2") (pin "91") (pinfunction "B31_91") (pintype "passive"))
      (node (ref "J3") (pin "91") (pinfunction "B31_91") (pintype "passive"))
      (node (ref "J4") (pin "91") (pinfunction "B31_91") (pintype "passive"))
      (node (ref "J5") (pin "91") (pinfunction "B31_91") (pintype "passive"))
      (node (ref "J6") (pin "91") (pinfunction "B31_91") (pintype "passive"))
      (node (ref "J7") (pin "91") (pinfunction "B31_91") (pintype "passive"))
      (node (ref "J8") (pin "91") (pinfunction "B31_91") (pintype "passive"))
      (node (ref "J9") (pin "91") (pinfunction "B31_91") (pintype "passive"))
      (node (ref "R27") (pin "1") (pinfunction "1_1") (pintype "passive"))
      (node (ref "U4") (pin "2") (pinfunction "DO1+_2") (pintype "passive"))
    )
    (net (code "147") (name "/bus26_p") (class "Default")
      (node (ref "J1") (pin "92") (pinfunction "B32_92") (pintype "passive"))
      (node (ref "J10") (pin "92") (pinfunction "B32_92") (pintype "passive"))
      (node (ref "J11") (pin "92") (pinfunction "B32_92") (pintype "passive"))
      (node (ref "J12") (pin "92") (pinfunction "B32_92") (pintype "passive"))
      (node (ref "J13") (pin "92") (pinfunction "B32_92") (pintype "passive"))
      (node (ref "J14") (pin "92") (pinfunction "B32_92") (pintype "passive"))
      (node (ref "J15") (pin "92") (pinfunction "B32_92") (pintype "passive"))
      (node (ref "J16") (pin "92") (pinfunction "B32_92") (pintype "passive"))
      (node (ref "J2") (pin "92") (pinfunction "B32_92") (pintype "passive"))
      (node (ref "J3") (pin "92") (pinfunction "B32_92") (pintype "passive"))
      (node (ref "J4") (pin "92") (pinfunction "B32_92") (pintype "passive"))
      (node (ref "J5") (pin "92") (pinfunction "B32_92") (pintype "passive"))
      (node (ref "J6") (pin "92") (pinfunction "B32_92") (pintype "passive"))
      (node (ref "J7") (pin "92") (pinfunction "B32_92") (pintype "passive"))
      (node (ref "J8") (pin "92") (pinfunction "B32_92") (pintype "passive"))
      (node (ref "J9") (pin "92") (pinfunction "B32_92") (pintype "passive"))
      (node (ref "R27") (pin "2") (pinfunction "2_2") (pintype "passive"))
      (node (ref "U4") (pin "3") (pinfunction "DO1-_3") (pintype "passive"))
    )
    (net (code "148") (name "/bus27") (class "Default")
      (node (ref "P7") (pin "29") (pinfunction "29_29") (pintype "passive"))
      (node (ref "U11") (pin "1A37") (pinfunction "M6/L16n_1A37") (pintype "passive"))
      (node (ref "U4") (pin "7") (pinfunction "DI2_7") (pintype "passive"))
    )
    (net (code "149") (name "/bus27_n") (class "Default")
      (node (ref "J1") (pin "94") (pinfunction "B34_94") (pintype "passive"))
      (node (ref "J10") (pin "94") (pinfunction "B34_94") (pintype "passive"))
      (node (ref "J11") (pin "94") (pinfunction "B34_94") (pintype "passive"))
      (node (ref "J12") (pin "94") (pinfunction "B34_94") (pintype "passive"))
      (node (ref "J13") (pin "94") (pinfunction "B34_94") (pintype "passive"))
      (node (ref "J14") (pin "94") (pinfunction "B34_94") (pintype "passive"))
      (node (ref "J15") (pin "94") (pinfunction "B34_94") (pintype "passive"))
      (node (ref "J16") (pin "94") (pinfunction "B34_94") (pintype "passive"))
      (node (ref "J2") (pin "94") (pinfunction "B34_94") (pintype "passive"))
      (node (ref "J3") (pin "94") (pinfunction "B34_94") (pintype "passive"))
      (node (ref "J4") (pin "94") (pinfunction "B34_94") (pintype "passive"))
      (node (ref "J5") (pin "94") (pinfunction "B34_94") (pintype "passive"))
      (node (ref "J6") (pin "94") (pinfunction "B34_94") (pintype "passive"))
      (node (ref "J7") (pin "94") (pinfunction "B34_94") (pintype "passive"))
      (node (ref "J8") (pin "94") (pinfunction "B34_94") (pintype "passive"))
      (node (ref "J9") (pin "94") (pinfunction "B34_94") (pintype "passive"))
      (node (ref "R28") (pin "1") (pinfunction "1_1") (pintype "passive"))
      (node (ref "U4") (pin "6") (pinfunction "DO2+_6") (pintype "passive"))
    )
    (net (code "150") (name "/bus27_p") (class "Default")
      (node (ref "J1") (pin "93") (pinfunction "B33_93") (pintype "passive"))
      (node (ref "J10") (pin "93") (pinfunction "B33_93") (pintype "passive"))
      (node (ref "J11") (pin "93") (pinfunction "B33_93") (pintype "passive"))
      (node (ref "J12") (pin "93") (pinfunction "B33_93") (pintype "passive"))
      (node (ref "J13") (pin "93") (pinfunction "B33_93") (pintype "passive"))
      (node (ref "J14") (pin "93") (pinfunction "B33_93") (pintype "passive"))
      (node (ref "J15") (pin "93") (pinfunction "B33_93") (pintype "passive"))
      (node (ref "J16") (pin "93") (pinfunction "B33_93") (pintype "passive"))
      (node (ref "J2") (pin "93") (pinfunction "B33_93") (pintype "passive"))
      (node (ref "J3") (pin "93") (pinfunction "B33_93") (pintype "passive"))
      (node (ref "J4") (pin "93") (pinfunction "B33_93") (pintype "passive"))
      (node (ref "J5") (pin "93") (pinfunction "B33_93") (pintype "passive"))
      (node (ref "J6") (pin "93") (pinfunction "B33_93") (pintype "passive"))
      (node (ref "J7") (pin "93") (pinfunction "B33_93") (pintype "passive"))
      (node (ref "J8") (pin "93") (pinfunction "B33_93") (pintype "passive"))
      (node (ref "J9") (pin "93") (pinfunction "B33_93") (pintype "passive"))
      (node (ref "R28") (pin "2") (pinfunction "2_2") (pintype "passive"))
      (node (ref "U4") (pin "5") (pinfunction "DO2-_5") (pintype "passive"))
    )
    (net (code "151") (name "/bus28") (class "Default")
      (node (ref "P7") (pin "31") (pinfunction "31_31") (pintype "passive"))
      (node (ref "U11") (pin "1B5") (pinfunction "M1/L17n_1B5") (pintype "passive"))
      (node (ref "U3") (pin "9") (pinfunction "DI3_9") (pintype "passive"))
    )
    (net (code "152") (name "/bus28_n") (class "Default")
      (node (ref "J1") (pin "86") (pinfunction "B26_86") (pintype "passive"))
      (node (ref "J10") (pin "86") (pinfunction "B26_86") (pintype "passive"))
      (node (ref "J11") (pin "86") (pinfunction "B26_86") (pintype "passive"))
      (node (ref "J12") (pin "86") (pinfunction "B26_86") (pintype "passive"))
      (node (ref "J13") (pin "86") (pinfunction "B26_86") (pintype "passive"))
      (node (ref "J14") (pin "86") (pinfunction "B26_86") (pintype "passive"))
      (node (ref "J15") (pin "86") (pinfunction "B26_86") (pintype "passive"))
      (node (ref "J16") (pin "86") (pinfunction "B26_86") (pintype "passive"))
      (node (ref "J2") (pin "86") (pinfunction "B26_86") (pintype "passive"))
      (node (ref "J3") (pin "86") (pinfunction "B26_86") (pintype "passive"))
      (node (ref "J4") (pin "86") (pinfunction "B26_86") (pintype "passive"))
      (node (ref "J5") (pin "86") (pinfunction "B26_86") (pintype "passive"))
      (node (ref "J6") (pin "86") (pinfunction "B26_86") (pintype "passive"))
      (node (ref "J7") (pin "86") (pinfunction "B26_86") (pintype "passive"))
      (node (ref "J8") (pin "86") (pinfunction "B26_86") (pintype "passive"))
      (node (ref "J9") (pin "86") (pinfunction "B26_86") (pintype "passive"))
      (node (ref "R29") (pin "1") (pinfunction "1_1") (pintype "passive"))
      (node (ref "U3") (pin "10") (pinfunction "DO3+_10") (pintype "passive"))
    )
    (net (code "153") (name "/bus28_p") (class "Default")
      (node (ref "J1") (pin "87") (pinfunction "B27_87") (pintype "passive"))
      (node (ref "J10") (pin "87") (pinfunction "B27_87") (pintype "passive"))
      (node (ref "J11") (pin "87") (pinfunction "B27_87") (pintype "passive"))
      (node (ref "J12") (pin "87") (pinfunction "B27_87") (pintype "passive"))
      (node (ref "J13") (pin "87") (pinfunction "B27_87") (pintype "passive"))
      (node (ref "J14") (pin "87") (pinfunction "B27_87") (pintype "passive"))
      (node (ref "J15") (pin "87") (pinfunction "B27_87") (pintype "passive"))
      (node (ref "J16") (pin "87") (pinfunction "B27_87") (pintype "passive"))
      (node (ref "J2") (pin "87") (pinfunction "B27_87") (pintype "passive"))
      (node (ref "J3") (pin "87") (pinfunction "B27_87") (pintype "passive"))
      (node (ref "J4") (pin "87") (pinfunction "B27_87") (pintype "passive"))
      (node (ref "J5") (pin "87") (pinfunction "B27_87") (pintype "passive"))
      (node (ref "J6") (pin "87") (pinfunction "B27_87") (pintype "passive"))
      (node (ref "J7") (pin "87") (pinfunction "B27_87") (pintype "passive"))
      (node (ref "J8") (pin "87") (pinfunction "B27_87") (pintype "passive"))
      (node (ref "J9") (pin "87") (pinfunction "B27_87") (pintype "passive"))
      (node (ref "R29") (pin "2") (pinfunction "2_2") (pintype "passive"))
      (node (ref "U3") (pin "11") (pinfunction "DO3-_11") (pintype "passive"))
    )
    (net (code "154") (name "/bus29") (class "Default")
      (node (ref "P7") (pin "32") (pinfunction "32_32") (pintype "passive"))
      (node (ref "U11") (pin "1B4") (pinfunction "U7/B2p_1B4") (pintype "passive"))
      (node (ref "U3") (pin "15") (pinfunction "DI4_15") (pintype "passive"))
    )
    (net (code "155") (name "/bus29_n") (class "Default")
      (node (ref "J1") (pin "89") (pinfunction "B29_89") (pintype "passive"))
      (node (ref "J10") (pin "89") (pinfunction "B29_89") (pintype "passive"))
      (node (ref "J11") (pin "89") (pinfunction "B29_89") (pintype "passive"))
      (node (ref "J12") (pin "89") (pinfunction "B29_89") (pintype "passive"))
      (node (ref "J13") (pin "89") (pinfunction "B29_89") (pintype "passive"))
      (node (ref "J14") (pin "89") (pinfunction "B29_89") (pintype "passive"))
      (node (ref "J15") (pin "89") (pinfunction "B29_89") (pintype "passive"))
      (node (ref "J16") (pin "89") (pinfunction "B29_89") (pintype "passive"))
      (node (ref "J2") (pin "89") (pinfunction "B29_89") (pintype "passive"))
      (node (ref "J3") (pin "89") (pinfunction "B29_89") (pintype "passive"))
      (node (ref "J4") (pin "89") (pinfunction "B29_89") (pintype "passive"))
      (node (ref "J5") (pin "89") (pinfunction "B29_89") (pintype "passive"))
      (node (ref "J6") (pin "89") (pinfunction "B29_89") (pintype "passive"))
      (node (ref "J7") (pin "89") (pinfunction "B29_89") (pintype "passive"))
      (node (ref "J8") (pin "89") (pinfunction "B29_89") (pintype "passive"))
      (node (ref "J9") (pin "89") (pinfunction "B29_89") (pintype "passive"))
      (node (ref "R30") (pin "1") (pinfunction "1_1") (pintype "passive"))
      (node (ref "U3") (pin "14") (pinfunction "DO4+_14") (pintype "passive"))
    )
    (net (code "156") (name "/bus29_p") (class "Default")
      (node (ref "J1") (pin "88") (pinfunction "B28_88") (pintype "passive"))
      (node (ref "J10") (pin "88") (pinfunction "B28_88") (pintype "passive"))
      (node (ref "J11") (pin "88") (pinfunction "B28_88") (pintype "passive"))
      (node (ref "J12") (pin "88") (pinfunction "B28_88") (pintype "passive"))
      (node (ref "J13") (pin "88") (pinfunction "B28_88") (pintype "passive"))
      (node (ref "J14") (pin "88") (pinfunction "B28_88") (pintype "passive"))
      (node (ref "J15") (pin "88") (pinfunction "B28_88") (pintype "passive"))
      (node (ref "J16") (pin "88") (pinfunction "B28_88") (pintype "passive"))
      (node (ref "J2") (pin "88") (pinfunction "B28_88") (pintype "passive"))
      (node (ref "J3") (pin "88") (pinfunction "B28_88") (pintype "passive"))
      (node (ref "J4") (pin "88") (pinfunction "B28_88") (pintype "passive"))
      (node (ref "J5") (pin "88") (pinfunction "B28_88") (pintype "passive"))
      (node (ref "J6") (pin "88") (pinfunction "B28_88") (pintype "passive"))
      (node (ref "J7") (pin "88") (pinfunction "B28_88") (pintype "passive"))
      (node (ref "J8") (pin "88") (pinfunction "B28_88") (pintype "passive"))
      (node (ref "J9") (pin "88") (pinfunction "B28_88") (pintype "passive"))
      (node (ref "R30") (pin "2") (pinfunction "2_2") (pintype "passive"))
      (node (ref "U3") (pin "13") (pinfunction "DO4-_13") (pintype "passive"))
    )
    (net (code "157") (name "/bus30") (class "Default")
      (node (ref "P7") (pin "34") (pinfunction "34_34") (pintype "passive"))
      (node (ref "U11") (pin "1B7") (pinfunction "M4/L18p_1B7") (pintype "passive"))
      (node (ref "U3") (pin "1") (pinfunction "DI1_1") (pintype "passive"))
    )
    (net (code "158") (name "/bus30_n") (class "Default")
      (node (ref "J1") (pin "82") (pinfunction "B22_82") (pintype "passive"))
      (node (ref "J10") (pin "82") (pinfunction "B22_82") (pintype "passive"))
      (node (ref "J11") (pin "82") (pinfunction "B22_82") (pintype "passive"))
      (node (ref "J12") (pin "82") (pinfunction "B22_82") (pintype "passive"))
      (node (ref "J13") (pin "82") (pinfunction "B22_82") (pintype "passive"))
      (node (ref "J14") (pin "82") (pinfunction "B22_82") (pintype "passive"))
      (node (ref "J15") (pin "82") (pinfunction "B22_82") (pintype "passive"))
      (node (ref "J16") (pin "82") (pinfunction "B22_82") (pintype "passive"))
      (node (ref "J2") (pin "82") (pinfunction "B22_82") (pintype "passive"))
      (node (ref "J3") (pin "82") (pinfunction "B22_82") (pintype "passive"))
      (node (ref "J4") (pin "82") (pinfunction "B22_82") (pintype "passive"))
      (node (ref "J5") (pin "82") (pinfunction "B22_82") (pintype "passive"))
      (node (ref "J6") (pin "82") (pinfunction "B22_82") (pintype "passive"))
      (node (ref "J7") (pin "82") (pinfunction "B22_82") (pintype "passive"))
      (node (ref "J8") (pin "82") (pinfunction "B22_82") (pintype "passive"))
      (node (ref "J9") (pin "82") (pinfunction "B22_82") (pintype "passive"))
      (node (ref "R31") (pin "1") (pinfunction "1_1") (pintype "passive"))
      (node (ref "U3") (pin "2") (pinfunction "DO1+_2") (pintype "passive"))
    )
    (net (code "159") (name "/bus30_p") (class "Default")
      (node (ref "J1") (pin "83") (pinfunction "B23_83") (pintype "passive"))
      (node (ref "J10") (pin "83") (pinfunction "B23_83") (pintype "passive"))
      (node (ref "J11") (pin "83") (pinfunction "B23_83") (pintype "passive"))
      (node (ref "J12") (pin "83") (pinfunction "B23_83") (pintype "passive"))
      (node (ref "J13") (pin "83") (pinfunction "B23_83") (pintype "passive"))
      (node (ref "J14") (pin "83") (pinfunction "B23_83") (pintype "passive"))
      (node (ref "J15") (pin "83") (pinfunction "B23_83") (pintype "passive"))
      (node (ref "J16") (pin "83") (pinfunction "B23_83") (pintype "passive"))
      (node (ref "J2") (pin "83") (pinfunction "B23_83") (pintype "passive"))
      (node (ref "J3") (pin "83") (pinfunction "B23_83") (pintype "passive"))
      (node (ref "J4") (pin "83") (pinfunction "B23_83") (pintype "passive"))
      (node (ref "J5") (pin "83") (pinfunction "B23_83") (pintype "passive"))
      (node (ref "J6") (pin "83") (pinfunction "B23_83") (pintype "passive"))
      (node (ref "J7") (pin "83") (pinfunction "B23_83") (pintype "passive"))
      (node (ref "J8") (pin "83") (pinfunction "B23_83") (pintype "passive"))
      (node (ref "J9") (pin "83") (pinfunction "B23_83") (pintype "passive"))
      (node (ref "R31") (pin "2") (pinfunction "2_2") (pintype "passive"))
      (node (ref "U3") (pin "3") (pinfunction "DO1-_3") (pintype "passive"))
    )
    (net (code "160") (name "/bus31") (class "Default")
      (node (ref "P7") (pin "33") (pinfunction "33_33") (pintype "passive"))
      (node (ref "U11") (pin "1B6") (pinfunction "U8/B2n_1B6") (pintype "passive"))
      (node (ref "U3") (pin "7") (pinfunction "DI2_7") (pintype "passive"))
    )
    (net (code "161") (name "/bus31_n") (class "Default")
      (node (ref "J1") (pin "85") (pinfunction "B25_85") (pintype "passive"))
      (node (ref "J10") (pin "85") (pinfunction "B25_85") (pintype "passive"))
      (node (ref "J11") (pin "85") (pinfunction "B25_85") (pintype "passive"))
      (node (ref "J12") (pin "85") (pinfunction "B25_85") (pintype "passive"))
      (node (ref "J13") (pin "85") (pinfunction "B25_85") (pintype "passive"))
      (node (ref "J14") (pin "85") (pinfunction "B25_85") (pintype "passive"))
      (node (ref "J15") (pin "85") (pinfunction "B25_85") (pintype "passive"))
      (node (ref "J16") (pin "85") (pinfunction "B25_85") (pintype "passive"))
      (node (ref "J2") (pin "85") (pinfunction "B25_85") (pintype "passive"))
      (node (ref "J3") (pin "85") (pinfunction "B25_85") (pintype "passive"))
      (node (ref "J4") (pin "85") (pinfunction "B25_85") (pintype "passive"))
      (node (ref "J5") (pin "85") (pinfunction "B25_85") (pintype "passive"))
      (node (ref "J6") (pin "85") (pinfunction "B25_85") (pintype "passive"))
      (node (ref "J7") (pin "85") (pinfunction "B25_85") (pintype "passive"))
      (node (ref "J8") (pin "85") (pinfunction "B25_85") (pintype "passive"))
      (node (ref "J9") (pin "85") (pinfunction "B25_85") (pintype "passive"))
      (node (ref "R32") (pin "1") (pinfunction "1_1") (pintype "passive"))
      (node (ref "U3") (pin "6") (pinfunction "DO2+_6") (pintype "passive"))
    )
    (net (code "162") (name "/bus31_p") (class "Default")
      (node (ref "J1") (pin "84") (pinfunction "B24_84") (pintype "passive"))
      (node (ref "J10") (pin "84") (pinfunction "B24_84") (pintype "passive"))
      (node (ref "J11") (pin "84") (pinfunction "B24_84") (pintype "passive"))
      (node (ref "J12") (pin "84") (pinfunction "B24_84") (pintype "passive"))
      (node (ref "J13") (pin "84") (pinfunction "B24_84") (pintype "passive"))
      (node (ref "J14") (pin "84") (pinfunction "B24_84") (pintype "passive"))
      (node (ref "J15") (pin "84") (pinfunction "B24_84") (pintype "passive"))
      (node (ref "J16") (pin "84") (pinfunction "B24_84") (pintype "passive"))
      (node (ref "J2") (pin "84") (pinfunction "B24_84") (pintype "passive"))
      (node (ref "J3") (pin "84") (pinfunction "B24_84") (pintype "passive"))
      (node (ref "J4") (pin "84") (pinfunction "B24_84") (pintype "passive"))
      (node (ref "J5") (pin "84") (pinfunction "B24_84") (pintype "passive"))
      (node (ref "J6") (pin "84") (pinfunction "B24_84") (pintype "passive"))
      (node (ref "J7") (pin "84") (pinfunction "B24_84") (pintype "passive"))
      (node (ref "J8") (pin "84") (pinfunction "B24_84") (pintype "passive"))
      (node (ref "J9") (pin "84") (pinfunction "B24_84") (pintype "passive"))
      (node (ref "R32") (pin "2") (pinfunction "2_2") (pintype "passive"))
      (node (ref "U3") (pin "5") (pinfunction "DO2-_5") (pintype "passive"))
    )
    (net (code "163") (name "/bus32") (class "Default")
      (node (ref "P9") (pin "6") (pinfunction "6_6") (pintype "passive"))
      (node (ref "U11") (pin "1B13") (pinfunction "N1/L19n_1B13") (pintype "passive"))
      (node (ref "U2") (pin "11") (pinfunction "YD_11") (pintype "passive"))
    )
    (net (code "164") (name "/bus32_n") (class "Default")
      (node (ref "J1") (pin "15") (pinfunction "A15_15") (pintype "passive"))
      (node (ref "J10") (pin "15") (pinfunction "A15_15") (pintype "passive"))
      (node (ref "J11") (pin "15") (pinfunction "A15_15") (pintype "passive"))
      (node (ref "J12") (pin "15") (pinfunction "A15_15") (pintype "passive"))
      (node (ref "J13") (pin "15") (pinfunction "A15_15") (pintype "passive"))
      (node (ref "J14") (pin "15") (pinfunction "A15_15") (pintype "passive"))
      (node (ref "J15") (pin "15") (pinfunction "A15_15") (pintype "passive"))
      (node (ref "J16") (pin "15") (pinfunction "A15_15") (pintype "passive"))
      (node (ref "J2") (pin "15") (pinfunction "A15_15") (pintype "passive"))
      (node (ref "J3") (pin "15") (pinfunction "A15_15") (pintype "passive"))
      (node (ref "J4") (pin "15") (pinfunction "A15_15") (pintype "passive"))
      (node (ref "J5") (pin "15") (pinfunction "A15_15") (pintype "passive"))
      (node (ref "J6") (pin "15") (pinfunction "A15_15") (pintype "passive"))
      (node (ref "J7") (pin "15") (pinfunction "A15_15") (pintype "passive"))
      (node (ref "J8") (pin "15") (pinfunction "A15_15") (pintype "passive"))
      (node (ref "J9") (pin "15") (pinfunction "A15_15") (pintype "passive"))
      (node (ref "R33") (pin "1") (pinfunction "1_1") (pintype "passive"))
      (node (ref "U2") (pin "10") (pinfunction "D+_10") (pintype "passive"))
    )
    (net (code "165") (name "/bus32_p") (class "Default")
      (node (ref "J1") (pin "16") (pinfunction "A16_16") (pintype "passive"))
      (node (ref "J10") (pin "16") (pinfunction "A16_16") (pintype "passive"))
      (node (ref "J11") (pin "16") (pinfunction "A16_16") (pintype "passive"))
      (node (ref "J12") (pin "16") (pinfunction "A16_16") (pintype "passive"))
      (node (ref "J13") (pin "16") (pinfunction "A16_16") (pintype "passive"))
      (node (ref "J14") (pin "16") (pinfunction "A16_16") (pintype "passive"))
      (node (ref "J15") (pin "16") (pinfunction "A16_16") (pintype "passive"))
      (node (ref "J16") (pin "16") (pinfunction "A16_16") (pintype "passive"))
      (node (ref "J2") (pin "16") (pinfunction "A16_16") (pintype "passive"))
      (node (ref "J3") (pin "16") (pinfunction "A16_16") (pintype "passive"))
      (node (ref "J4") (pin "16") (pinfunction "A16_16") (pintype "passive"))
      (node (ref "J5") (pin "16") (pinfunction "A16_16") (pintype "passive"))
      (node (ref "J6") (pin "16") (pinfunction "A16_16") (pintype "passive"))
      (node (ref "J7") (pin "16") (pinfunction "A16_16") (pintype "passive"))
      (node (ref "J8") (pin "16") (pinfunction "A16_16") (pintype "passive"))
      (node (ref "J9") (pin "16") (pinfunction "A16_16") (pintype "passive"))
      (node (ref "R33") (pin "2") (pinfunction "2_2") (pintype "passive"))
      (node (ref "U2") (pin "9") (pinfunction "D-_9") (pintype "passive"))
    )
    (net (code "166") (name "/bus33") (class "Default")
      (node (ref "P9") (pin "5") (pinfunction "5_5") (pintype "passive"))
      (node (ref "U11") (pin "1B12") (pinfunction "AA5/B5p_1B12") (pintype "passive"))
      (node (ref "U2") (pin "13") (pinfunction "YB_13") (pintype "passive"))
    )
    (net (code "167") (name "/bus33_n") (class "Default")
      (node (ref "J1") (pin "14") (pinfunction "A14_14") (pintype "passive"))
      (node (ref "J10") (pin "14") (pinfunction "A14_14") (pintype "passive"))
      (node (ref "J11") (pin "14") (pinfunction "A14_14") (pintype "passive"))
      (node (ref "J12") (pin "14") (pinfunction "A14_14") (pintype "passive"))
      (node (ref "J13") (pin "14") (pinfunction "A14_14") (pintype "passive"))
      (node (ref "J14") (pin "14") (pinfunction "A14_14") (pintype "passive"))
      (node (ref "J15") (pin "14") (pinfunction "A14_14") (pintype "passive"))
      (node (ref "J16") (pin "14") (pinfunction "A14_14") (pintype "passive"))
      (node (ref "J2") (pin "14") (pinfunction "A14_14") (pintype "passive"))
      (node (ref "J3") (pin "14") (pinfunction "A14_14") (pintype "passive"))
      (node (ref "J4") (pin "14") (pinfunction "A14_14") (pintype "passive"))
      (node (ref "J5") (pin "14") (pinfunction "A14_14") (pintype "passive"))
      (node (ref "J6") (pin "14") (pinfunction "A14_14") (pintype "passive"))
      (node (ref "J7") (pin "14") (pinfunction "A14_14") (pintype "passive"))
      (node (ref "J8") (pin "14") (pinfunction "A14_14") (pintype "passive"))
      (node (ref "J9") (pin "14") (pinfunction "A14_14") (pintype "passive"))
      (node (ref "R34") (pin "1") (pinfunction "1_1") (pintype "passive"))
      (node (ref "U2") (pin "14") (pinfunction "B+_14") (pintype "passive"))
    )
    (net (code "168") (name "/bus33_p") (class "Default")
      (node (ref "J1") (pin "13") (pinfunction "A13_13") (pintype "passive"))
      (node (ref "J10") (pin "13") (pinfunction "A13_13") (pintype "passive"))
      (node (ref "J11") (pin "13") (pinfunction "A13_13") (pintype "passive"))
      (node (ref "J12") (pin "13") (pinfunction "A13_13") (pintype "passive"))
      (node (ref "J13") (pin "13") (pinfunction "A13_13") (pintype "passive"))
      (node (ref "J14") (pin "13") (pinfunction "A13_13") (pintype "passive"))
      (node (ref "J15") (pin "13") (pinfunction "A13_13") (pintype "passive"))
      (node (ref "J16") (pin "13") (pinfunction "A13_13") (pintype "passive"))
      (node (ref "J2") (pin "13") (pinfunction "A13_13") (pintype "passive"))
      (node (ref "J3") (pin "13") (pinfunction "A13_13") (pintype "passive"))
      (node (ref "J4") (pin "13") (pinfunction "A13_13") (pintype "passive"))
      (node (ref "J5") (pin "13") (pinfunction "A13_13") (pintype "passive"))
      (node (ref "J6") (pin "13") (pinfunction "A13_13") (pintype "passive"))
      (node (ref "J7") (pin "13") (pinfunction "A13_13") (pintype "passive"))
      (node (ref "J8") (pin "13") (pinfunction "A13_13") (pintype "passive"))
      (node (ref "J9") (pin "13") (pinfunction "A13_13") (pintype "passive"))
      (node (ref "R34") (pin "2") (pinfunction "2_2") (pintype "passive"))
      (node (ref "U2") (pin "15") (pinfunction "B-_15") (pintype "passive"))
    )
    (net (code "169") (name "/bus34") (class "Default")
      (node (ref "P9") (pin "8") (pinfunction "8_8") (pintype "passive"))
      (node (ref "U11") (pin "1B15") (pinfunction "P2/L20p_1B15") (pintype "passive"))
      (node (ref "U2") (pin "3") (pinfunction "YA_3") (pintype "passive"))
    )
    (net (code "170") (name "/bus34_n") (class "Default")
      (node (ref "J1") (pin "19") (pinfunction "A19_19") (pintype "passive"))
      (node (ref "J10") (pin "19") (pinfunction "A19_19") (pintype "passive"))
      (node (ref "J11") (pin "19") (pinfunction "A19_19") (pintype "passive"))
      (node (ref "J12") (pin "19") (pinfunction "A19_19") (pintype "passive"))
      (node (ref "J13") (pin "19") (pinfunction "A19_19") (pintype "passive"))
      (node (ref "J14") (pin "19") (pinfunction "A19_19") (pintype "passive"))
      (node (ref "J15") (pin "19") (pinfunction "A19_19") (pintype "passive"))
      (node (ref "J16") (pin "19") (pinfunction "A19_19") (pintype "passive"))
      (node (ref "J2") (pin "19") (pinfunction "A19_19") (pintype "passive"))
      (node (ref "J3") (pin "19") (pinfunction "A19_19") (pintype "passive"))
      (node (ref "J4") (pin "19") (pinfunction "A19_19") (pintype "passive"))
      (node (ref "J5") (pin "19") (pinfunction "A19_19") (pintype "passive"))
      (node (ref "J6") (pin "19") (pinfunction "A19_19") (pintype "passive"))
      (node (ref "J7") (pin "19") (pinfunction "A19_19") (pintype "passive"))
      (node (ref "J8") (pin "19") (pinfunction "A19_19") (pintype "passive"))
      (node (ref "J9") (pin "19") (pinfunction "A19_19") (pintype "passive"))
      (node (ref "R35") (pin "1") (pinfunction "1_1") (pintype "passive"))
      (node (ref "U2") (pin "2") (pinfunction "A+_2") (pintype "passive"))
    )
    (net (code "171") (name "/bus34_p") (class "Default")
      (node (ref "J1") (pin "20") (pinfunction "A20_20") (pintype "passive"))
      (node (ref "J10") (pin "20") (pinfunction "A20_20") (pintype "passive"))
      (node (ref "J11") (pin "20") (pinfunction "A20_20") (pintype "passive"))
      (node (ref "J12") (pin "20") (pinfunction "A20_20") (pintype "passive"))
      (node (ref "J13") (pin "20") (pinfunction "A20_20") (pintype "passive"))
      (node (ref "J14") (pin "20") (pinfunction "A20_20") (pintype "passive"))
      (node (ref "J15") (pin "20") (pinfunction "A20_20") (pintype "passive"))
      (node (ref "J16") (pin "20") (pinfunction "A20_20") (pintype "passive"))
      (node (ref "J2") (pin "20") (pinfunction "A20_20") (pintype "passive"))
      (node (ref "J3") (pin "20") (pinfunction "A20_20") (pintype "passive"))
      (node (ref "J4") (pin "20") (pinfunction "A20_20") (pintype "passive"))
      (node (ref "J5") (pin "20") (pinfunction "A20_20") (pintype "passive"))
      (node (ref "J6") (pin "20") (pinfunction "A20_20") (pintype "passive"))
      (node (ref "J7") (pin "20") (pinfunction "A20_20") (pintype "passive"))
      (node (ref "J8") (pin "20") (pinfunction "A20_20") (pintype "passive"))
      (node (ref "J9") (pin "20") (pinfunction "A20_20") (pintype "passive"))
      (node (ref "R35") (pin "2") (pinfunction "2_2") (pintype "passive"))
      (node (ref "U2") (pin "1") (pinfunction "A-_1") (pintype "passive"))
    )
    (net (code "172") (name "/bus35") (class "Default")
      (node (ref "P9") (pin "7") (pinfunction "7_7") (pintype "passive"))
      (node (ref "U11") (pin "1B14") (pinfunction "AA6/B5n_1B14") (pintype "passive"))
      (node (ref "U2") (pin "5") (pinfunction "YC_5") (pintype "passive"))
    )
    (net (code "173") (name "/bus35_n") (class "Default")
      (node (ref "J1") (pin "18") (pinfunction "A18_18") (pintype "passive"))
      (node (ref "J10") (pin "18") (pinfunction "A18_18") (pintype "passive"))
      (node (ref "J11") (pin "18") (pinfunction "A18_18") (pintype "passive"))
      (node (ref "J12") (pin "18") (pinfunction "A18_18") (pintype "passive"))
      (node (ref "J13") (pin "18") (pinfunction "A18_18") (pintype "passive"))
      (node (ref "J14") (pin "18") (pinfunction "A18_18") (pintype "passive"))
      (node (ref "J15") (pin "18") (pinfunction "A18_18") (pintype "passive"))
      (node (ref "J16") (pin "18") (pinfunction "A18_18") (pintype "passive"))
      (node (ref "J2") (pin "18") (pinfunction "A18_18") (pintype "passive"))
      (node (ref "J3") (pin "18") (pinfunction "A18_18") (pintype "passive"))
      (node (ref "J4") (pin "18") (pinfunction "A18_18") (pintype "passive"))
      (node (ref "J5") (pin "18") (pinfunction "A18_18") (pintype "passive"))
      (node (ref "J6") (pin "18") (pinfunction "A18_18") (pintype "passive"))
      (node (ref "J7") (pin "18") (pinfunction "A18_18") (pintype "passive"))
      (node (ref "J8") (pin "18") (pinfunction "A18_18") (pintype "passive"))
      (node (ref "J9") (pin "18") (pinfunction "A18_18") (pintype "passive"))
      (node (ref "R36") (pin "1") (pinfunction "1_1") (pintype "passive"))
      (node (ref "U2") (pin "6") (pinfunction "C+_6") (pintype "passive"))
    )
    (net (code "174") (name "/bus35_p") (class "Default")
      (node (ref "J1") (pin "17") (pinfunction "A17_17") (pintype "passive"))
      (node (ref "J10") (pin "17") (pinfunction "A17_17") (pintype "passive"))
      (node (ref "J11") (pin "17") (pinfunction "A17_17") (pintype "passive"))
      (node (ref "J12") (pin "17") (pinfunction "A17_17") (pintype "passive"))
      (node (ref "J13") (pin "17") (pinfunction "A17_17") (pintype "passive"))
      (node (ref "J14") (pin "17") (pinfunction "A17_17") (pintype "passive"))
      (node (ref "J15") (pin "17") (pinfunction "A17_17") (pintype "passive"))
      (node (ref "J16") (pin "17") (pinfunction "A17_17") (pintype "passive"))
      (node (ref "J2") (pin "17") (pinfunction "A17_17") (pintype "passive"))
      (node (ref "J3") (pin "17") (pinfunction "A17_17") (pintype "passive"))
      (node (ref "J4") (pin "17") (pinfunction "A17_17") (pintype "passive"))
      (node (ref "J5") (pin "17") (pinfunction "A17_17") (pintype "passive"))
      (node (ref "J6") (pin "17") (pinfunction "A17_17") (pintype "passive"))
      (node (ref "J7") (pin "17") (pinfunction "A17_17") (pintype "passive"))
      (node (ref "J8") (pin "17") (pinfunction "A17_17") (pintype "passive"))
      (node (ref "J9") (pin "17") (pinfunction "A17_17") (pintype "passive"))
      (node (ref "R36") (pin "2") (pinfunction "2_2") (pintype "passive"))
      (node (ref "U2") (pin "7") (pinfunction "C-_7") (pintype "passive"))
    )
    (net (code "175") (name "/bus36") (class "Default")
      (node (ref "P9") (pin "2") (pinfunction "2_2") (pintype "passive"))
      (node (ref "U1") (pin "11") (pinfunction "YD_11") (pintype "passive"))
      (node (ref "U11") (pin "1B9") (pinfunction "M3/L18n_1B9") (pintype "passive"))
    )
    (net (code "176") (name "/bus36_n") (class "Default")
      (node (ref "J1") (pin "78") (pinfunction "B18_78") (pintype "passive"))
      (node (ref "J10") (pin "78") (pinfunction "B18_78") (pintype "passive"))
      (node (ref "J11") (pin "78") (pinfunction "B18_78") (pintype "passive"))
      (node (ref "J12") (pin "78") (pinfunction "B18_78") (pintype "passive"))
      (node (ref "J13") (pin "78") (pinfunction "B18_78") (pintype "passive"))
      (node (ref "J14") (pin "78") (pinfunction "B18_78") (pintype "passive"))
      (node (ref "J15") (pin "78") (pinfunction "B18_78") (pintype "passive"))
      (node (ref "J16") (pin "78") (pinfunction "B18_78") (pintype "passive"))
      (node (ref "J2") (pin "78") (pinfunction "B18_78") (pintype "passive"))
      (node (ref "J3") (pin "78") (pinfunction "B18_78") (pintype "passive"))
      (node (ref "J4") (pin "78") (pinfunction "B18_78") (pintype "passive"))
      (node (ref "J5") (pin "78") (pinfunction "B18_78") (pintype "passive"))
      (node (ref "J6") (pin "78") (pinfunction "B18_78") (pintype "passive"))
      (node (ref "J7") (pin "78") (pinfunction "B18_78") (pintype "passive"))
      (node (ref "J8") (pin "78") (pinfunction "B18_78") (pintype "passive"))
      (node (ref "J9") (pin "78") (pinfunction "B18_78") (pintype "passive"))
      (node (ref "R37") (pin "1") (pinfunction "1_1") (pintype "passive"))
      (node (ref "U1") (pin "10") (pinfunction "D+_10") (pintype "passive"))
    )
    (net (code "177") (name "/bus36_p") (class "Default")
      (node (ref "J1") (pin "77") (pinfunction "B17_77") (pintype "passive"))
      (node (ref "J10") (pin "77") (pinfunction "B17_77") (pintype "passive"))
      (node (ref "J11") (pin "77") (pinfunction "B17_77") (pintype "passive"))
      (node (ref "J12") (pin "77") (pinfunction "B17_77") (pintype "passive"))
      (node (ref "J13") (pin "77") (pinfunction "B17_77") (pintype "passive"))
      (node (ref "J14") (pin "77") (pinfunction "B17_77") (pintype "passive"))
      (node (ref "J15") (pin "77") (pinfunction "B17_77") (pintype "passive"))
      (node (ref "J16") (pin "77") (pinfunction "B17_77") (pintype "passive"))
      (node (ref "J2") (pin "77") (pinfunction "B17_77") (pintype "passive"))
      (node (ref "J3") (pin "77") (pinfunction "B17_77") (pintype "passive"))
      (node (ref "J4") (pin "77") (pinfunction "B17_77") (pintype "passive"))
      (node (ref "J5") (pin "77") (pinfunction "B17_77") (pintype "passive"))
      (node (ref "J6") (pin "77") (pinfunction "B17_77") (pintype "passive"))
      (node (ref "J7") (pin "77") (pinfunction "B17_77") (pintype "passive"))
      (node (ref "J8") (pin "77") (pinfunction "B17_77") (pintype "passive"))
      (node (ref "J9") (pin "77") (pinfunction "B17_77") (pintype "passive"))
      (node (ref "R37") (pin "2") (pinfunction "2_2") (pintype "passive"))
      (node (ref "U1") (pin "9") (pinfunction "D-_9") (pintype "passive"))
    )
    (net (code "178") (name "/bus37") (class "Default")
      (node (ref "P9") (pin "1") (pinfunction "1_1") (pintype "passive"))
      (node (ref "U1") (pin "13") (pinfunction "YB_13") (pintype "passive"))
      (node (ref "U11") (pin "1B8") (pinfunction "W6/B4p_1B8") (pintype "passive"))
    )
    (net (code "179") (name "/bus37_n") (class "Default")
      (node (ref "J1") (pin "79") (pinfunction "B19_79") (pintype "passive"))
      (node (ref "J10") (pin "79") (pinfunction "B19_79") (pintype "passive"))
      (node (ref "J11") (pin "79") (pinfunction "B19_79") (pintype "passive"))
      (node (ref "J12") (pin "79") (pinfunction "B19_79") (pintype "passive"))
      (node (ref "J13") (pin "79") (pinfunction "B19_79") (pintype "passive"))
      (node (ref "J14") (pin "79") (pinfunction "B19_79") (pintype "passive"))
      (node (ref "J15") (pin "79") (pinfunction "B19_79") (pintype "passive"))
      (node (ref "J16") (pin "79") (pinfunction "B19_79") (pintype "passive"))
      (node (ref "J2") (pin "79") (pinfunction "B19_79") (pintype "passive"))
      (node (ref "J3") (pin "79") (pinfunction "B19_79") (pintype "passive"))
      (node (ref "J4") (pin "79") (pinfunction "B19_79") (pintype "passive"))
      (node (ref "J5") (pin "79") (pinfunction "B19_79") (pintype "passive"))
      (node (ref "J6") (pin "79") (pinfunction "B19_79") (pintype "passive"))
      (node (ref "J7") (pin "79") (pinfunction "B19_79") (pintype "passive"))
      (node (ref "J8") (pin "79") (pinfunction "B19_79") (pintype "passive"))
      (node (ref "J9") (pin "79") (pinfunction "B19_79") (pintype "passive"))
      (node (ref "R38") (pin "1") (pinfunction "1_1") (pintype "passive"))
      (node (ref "U1") (pin "14") (pinfunction "B+_14") (pintype "passive"))
    )
    (net (code "180") (name "/bus37_p") (class "Default")
      (node (ref "J1") (pin "80") (pinfunction "B20_80") (pintype "passive"))
      (node (ref "J10") (pin "80") (pinfunction "B20_80") (pintype "passive"))
      (node (ref "J11") (pin "80") (pinfunction "B20_80") (pintype "passive"))
      (node (ref "J12") (pin "80") (pinfunction "B20_80") (pintype "passive"))
      (node (ref "J13") (pin "80") (pinfunction "B20_80") (pintype "passive"))
      (node (ref "J14") (pin "80") (pinfunction "B20_80") (pintype "passive"))
      (node (ref "J15") (pin "80") (pinfunction "B20_80") (pintype "passive"))
      (node (ref "J16") (pin "80") (pinfunction "B20_80") (pintype "passive"))
      (node (ref "J2") (pin "80") (pinfunction "B20_80") (pintype "passive"))
      (node (ref "J3") (pin "80") (pinfunction "B20_80") (pintype "passive"))
      (node (ref "J4") (pin "80") (pinfunction "B20_80") (pintype "passive"))
      (node (ref "J5") (pin "80") (pinfunction "B20_80") (pintype "passive"))
      (node (ref "J6") (pin "80") (pinfunction "B20_80") (pintype "passive"))
      (node (ref "J7") (pin "80") (pinfunction "B20_80") (pintype "passive"))
      (node (ref "J8") (pin "80") (pinfunction "B20_80") (pintype "passive"))
      (node (ref "J9") (pin "80") (pinfunction "B20_80") (pintype "passive"))
      (node (ref "R38") (pin "2") (pinfunction "2_2") (pintype "passive"))
      (node (ref "U1") (pin "15") (pinfunction "B-_15") (pintype "passive"))
    )
    (net (code "181") (name "/bus38") (class "Default")
      (node (ref "P9") (pin "4") (pinfunction "4_4") (pintype "passive"))
      (node (ref "U1") (pin "3") (pinfunction "YA_3") (pintype "passive"))
      (node (ref "U11") (pin "1B11") (pinfunction "N2/L19p_1B11") (pintype "passive"))
    )
    (net (code "182") (name "/bus38_n") (class "Default")
      (node (ref "J1") (pin "74") (pinfunction "B14_74") (pintype "passive"))
      (node (ref "J10") (pin "74") (pinfunction "B14_74") (pintype "passive"))
      (node (ref "J11") (pin "74") (pinfunction "B14_74") (pintype "passive"))
      (node (ref "J12") (pin "74") (pinfunction "B14_74") (pintype "passive"))
      (node (ref "J13") (pin "74") (pinfunction "B14_74") (pintype "passive"))
      (node (ref "J14") (pin "74") (pinfunction "B14_74") (pintype "passive"))
      (node (ref "J15") (pin "74") (pinfunction "B14_74") (pintype "passive"))
      (node (ref "J16") (pin "74") (pinfunction "B14_74") (pintype "passive"))
      (node (ref "J2") (pin "74") (pinfunction "B14_74") (pintype "passive"))
      (node (ref "J3") (pin "74") (pinfunction "B14_74") (pintype "passive"))
      (node (ref "J4") (pin "74") (pinfunction "B14_74") (pintype "passive"))
      (node (ref "J5") (pin "74") (pinfunction "B14_74") (pintype "passive"))
      (node (ref "J6") (pin "74") (pinfunction "B14_74") (pintype "passive"))
      (node (ref "J7") (pin "74") (pinfunction "B14_74") (pintype "passive"))
      (node (ref "J8") (pin "74") (pinfunction "B14_74") (pintype "passive"))
      (node (ref "J9") (pin "74") (pinfunction "B14_74") (pintype "passive"))
      (node (ref "R39") (pin "1") (pinfunction "1_1") (pintype "passive"))
      (node (ref "U1") (pin "2") (pinfunction "A+_2") (pintype "passive"))
    )
    (net (code "183") (name "/bus38_p") (class "Default")
      (node (ref "J1") (pin "73") (pinfunction "B13_73") (pintype "passive"))
      (node (ref "J10") (pin "73") (pinfunction "B13_73") (pintype "passive"))
      (node (ref "J11") (pin "73") (pinfunction "B13_73") (pintype "passive"))
      (node (ref "J12") (pin "73") (pinfunction "B13_73") (pintype "passive"))
      (node (ref "J13") (pin "73") (pinfunction "B13_73") (pintype "passive"))
      (node (ref "J14") (pin "73") (pinfunction "B13_73") (pintype "passive"))
      (node (ref "J15") (pin "73") (pinfunction "B13_73") (pintype "passive"))
      (node (ref "J16") (pin "73") (pinfunction "B13_73") (pintype "passive"))
      (node (ref "J2") (pin "73") (pinfunction "B13_73") (pintype "passive"))
      (node (ref "J3") (pin "73") (pinfunction "B13_73") (pintype "passive"))
      (node (ref "J4") (pin "73") (pinfunction "B13_73") (pintype "passive"))
      (node (ref "J5") (pin "73") (pinfunction "B13_73") (pintype "passive"))
      (node (ref "J6") (pin "73") (pinfunction "B13_73") (pintype "passive"))
      (node (ref "J7") (pin "73") (pinfunction "B13_73") (pintype "passive"))
      (node (ref "J8") (pin "73") (pinfunction "B13_73") (pintype "passive"))
      (node (ref "J9") (pin "73") (pinfunction "B13_73") (pintype "passive"))
      (node (ref "R39") (pin "2") (pinfunction "2_2") (pintype "passive"))
      (node (ref "U1") (pin "1") (pinfunction "A-_1") (pintype "passive"))
    )
    (net (code "184") (name "/bus39") (class "Default")
      (node (ref "P9") (pin "3") (pinfunction "3_3") (pintype "passive"))
      (node (ref "U1") (pin "5") (pinfunction "YC_5") (pintype "passive"))
      (node (ref "U11") (pin "1B10") (pinfunction "V7/B4n_1B10") (pintype "passive"))
    )
    (net (code "185") (name "/bus39_n") (class "Default")
      (node (ref "J1") (pin "75") (pinfunction "B15_75") (pintype "passive"))
      (node (ref "J10") (pin "75") (pinfunction "B15_75") (pintype "passive"))
      (node (ref "J11") (pin "75") (pinfunction "B15_75") (pintype "passive"))
      (node (ref "J12") (pin "75") (pinfunction "B15_75") (pintype "passive"))
      (node (ref "J13") (pin "75") (pinfunction "B15_75") (pintype "passive"))
      (node (ref "J14") (pin "75") (pinfunction "B15_75") (pintype "passive"))
      (node (ref "J15") (pin "75") (pinfunction "B15_75") (pintype "passive"))
      (node (ref "J16") (pin "75") (pinfunction "B15_75") (pintype "passive"))
      (node (ref "J2") (pin "75") (pinfunction "B15_75") (pintype "passive"))
      (node (ref "J3") (pin "75") (pinfunction "B15_75") (pintype "passive"))
      (node (ref "J4") (pin "75") (pinfunction "B15_75") (pintype "passive"))
      (node (ref "J5") (pin "75") (pinfunction "B15_75") (pintype "passive"))
      (node (ref "J6") (pin "75") (pinfunction "B15_75") (pintype "passive"))
      (node (ref "J7") (pin "75") (pinfunction "B15_75") (pintype "passive"))
      (node (ref "J8") (pin "75") (pinfunction "B15_75") (pintype "passive"))
      (node (ref "J9") (pin "75") (pinfunction "B15_75") (pintype "passive"))
      (node (ref "R40") (pin "1") (pinfunction "1_1") (pintype "passive"))
      (node (ref "U1") (pin "6") (pinfunction "C+_6") (pintype "passive"))
    )
    (net (code "186") (name "/bus39_p") (class "Default")
      (node (ref "J1") (pin "76") (pinfunction "B16_76") (pintype "passive"))
      (node (ref "J10") (pin "76") (pinfunction "B16_76") (pintype "passive"))
      (node (ref "J11") (pin "76") (pinfunction "B16_76") (pintype "passive"))
      (node (ref "J12") (pin "76") (pinfunction "B16_76") (pintype "passive"))
      (node (ref "J13") (pin "76") (pinfunction "B16_76") (pintype "passive"))
      (node (ref "J14") (pin "76") (pinfunction "B16_76") (pintype "passive"))
      (node (ref "J15") (pin "76") (pinfunction "B16_76") (pintype "passive"))
      (node (ref "J16") (pin "76") (pinfunction "B16_76") (pintype "passive"))
      (node (ref "J2") (pin "76") (pinfunction "B16_76") (pintype "passive"))
      (node (ref "J3") (pin "76") (pinfunction "B16_76") (pintype "passive"))
      (node (ref "J4") (pin "76") (pinfunction "B16_76") (pintype "passive"))
      (node (ref "J5") (pin "76") (pinfunction "B16_76") (pintype "passive"))
      (node (ref "J6") (pin "76") (pinfunction "B16_76") (pintype "passive"))
      (node (ref "J7") (pin "76") (pinfunction "B16_76") (pintype "passive"))
      (node (ref "J8") (pin "76") (pinfunction "B16_76") (pintype "passive"))
      (node (ref "J9") (pin "76") (pinfunction "B16_76") (pintype "passive"))
      (node (ref "R40") (pin "2") (pinfunction "2_2") (pintype "passive"))
      (node (ref "U1") (pin "7") (pinfunction "C-_7") (pintype "passive"))
    )
    (net (code "187") (name "3.3V_dig") (class "Default")
      (node (ref "C1") (pin "1") (pinfunction "1_1") (pintype "passive"))
      (node (ref "C2") (pin "1") (pinfunction "1_1") (pintype "passive"))
      (node (ref "C39") (pin "1") (pinfunction "1_1") (pintype "passive"))
      (node (ref "C40") (pin "1") (pinfunction "1_1") (pintype "passive"))
      (node (ref "C41") (pin "1") (pinfunction "1_1") (pintype "passive"))
      (node (ref "C42") (pin "1") (pinfunction "1_1") (pintype "passive"))
      (node (ref "C43") (pin "1") (pinfunction "1_1") (pintype "passive"))
      (node (ref "C44") (pin "1") (pinfunction "1_1") (pintype "passive"))
      (node (ref "C45") (pin "1") (pinfunction "1_1") (pintype "passive"))
      (node (ref "C46") (pin "1") (pinfunction "1_1") (pintype "passive"))
      (node (ref "C47") (pin "2") (pinfunction "2_2") (pintype "passive"))
      (node (ref "C48") (pin "2") (pinfunction "2_2") (pintype "passive"))
      (node (ref "C49") (pin "2") (pinfunction "2_2") (pintype "passive"))
      (node (ref "C50") (pin "2") (pinfunction "2_2") (pintype "passive"))
      (node (ref "P7") (pin "2") (pinfunction "2_2") (pintype "passive"))
      (node (ref "P7") (pin "4") (pinfunction "4_4") (pintype "passive"))
      (node (ref "P7") (pin "6") (pinfunction "6_6") (pintype "passive"))
      (node (ref "U1") (pin "12") (pinfunction "ENBD_12") (pintype "passive"))
      (node (ref "U1") (pin "16") (pinfunction "Vcc_16") (pintype "passive"))
      (node (ref "U1") (pin "4") (pinfunction "EAC_4") (pintype "passive"))
      (node (ref "U10") (pin "16") (pinfunction "Vcc_16") (pintype "passive"))
      (node (ref "U10") (pin "4") (pinfunction "EN_4") (pintype "passive"))
      (node (ref "U11") (pin "1A1") (pinfunction "3.3V_1A1") (pintype "passive"))
      (node (ref "U11") (pin "1C1") (pinfunction "3.3V_1C1") (pintype "passive"))
      (node (ref "U12") (pin "5") (pinfunction "DIR_5") (pintype "passive"))
      (node (ref "U12") (pin "6") (pinfunction "VCCB_6") (pintype "passive"))
      (node (ref "U13") (pin "5") (pinfunction "DIR_5") (pintype "passive"))
      (node (ref "U13") (pin "6") (pinfunction "VCCB_6") (pintype "passive"))
      (node (ref "U14") (pin "5") (pinfunction "DIR_5") (pintype "passive"))
      (node (ref "U14") (pin "6") (pinfunction "VCCB_6") (pintype "passive"))
      (node (ref "U15") (pin "5") (pinfunction "DIR_5") (pintype "passive"))
      (node (ref "U15") (pin "6") (pinfunction "VCCB_6") (pintype "passive"))
      (node (ref "U2") (pin "12") (pinfunction "ENBD_12") (pintype "passive"))
      (node (ref "U2") (pin "16") (pinfunction "Vcc_16") (pintype "passive"))
      (node (ref "U2") (pin "4") (pinfunction "EAC_4") (pintype "passive"))
      (node (ref "U3") (pin "16") (pinfunction "Vcc_16") (pintype "passive"))
      (node (ref "U3") (pin "4") (pinfunction "EN_4") (pintype "passive"))
      (node (ref "U4") (pin "16") (pinfunction "Vcc_16") (pintype "passive"))
      (node (ref "U4") (pin "4") (pinfunction "EN_4") (pintype "passive"))
      (node (ref "U5") (pin "16") (pinfunction "Vcc_16") (pintype "passive"))
      (node (ref "U5") (pin "4") (pinfunction "EN_4") (pintype "passive"))
      (node (ref "U6") (pin "16") (pinfunction "Vcc_16") (pintype "passive"))
      (node (ref "U6") (pin "4") (pinfunction "EN_4") (pintype "passive"))
      (node (ref "U7") (pin "16") (pinfunction "Vcc_16") (pintype "passive"))
      (node (ref "U7") (pin "4") (pinfunction "EN_4") (pintype "passive"))
      (node (ref "U8") (pin "16") (pinfunction "Vcc_16") (pintype "passive"))
      (node (ref "U8") (pin "4") (pinfunction "EN_4") (pintype "passive"))
      (node (ref "U9") (pin "16") (pinfunction "Vcc_16") (pintype "passive"))
      (node (ref "U9") (pin "4") (pinfunction "EN_4") (pintype "passive"))
    )
    (net (code "188") (name "5V_ANA_BUS") (class "Default")
      (node (ref "C16") (pin "1") (pinfunction "1_1") (pintype "passive"))
      (node (ref "C18") (pin "1") (pinfunction "1_1") (pintype "passive"))
      (node (ref "C20") (pin "1") (pinfunction "1_1") (pintype "passive"))
      (node (ref "C22") (pin "1") (pinfunction "1_1") (pintype "passive"))
      (node (ref "C25") (pin "2") (pinfunction "2_2") (pintype "passive"))
      (node (ref "C26") (pin "2") (pinfunction "2_2") (pintype "passive"))
      (node (ref "C29") (pin "2") (pinfunction "2_2") (pintype "passive"))
      (node (ref "C30") (pin "2") (pinfunction "2_2") (pintype "passive"))
      (node (ref "C33") (pin "2") (pinfunction "2_2") (pintype "passive"))
      (node (ref "C34") (pin "2") (pinfunction "2_2") (pintype "passive"))
      (node (ref "C37") (pin "2") (pinfunction "2_2") (pintype "passive"))
      (node (ref "C38") (pin "2") (pinfunction "2_2") (pintype "passive"))
      (node (ref "J1") (pin "118") (pinfunction "B58_118") (pintype "passive"))
      (node (ref "J1") (pin "58") (pinfunction "A58_58") (pintype "passive"))
      (node (ref "J10") (pin "118") (pinfunction "B58_118") (pintype "passive"))
      (node (ref "J10") (pin "58") (pinfunction "A58_58") (pintype "passive"))
      (node (ref "J11") (pin "118") (pinfunction "B58_118") (pintype "passive"))
      (node (ref "J11") (pin "58") (pinfunction "A58_58") (pintype "passive"))
      (node (ref "J12") (pin "118") (pinfunction "B58_118") (pintype "passive"))
      (node (ref "J12") (pin "58") (pinfunction "A58_58") (pintype "passive"))
      (node (ref "J13") (pin "118") (pinfunction "B58_118") (pintype "passive"))
      (node (ref "J13") (pin "58") (pinfunction "A58_58") (pintype "passive"))
      (node (ref "J14") (pin "118") (pinfunction "B58_118") (pintype "passive"))
      (node (ref "J14") (pin "58") (pinfunction "A58_58") (pintype "passive"))
      (node (ref "J15") (pin "118") (pinfunction "B58_118") (pintype "passive"))
      (node (ref "J15") (pin "58") (pinfunction "A58_58") (pintype "passive"))
      (node (ref "J16") (pin "118") (pinfunction "B58_118") (pintype "passive"))
      (node (ref "J16") (pin "58") (pinfunction "A58_58") (pintype "passive"))
      (node (ref "J2") (pin "118") (pinfunction "B58_118") (pintype "passive"))
      (node (ref "J2") (pin "58") (pinfunction "A58_58") (pintype "passive"))
      (node (ref "J3") (pin "118") (pinfunction "B58_118") (pintype "passive"))
      (node (ref "J3") (pin "58") (pinfunction "A58_58") (pintype "passive"))
      (node (ref "J4") (pin "118") (pinfunction "B58_118") (pintype "passive"))
      (node (ref "J4") (pin "58") (pinfunction "A58_58") (pintype "passive"))
      (node (ref "J5") (pin "118") (pinfunction "B58_118") (pintype "passive"))
      (node (ref "J5") (pin "58") (pinfunction "A58_58") (pintype "passive"))
      (node (ref "J6") (pin "118") (pinfunction "B58_118") (pintype "passive"))
      (node (ref "J6") (pin "58") (pinfunction "A58_58") (pintype "passive"))
      (node (ref "J7") (pin "118") (pinfunction "B58_118") (pintype "passive"))
      (node (ref "J7") (pin "58") (pinfunction "A58_58") (pintype "passive"))
      (node (ref "J8") (pin "118") (pinfunction "B58_118") (pintype "passive"))
      (node (ref "J8") (pin "58") (pinfunction "A58_58") (pintype "passive"))
      (node (ref "J9") (pin "118") (pinfunction "B58_118") (pintype "passive"))
      (node (ref "J9") (pin "58") (pinfunction "A58_58") (pintype "passive"))
    )
    (net (code "189") (name "5V_DIG_BUS") (class "Default")
      (node (ref "C10") (pin "2") (pinfunction "2_2") (pintype "passive"))
      (node (ref "C11") (pin "2") (pinfunction "2_2") (pintype "passive"))
      (node (ref "C12") (pin "2") (pinfunction "2_2") (pintype "passive"))
      (node (ref "C13") (pin "2") (pinfunction "2_2") (pintype "passive"))
      (node (ref "C14") (pin "2") (pinfunction "2_2") (pintype "passive"))
      (node (ref "C3") (pin "1") (pinfunction "1_1") (pintype "passive"))
      (node (ref "C4") (pin "1") (pinfunction "1_1") (pintype "passive"))
      (node (ref "C5") (pin "1") (pinfunction "1_1") (pintype "passive"))
      (node (ref "C6") (pin "1") (pinfunction "1_1") (pintype "passive"))
      (node (ref "C7") (pin "2") (pinfunction "2_2") (pintype "passive"))
      (node (ref "C8") (pin "2") (pinfunction "2_2") (pintype "passive"))
      (node (ref "C9") (pin "2") (pinfunction "2_2") (pintype "passive"))
      (node (ref "J1") (pin "1") (pinfunction "A1_1") (pintype "passive"))
      (node (ref "J1") (pin "61") (pinfunction "B1_61") (pintype "passive"))
      (node (ref "J10") (pin "1") (pinfunction "A1_1") (pintype "passive"))
      (node (ref "J10") (pin "61") (pinfunction "B1_61") (pintype "passive"))
      (node (ref "J11") (pin "1") (pinfunction "A1_1") (pintype "passive"))
      (node (ref "J11") (pin "61") (pinfunction "B1_61") (pintype "passive"))
      (node (ref "J12") (pin "1") (pinfunction "A1_1") (pintype "passive"))
      (node (ref "J12") (pin "61") (pinfunction "B1_61") (pintype "passive"))
      (node (ref "J13") (pin "1") (pinfunction "A1_1") (pintype "passive"))
      (node (ref "J13") (pin "61") (pinfunction "B1_61") (pintype "passive"))
      (node (ref "J14") (pin "1") (pinfunction "A1_1") (pintype "passive"))
      (node (ref "J14") (pin "61") (pinfunction "B1_61") (pintype "passive"))
      (node (ref "J15") (pin "1") (pinfunction "A1_1") (pintype "passive"))
      (node (ref "J15") (pin "61") (pinfunction "B1_61") (pintype "passive"))
      (node (ref "J16") (pin "1") (pinfunction "A1_1") (pintype "passive"))
      (node (ref "J16") (pin "61") (pinfunction "B1_61") (pintype "passive"))
      (node (ref "J2") (pin "1") (pinfunction "A1_1") (pintype "passive"))
      (node (ref "J2") (pin "61") (pinfunction "B1_61") (pintype "passive"))
      (node (ref "J3") (pin "1") (pinfunction "A1_1") (pintype "passive"))
      (node (ref "J3") (pin "61") (pinfunction "B1_61") (pintype "passive"))
      (node (ref "J4") (pin "1") (pinfunction "A1_1") (pintype "passive"))
      (node (ref "J4") (pin "61") (pinfunction "B1_61") (pintype "passive"))
      (node (ref "J5") (pin "1") (pinfunction "A1_1") (pintype "passive"))
      (node (ref "J5") (pin "61") (pinfunction "B1_61") (pintype "passive"))
      (node (ref "J6") (pin "1") (pinfunction "A1_1") (pintype "passive"))
      (node (ref "J6") (pin "61") (pinfunction "B1_61") (pintype "passive"))
      (node (ref "J7") (pin "1") (pinfunction "A1_1") (pintype "passive"))
      (node (ref "J7") (pin "61") (pinfunction "B1_61") (pintype "passive"))
      (node (ref "J8") (pin "1") (pinfunction "A1_1") (pintype "passive"))
      (node (ref "J8") (pin "61") (pinfunction "B1_61") (pintype "passive"))
      (node (ref "J9") (pin "1") (pinfunction "A1_1") (pintype "passive"))
      (node (ref "J9") (pin "61") (pinfunction "B1_61") (pintype "passive"))
      (node (ref "U12") (pin "1") (pinfunction "VCCA_1") (pintype "passive"))
      (node (ref "U13") (pin "1") (pinfunction "VCCA_1") (pintype "passive"))
      (node (ref "U14") (pin "1") (pinfunction "VCCA_1") (pintype "passive"))
      (node (ref "U15") (pin "1") (pinfunction "VCCA_1") (pintype "passive"))
    )
    (net (code "190") (name "8V_BUS") (class "Default")
      (node (ref "C15") (pin "1") (pinfunction "1_1") (pintype "passive"))
      (node (ref "C17") (pin "1") (pinfunction "1_1") (pintype "passive"))
      (node (ref "C19") (pin "1") (pinfunction "1_1") (pintype "passive"))
      (node (ref "C21") (pin "1") (pinfunction "1_1") (pintype "passive"))
      (node (ref "C23") (pin "2") (pinfunction "2_2") (pintype "passive"))
      (node (ref "C24") (pin "2") (pinfunction "2_2") (pintype "passive"))
      (node (ref "C27") (pin "2") (pinfunction "2_2") (pintype "passive"))
      (node (ref "C28") (pin "2") (pinfunction "2_2") (pintype "passive"))
      (node (ref "C31") (pin "2") (pinfunction "2_2") (pintype "passive"))
      (node (ref "C32") (pin "2") (pinfunction "2_2") (pintype "passive"))
      (node (ref "C35") (pin "2") (pinfunction "2_2") (pintype "passive"))
      (node (ref "C36") (pin "2") (pinfunction "2_2") (pintype "passive"))
      (node (ref "J1") (pin "120") (pinfunction "B60_120") (pintype "passive"))
      (node (ref "J1") (pin "60") (pinfunction "A60_60") (pintype "passive"))
      (node (ref "J10") (pin "120") (pinfunction "B60_120") (pintype "passive"))
      (node (ref "J10") (pin "60") (pinfunction "A60_60") (pintype "passive"))
      (node (ref "J11") (pin "120") (pinfunction "B60_120") (pintype "passive"))
      (node (ref "J11") (pin "60") (pinfunction "A60_60") (pintype "passive"))
      (node (ref "J12") (pin "120") (pinfunction "B60_120") (pintype "passive"))
      (node (ref "J12") (pin "60") (pinfunction "A60_60") (pintype "passive"))
      (node (ref "J13") (pin "120") (pinfunction "B60_120") (pintype "passive"))
      (node (ref "J13") (pin "60") (pinfunction "A60_60") (pintype "passive"))
      (node (ref "J14") (pin "120") (pinfunction "B60_120") (pintype "passive"))
      (node (ref "J14") (pin "60") (pinfunction "A60_60") (pintype "passive"))
      (node (ref "J15") (pin "120") (pinfunction "B60_120") (pintype "passive"))
      (node (ref "J15") (pin "60") (pinfunction "A60_60") (pintype "passive"))
      (node (ref "J16") (pin "120") (pinfunction "B60_120") (pintype "passive"))
      (node (ref "J16") (pin "60") (pinfunction "A60_60") (pintype "passive"))
      (node (ref "J2") (pin "120") (pinfunction "B60_120") (pintype "passive"))
      (node (ref "J2") (pin "60") (pinfunction "A60_60") (pintype "passive"))
      (node (ref "J3") (pin "120") (pinfunction "B60_120") (pintype "passive"))
      (node (ref "J3") (pin "60") (pinfunction "A60_60") (pintype "passive"))
      (node (ref "J4") (pin "120") (pinfunction "B60_120") (pintype "passive"))
      (node (ref "J4") (pin "60") (pinfunction "A60_60") (pintype "passive"))
      (node (ref "J5") (pin "120") (pinfunction "B60_120") (pintype "passive"))
      (node (ref "J5") (pin "60") (pinfunction "A60_60") (pintype "passive"))
      (node (ref "J6") (pin "120") (pinfunction "B60_120") (pintype "passive"))
      (node (ref "J6") (pin "60") (pinfunction "A60_60") (pintype "passive"))
      (node (ref "J7") (pin "120") (pinfunction "B60_120") (pintype "passive"))
      (node (ref "J7") (pin "60") (pinfunction "A60_60") (pintype "passive"))
      (node (ref "J8") (pin "120") (pinfunction "B60_120") (pintype "passive"))
      (node (ref "J8") (pin "60") (pinfunction "A60_60") (pintype "passive"))
      (node (ref "J9") (pin "120") (pinfunction "B60_120") (pintype "passive"))
      (node (ref "J9") (pin "60") (pinfunction "A60_60") (pintype "passive"))
    )
    (net (code "191") (name "AGND") (class "Default")
      (node (ref "C15") (pin "2") (pinfunction "2_2") (pintype "passive"))
      (node (ref "C16") (pin "2") (pinfunction "2_2") (pintype "passive"))
      (node (ref "C17") (pin "2") (pinfunction "2_2") (pintype "passive"))
      (node (ref "C18") (pin "2") (pinfunction "2_2") (pintype "passive"))
      (node (ref "C19") (pin "2") (pinfunction "2_2") (pintype "passive"))
      (node (ref "C20") (pin "2") (pinfunction "2_2") (pintype "passive"))
      (node (ref "C21") (pin "2") (pinfunction "2_2") (pintype "passive"))
      (node (ref "C22") (pin "2") (pinfunction "2_2") (pintype "passive"))
      (node (ref "C23") (pin "1") (pinfunction "1_1") (pintype "passive"))
      (node (ref "C24") (pin "1") (pinfunction "1_1") (pintype "passive"))
      (node (ref "C25") (pin "1") (pinfunction "1_1") (pintype "passive"))
      (node (ref "C26") (pin "1") (pinfunction "1_1") (pintype "passive"))
      (node (ref "C27") (pin "1") (pinfunction "1_1") (pintype "passive"))
      (node (ref "C28") (pin "1") (pinfunction "1_1") (pintype "passive"))
      (node (ref "C29") (pin "1") (pinfunction "1_1") (pintype "passive"))
      (node (ref "C30") (pin "1") (pinfunction "1_1") (pintype "passive"))
      (node (ref "C31") (pin "1") (pinfunction "1_1") (pintype "passive"))
      (node (ref "C32") (pin "1") (pinfunction "1_1") (pintype "passive"))
      (node (ref "C33") (pin "1") (pinfunction "1_1") (pintype "passive"))
      (node (ref "C34") (pin "1") (pinfunction "1_1") (pintype "passive"))
      (node (ref "C35") (pin "1") (pinfunction "1_1") (pintype "passive"))
      (node (ref "C36") (pin "1") (pinfunction "1_1") (pintype "passive"))
      (node (ref "C37") (pin "1") (pinfunction "1_1") (pintype "passive"))
      (node (ref "C38") (pin "1") (pinfunction "1_1") (pintype "passive"))
      (node (ref "J1") (pin "117") (pinfunction "B57_117") (pintype "passive"))
      (node (ref "J1") (pin "119") (pinfunction "B59_119") (pintype "passive"))
      (node (ref "J1") (pin "57") (pinfunction "A57_57") (pintype "passive"))
      (node (ref "J1") (pin "59") (pinfunction "A59_59") (pintype "passive"))
      (node (ref "J10") (pin "117") (pinfunction "B57_117") (pintype "passive"))
      (node (ref "J10") (pin "119") (pinfunction "B59_119") (pintype "passive"))
      (node (ref "J10") (pin "57") (pinfunction "A57_57") (pintype "passive"))
      (node (ref "J10") (pin "59") (pinfunction "A59_59") (pintype "passive"))
      (node (ref "J11") (pin "117") (pinfunction "B57_117") (pintype "passive"))
      (node (ref "J11") (pin "119") (pinfunction "B59_119") (pintype "passive"))
      (node (ref "J11") (pin "57") (pinfunction "A57_57") (pintype "passive"))
      (node (ref "J11") (pin "59") (pinfunction "A59_59") (pintype "passive"))
      (node (ref "J12") (pin "117") (pinfunction "B57_117") (pintype "passive"))
      (node (ref "J12") (pin "119") (pinfunction "B59_119") (pintype "passive"))
      (node (ref "J12") (pin "57") (pinfunction "A57_57") (pintype "passive"))
      (node (ref "J12") (pin "59") (pinfunction "A59_59") (pintype "passive"))
      (node (ref "J13") (pin "117") (pinfunction "B57_117") (pintype "passive"))
      (node (ref "J13") (pin "119") (pinfunction "B59_119") (pintype "passive"))
      (node (ref "J13") (pin "57") (pinfunction "A57_57") (pintype "passive"))
      (node (ref "J13") (pin "59") (pinfunction "A59_59") (pintype "passive"))
      (node (ref "J14") (pin "117") (pinfunction "B57_117") (pintype "passive"))
      (node (ref "J14") (pin "119") (pinfunction "B59_119") (pintype "passive"))
      (node (ref "J14") (pin "57") (pinfunction "A57_57") (pintype "passive"))
      (node (ref "J14") (pin "59") (pinfunction "A59_59") (pintype "passive"))
      (node (ref "J15") (pin "117") (pinfunction "B57_117") (pintype "passive"))
      (node (ref "J15") (pin "119") (pinfunction "B59_119") (pintype "passive"))
      (node (ref "J15") (pin "57") (pinfunction "A57_57") (pintype "passive"))
      (node (ref "J15") (pin "59") (pinfunction "A59_59") (pintype "passive"))
      (node (ref "J16") (pin "117") (pinfunction "B57_117") (pintype "passive"))
      (node (ref "J16") (pin "119") (pinfunction "B59_119") (pintype "passive"))
      (node (ref "J16") (pin "57") (pinfunction "A57_57") (pintype "passive"))
      (node (ref "J16") (pin "59") (pinfunction "A59_59") (pintype "passive"))
      (node (ref "J2") (pin "117") (pinfunction "B57_117") (pintype "passive"))
      (node (ref "J2") (pin "119") (pinfunction "B59_119") (pintype "passive"))
      (node (ref "J2") (pin "57") (pinfunction "A57_57") (pintype "passive"))
      (node (ref "J2") (pin "59") (pinfunction "A59_59") (pintype "passive"))
      (node (ref "J3") (pin "117") (pinfunction "B57_117") (pintype "passive"))
      (node (ref "J3") (pin "119") (pinfunction "B59_119") (pintype "passive"))
      (node (ref "J3") (pin "57") (pinfunction "A57_57") (pintype "passive"))
      (node (ref "J3") (pin "59") (pinfunction "A59_59") (pintype "passive"))
      (node (ref "J4") (pin "117") (pinfunction "B57_117") (pintype "passive"))
      (node (ref "J4") (pin "119") (pinfunction "B59_119") (pintype "passive"))
      (node (ref "J4") (pin "57") (pinfunction "A57_57") (pintype "passive"))
      (node (ref "J4") (pin "59") (pinfunction "A59_59") (pintype "passive"))
      (node (ref "J5") (pin "117") (pinfunction "B57_117") (pintype "passive"))
      (node (ref "J5") (pin "119") (pinfunction "B59_119") (pintype "passive"))
      (node (ref "J5") (pin "57") (pinfunction "A57_57") (pintype "passive"))
      (node (ref "J5") (pin "59") (pinfunction "A59_59") (pintype "passive"))
      (node (ref "J6") (pin "117") (pinfunction "B57_117") (pintype "passive"))
      (node (ref "J6") (pin "119") (pinfunction "B59_119") (pintype "passive"))
      (node (ref "J6") (pin "57") (pinfunction "A57_57") (pintype "passive"))
      (node (ref "J6") (pin "59") (pinfunction "A59_59") (pintype "passive"))
      (node (ref "J7") (pin "117") (pinfunction "B57_117") (pintype "passive"))
      (node (ref "J7") (pin "119") (pinfunction "B59_119") (pintype "passive"))
      (node (ref "J7") (pin "57") (pinfunction "A57_57") (pintype "passive"))
      (node (ref "J7") (pin "59") (pinfunction "A59_59") (pintype "passive"))
      (node (ref "J8") (pin "117") (pinfunction "B57_117") (pintype "passive"))
      (node (ref "J8") (pin "119") (pinfunction "B59_119") (pintype "passive"))
      (node (ref "J8") (pin "57") (pinfunction "A57_57") (pintype "passive"))
      (node (ref "J8") (pin "59") (pinfunction "A59_59") (pintype "passive"))
      (node (ref "J9") (pin "117") (pinfunction "B57_117") (pintype "passive"))
      (node (ref "J9") (pin "119") (pinfunction "B59_119") (pintype "passive"))
      (node (ref "J9") (pin "57") (pinfunction "A57_57") (pintype "passive"))
      (node (ref "J9") (pin "59") (pinfunction "A59_59") (pintype "passive"))
    )
    (net (code "192") (name "DGND") (class "Default")
      (node (ref "C1") (pin "2") (pinfunction "2_2") (pintype "passive"))
      (node (ref "C10") (pin "1") (pinfunction "1_1") (pintype "passive"))
      (node (ref "C11") (pin "1") (pinfunction "1_1") (pintype "passive"))
      (node (ref "C12") (pin "1") (pinfunction "1_1") (pintype "passive"))
      (node (ref "C13") (pin "1") (pinfunction "1_1") (pintype "passive"))
      (node (ref "C14") (pin "1") (pinfunction "1_1") (pintype "passive"))
      (node (ref "C2") (pin "2") (pinfunction "2_2") (pintype "passive"))
      (node (ref "C3") (pin "2") (pinfunction "2_2") (pintype "passive"))
      (node (ref "C39") (pin "2") (pinfunction "2_2") (pintype "passive"))
      (node (ref "C4") (pin "2") (pinfunction "2_2") (pintype "passive"))
      (node (ref "C40") (pin "2") (pinfunction "2_2") (pintype "passive"))
      (node (ref "C41") (pin "2") (pinfunction "2_2") (pintype "passive"))
      (node (ref "C42") (pin "2") (pinfunction "2_2") (pintype "passive"))
      (node (ref "C43") (pin "2") (pinfunction "2_2") (pintype "passive"))
      (node (ref "C44") (pin "2") (pinfunction "2_2") (pintype "passive"))
      (node (ref "C45") (pin "2") (pinfunction "2_2") (pintype "passive"))
      (node (ref "C46") (pin "2") (pinfunction "2_2") (pintype "passive"))
      (node (ref "C47") (pin "1") (pinfunction "1_1") (pintype "passive"))
      (node (ref "C48") (pin "1") (pinfunction "1_1") (pintype "passive"))
      (node (ref "C49") (pin "1") (pinfunction "1_1") (pintype "passive"))
      (node (ref "C5") (pin "2") (pinfunction "2_2") (pintype "passive"))
      (node (ref "C50") (pin "1") (pinfunction "1_1") (pintype "passive"))
      (node (ref "C6") (pin "2") (pinfunction "2_2") (pintype "passive"))
      (node (ref "C7") (pin "1") (pinfunction "1_1") (pintype "passive"))
      (node (ref "C8") (pin "1") (pinfunction "1_1") (pintype "passive"))
      (node (ref "C9") (pin "1") (pinfunction "1_1") (pintype "passive"))
      (node (ref "J1") (pin "10") (pinfunction "A10_10") (pintype "passive"))
      (node (ref "J1") (pin "108") (pinfunction "B48_108") (pintype "passive"))
      (node (ref "J1") (pin "11") (pinfunction "A11_11") (pintype "passive"))
      (node (ref "J1") (pin "12") (pinfunction "A12_12") (pintype "passive"))
      (node (ref "J1") (pin "2") (pinfunction "A2_2") (pintype "passive"))
      (node (ref "J1") (pin "21") (pinfunction "A21_21") (pintype "passive"))
      (node (ref "J1") (pin "3") (pinfunction "A3_3") (pintype "passive"))
      (node (ref "J1") (pin "30") (pinfunction "A30_30") (pintype "passive"))
      (node (ref "J1") (pin "39") (pinfunction "A39_39") (pintype "passive"))
      (node (ref "J1") (pin "4") (pinfunction "A4_4") (pintype "passive"))
      (node (ref "J1") (pin "48") (pinfunction "A48_48") (pintype "passive"))
      (node (ref "J1") (pin "5") (pinfunction "A5_5") (pintype "passive"))
      (node (ref "J1") (pin "6") (pinfunction "A6_6") (pintype "passive"))
      (node (ref "J1") (pin "62") (pinfunction "B2_62") (pintype "passive"))
      (node (ref "J1") (pin "63") (pinfunction "B3_63") (pintype "passive"))
      (node (ref "J1") (pin "64") (pinfunction "B4_64") (pintype "passive"))
      (node (ref "J1") (pin "65") (pinfunction "B5_65") (pintype "passive"))
      (node (ref "J1") (pin "66") (pinfunction "B6_66") (pintype "passive"))
      (node (ref "J1") (pin "67") (pinfunction "B7_67") (pintype "passive"))
      (node (ref "J1") (pin "68") (pinfunction "B8_68") (pintype "passive"))
      (node (ref "J1") (pin "69") (pinfunction "B9_69") (pintype "passive"))
      (node (ref "J1") (pin "7") (pinfunction "A7_7") (pintype "passive"))
      (node (ref "J1") (pin "70") (pinfunction "B10_70") (pintype "passive"))
      (node (ref "J1") (pin "71") (pinfunction "B11_71") (pintype "passive"))
      (node (ref "J1") (pin "72") (pinfunction "B12_72") (pintype "passive"))
      (node (ref "J1") (pin "8") (pinfunction "A8_8") (pintype "passive"))
      (node (ref "J1") (pin "81") (pinfunction "B21_81") (pintype "passive"))
      (node (ref "J1") (pin "9") (pinfunction "A9_9") (pintype "passive"))
      (node (ref "J1") (pin "90") (pinfunction "B30_90") (pintype "passive"))
      (node (ref "J1") (pin "99") (pinfunction "B39_99") (pintype "passive"))
      (node (ref "J10") (pin "10") (pinfunction "A10_10") (pintype "passive"))
      (node (ref "J10") (pin "108") (pinfunction "B48_108") (pintype "passive"))
      (node (ref "J10") (pin "11") (pinfunction "A11_11") (pintype "passive"))
      (node (ref "J10") (pin "12") (pinfunction "A12_12") (pintype "passive"))
      (node (ref "J10") (pin "2") (pinfunction "A2_2") (pintype "passive"))
      (node (ref "J10") (pin "21") (pinfunction "A21_21") (pintype "passive"))
      (node (ref "J10") (pin "3") (pinfunction "A3_3") (pintype "passive"))
      (node (ref "J10") (pin "30") (pinfunction "A30_30") (pintype "passive"))
      (node (ref "J10") (pin "39") (pinfunction "A39_39") (pintype "passive"))
      (node (ref "J10") (pin "4") (pinfunction "A4_4") (pintype "passive"))
      (node (ref "J10") (pin "48") (pinfunction "A48_48") (pintype "passive"))
      (node (ref "J10") (pin "5") (pinfunction "A5_5") (pintype "passive"))
      (node (ref "J10") (pin "6") (pinfunction "A6_6") (pintype "passive"))
      (node (ref "J10") (pin "62") (pinfunction "B2_62") (pintype "passive"))
      (node (ref "J10") (pin "63") (pinfunction "B3_63") (pintype "passive"))
      (node (ref "J10") (pin "64") (pinfunction "B4_64") (pintype "passive"))
      (node (ref "J10") (pin "65") (pinfunction "B5_65") (pintype "passive"))
      (node (ref "J10") (pin "66") (pinfunction "B6_66") (pintype "passive"))
      (node (ref "J10") (pin "67") (pinfunction "B7_67") (pintype "passive"))
      (node (ref "J10") (pin "68") (pinfunction "B8_68") (pintype "passive"))
      (node (ref "J10") (pin "69") (pinfunction "B9_69") (pintype "passive"))
      (node (ref "J10") (pin "7") (pinfunction "A7_7") (pintype "passive"))
      (node (ref "J10") (pin "70") (pinfunction "B10_70") (pintype "passive"))
      (node (ref "J10") (pin "71") (pinfunction "B11_71") (pintype "passive"))
      (node (ref "J10") (pin "72") (pinfunction "B12_72") (pintype "passive"))
      (node (ref "J10") (pin "8") (pinfunction "A8_8") (pintype "passive"))
      (node (ref "J10") (pin "81") (pinfunction "B21_81") (pintype "passive"))
      (node (ref "J10") (pin "9") (pinfunction "A9_9") (pintype "passive"))
      (node (ref "J10") (pin "90") (pinfunction "B30_90") (pintype "passive"))
      (node (ref "J10") (pin "99") (pinfunction "B39_99") (pintype "passive"))
      (node (ref "J11") (pin "10") (pinfunction "A10_10") (pintype "passive"))
      (node (ref "J11") (pin "108") (pinfunction "B48_108") (pintype "passive"))
      (node (ref "J11") (pin "11") (pinfunction "A11_11") (pintype "passive"))
      (node (ref "J11") (pin "12") (pinfunction "A12_12") (pintype "passive"))
      (node (ref "J11") (pin "2") (pinfunction "A2_2") (pintype "passive"))
      (node (ref "J11") (pin "21") (pinfunction "A21_21") (pintype "passive"))
      (node (ref "J11") (pin "3") (pinfunction "A3_3") (pintype "passive"))
      (node (ref "J11") (pin "30") (pinfunction "A30_30") (pintype "passive"))
      (node (ref "J11") (pin "39") (pinfunction "A39_39") (pintype "passive"))
      (node (ref "J11") (pin "4") (pinfunction "A4_4") (pintype "passive"))
      (node (ref "J11") (pin "48") (pinfunction "A48_48") (pintype "passive"))
      (node (ref "J11") (pin "5") (pinfunction "A5_5") (pintype "passive"))
      (node (ref "J11") (pin "6") (pinfunction "A6_6") (pintype "passive"))
      (node (ref "J11") (pin "62") (pinfunction "B2_62") (pintype "passive"))
      (node (ref "J11") (pin "63") (pinfunction "B3_63") (pintype "passive"))
      (node (ref "J11") (pin "64") (pinfunction "B4_64") (pintype "passive"))
      (node (ref "J11") (pin "65") (pinfunction "B5_65") (pintype "passive"))
      (node (ref "J11") (pin "66") (pinfunction "B6_66") (pintype "passive"))
      (node (ref "J11") (pin "67") (pinfunction "B7_67") (pintype "passive"))
      (node (ref "J11") (pin "68") (pinfunction "B8_68") (pintype "passive"))
      (node (ref "J11") (pin "69") (pinfunction "B9_69") (pintype "passive"))
      (node (ref "J11") (pin "7") (pinfunction "A7_7") (pintype "passive"))
      (node (ref "J11") (pin "70") (pinfunction "B10_70") (pintype "passive"))
      (node (ref "J11") (pin "71") (pinfunction "B11_71") (pintype "passive"))
      (node (ref "J11") (pin "72") (pinfunction "B12_72") (pintype "passive"))
      (node (ref "J11") (pin "8") (pinfunction "A8_8") (pintype "passive"))
      (node (ref "J11") (pin "81") (pinfunction "B21_81") (pintype "passive"))
      (node (ref "J11") (pin "9") (pinfunction "A9_9") (pintype "passive"))
      (node (ref "J11") (pin "90") (pinfunction "B30_90") (pintype "passive"))
      (node (ref "J11") (pin "99") (pinfunction "B39_99") (pintype "passive"))
      (node (ref "J12") (pin "10") (pinfunction "A10_10") (pintype "passive"))
      (node (ref "J12") (pin "108") (pinfunction "B48_108") (pintype "passive"))
      (node (ref "J12") (pin "11") (pinfunction "A11_11") (pintype "passive"))
      (node (ref "J12") (pin "12") (pinfunction "A12_12") (pintype "passive"))
      (node (ref "J12") (pin "2") (pinfunction "A2_2") (pintype "passive"))
      (node (ref "J12") (pin "21") (pinfunction "A21_21") (pintype "passive"))
      (node (ref "J12") (pin "3") (pinfunction "A3_3") (pintype "passive"))
      (node (ref "J12") (pin "30") (pinfunction "A30_30") (pintype "passive"))
      (node (ref "J12") (pin "39") (pinfunction "A39_39") (pintype "passive"))
      (node (ref "J12") (pin "4") (pinfunction "A4_4") (pintype "passive"))
      (node (ref "J12") (pin "48") (pinfunction "A48_48") (pintype "passive"))
      (node (ref "J12") (pin "5") (pinfunction "A5_5") (pintype "passive"))
      (node (ref "J12") (pin "6") (pinfunction "A6_6") (pintype "passive"))
      (node (ref "J12") (pin "62") (pinfunction "B2_62") (pintype "passive"))
      (node (ref "J12") (pin "63") (pinfunction "B3_63") (pintype "passive"))
      (node (ref "J12") (pin "64") (pinfunction "B4_64") (pintype "passive"))
      (node (ref "J12") (pin "65") (pinfunction "B5_65") (pintype "passive"))
      (node (ref "J12") (pin "66") (pinfunction "B6_66") (pintype "passive"))
      (node (ref "J12") (pin "67") (pinfunction "B7_67") (pintype "passive"))
      (node (ref "J12") (pin "68") (pinfunction "B8_68") (pintype "passive"))
      (node (ref "J12") (pin "69") (pinfunction "B9_69") (pintype "passive"))
      (node (ref "J12") (pin "7") (pinfunction "A7_7") (pintype "passive"))
      (node (ref "J12") (pin "70") (pinfunction "B10_70") (pintype "passive"))
      (node (ref "J12") (pin "71") (pinfunction "B11_71") (pintype "passive"))
      (node (ref "J12") (pin "72") (pinfunction "B12_72") (pintype "passive"))
      (node (ref "J12") (pin "8") (pinfunction "A8_8") (pintype "passive"))
      (node (ref "J12") (pin "81") (pinfunction "B21_81") (pintype "passive"))
      (node (ref "J12") (pin "9") (pinfunction "A9_9") (pintype "passive"))
      (node (ref "J12") (pin "90") (pinfunction "B30_90") (pintype "passive"))
      (node (ref "J12") (pin "99") (pinfunction "B39_99") (pintype "passive"))
      (node (ref "J13") (pin "10") (pinfunction "A10_10") (pintype "passive"))
      (node (ref "J13") (pin "108") (pinfunction "B48_108") (pintype "passive"))
      (node (ref "J13") (pin "11") (pinfunction "A11_11") (pintype "passive"))
      (node (ref "J13") (pin "12") (pinfunction "A12_12") (pintype "passive"))
      (node (ref "J13") (pin "2") (pinfunction "A2_2") (pintype "passive"))
      (node (ref "J13") (pin "21") (pinfunction "A21_21") (pintype "passive"))
      (node (ref "J13") (pin "3") (pinfunction "A3_3") (pintype "passive"))
      (node (ref "J13") (pin "30") (pinfunction "A30_30") (pintype "passive"))
      (node (ref "J13") (pin "39") (pinfunction "A39_39") (pintype "passive"))
      (node (ref "J13") (pin "4") (pinfunction "A4_4") (pintype "passive"))
      (node (ref "J13") (pin "48") (pinfunction "A48_48") (pintype "passive"))
      (node (ref "J13") (pin "5") (pinfunction "A5_5") (pintype "passive"))
      (node (ref "J13") (pin "6") (pinfunction "A6_6") (pintype "passive"))
      (node (ref "J13") (pin "62") (pinfunction "B2_62") (pintype "passive"))
      (node (ref "J13") (pin "63") (pinfunction "B3_63") (pintype "passive"))
      (node (ref "J13") (pin "64") (pinfunction "B4_64") (pintype "passive"))
      (node (ref "J13") (pin "65") (pinfunction "B5_65") (pintype "passive"))
      (node (ref "J13") (pin "66") (pinfunction "B6_66") (pintype "passive"))
      (node (ref "J13") (pin "67") (pinfunction "B7_67") (pintype "passive"))
      (node (ref "J13") (pin "68") (pinfunction "B8_68") (pintype "passive"))
      (node (ref "J13") (pin "69") (pinfunction "B9_69") (pintype "passive"))
      (node (ref "J13") (pin "7") (pinfunction "A7_7") (pintype "passive"))
      (node (ref "J13") (pin "70") (pinfunction "B10_70") (pintype "passive"))
      (node (ref "J13") (pin "71") (pinfunction "B11_71") (pintype "passive"))
      (node (ref "J13") (pin "72") (pinfunction "B12_72") (pintype "passive"))
      (node (ref "J13") (pin "8") (pinfunction "A8_8") (pintype "passive"))
      (node (ref "J13") (pin "81") (pinfunction "B21_81") (pintype "passive"))
      (node (ref "J13") (pin "9") (pinfunction "A9_9") (pintype "passive"))
      (node (ref "J13") (pin "90") (pinfunction "B30_90") (pintype "passive"))
      (node (ref "J13") (pin "99") (pinfunction "B39_99") (pintype "passive"))
      (node (ref "J14") (pin "10") (pinfunction "A10_10") (pintype "passive"))
      (node (ref "J14") (pin "108") (pinfunction "B48_108") (pintype "passive"))
      (node (ref "J14") (pin "11") (pinfunction "A11_11") (pintype "passive"))
      (node (ref "J14") (pin "12") (pinfunction "A12_12") (pintype "passive"))
      (node (ref "J14") (pin "2") (pinfunction "A2_2") (pintype "passive"))
      (node (ref "J14") (pin "21") (pinfunction "A21_21") (pintype "passive"))
      (node (ref "J14") (pin "3") (pinfunction "A3_3") (pintype "passive"))
      (node (ref "J14") (pin "30") (pinfunction "A30_30") (pintype "passive"))
      (node (ref "J14") (pin "39") (pinfunction "A39_39") (pintype "passive"))
      (node (ref "J14") (pin "4") (pinfunction "A4_4") (pintype "passive"))
      (node (ref "J14") (pin "48") (pinfunction "A48_48") (pintype "passive"))
      (node (ref "J14") (pin "5") (pinfunction "A5_5") (pintype "passive"))
      (node (ref "J14") (pin "6") (pinfunction "A6_6") (pintype "passive"))
      (node (ref "J14") (pin "62") (pinfunction "B2_62") (pintype "passive"))
      (node (ref "J14") (pin "63") (pinfunction "B3_63") (pintype "passive"))
      (node (ref "J14") (pin "64") (pinfunction "B4_64") (pintype "passive"))
      (node (ref "J14") (pin "65") (pinfunction "B5_65") (pintype "passive"))
      (node (ref "J14") (pin "66") (pinfunction "B6_66") (pintype "passive"))
      (node (ref "J14") (pin "67") (pinfunction "B7_67") (pintype "passive"))
      (node (ref "J14") (pin "68") (pinfunction "B8_68") (pintype "passive"))
      (node (ref "J14") (pin "69") (pinfunction "B9_69") (pintype "passive"))
      (node (ref "J14") (pin "7") (pinfunction "A7_7") (pintype "passive"))
      (node (ref "J14") (pin "70") (pinfunction "B10_70") (pintype "passive"))
      (node (ref "J14") (pin "71") (pinfunction "B11_71") (pintype "passive"))
      (node (ref "J14") (pin "72") (pinfunction "B12_72") (pintype "passive"))
      (node (ref "J14") (pin "8") (pinfunction "A8_8") (pintype "passive"))
      (node (ref "J14") (pin "81") (pinfunction "B21_81") (pintype "passive"))
      (node (ref "J14") (pin "9") (pinfunction "A9_9") (pintype "passive"))
      (node (ref "J14") (pin "90") (pinfunction "B30_90") (pintype "passive"))
      (node (ref "J14") (pin "99") (pinfunction "B39_99") (pintype "passive"))
      (node (ref "J15") (pin "10") (pinfunction "A10_10") (pintype "passive"))
      (node (ref "J15") (pin "108") (pinfunction "B48_108") (pintype "passive"))
      (node (ref "J15") (pin "11") (pinfunction "A11_11") (pintype "passive"))
      (node (ref "J15") (pin "12") (pinfunction "A12_12") (pintype "passive"))
      (node (ref "J15") (pin "2") (pinfunction "A2_2") (pintype "passive"))
      (node (ref "J15") (pin "21") (pinfunction "A21_21") (pintype "passive"))
      (node (ref "J15") (pin "3") (pinfunction "A3_3") (pintype "passive"))
      (node (ref "J15") (pin "30") (pinfunction "A30_30") (pintype "passive"))
      (node (ref "J15") (pin "39") (pinfunction "A39_39") (pintype "passive"))
      (node (ref "J15") (pin "4") (pinfunction "A4_4") (pintype "passive"))
      (node (ref "J15") (pin "48") (pinfunction "A48_48") (pintype "passive"))
      (node (ref "J15") (pin "5") (pinfunction "A5_5") (pintype "passive"))
      (node (ref "J15") (pin "6") (pinfunction "A6_6") (pintype "passive"))
      (node (ref "J15") (pin "62") (pinfunction "B2_62") (pintype "passive"))
      (node (ref "J15") (pin "63") (pinfunction "B3_63") (pintype "passive"))
      (node (ref "J15") (pin "64") (pinfunction "B4_64") (pintype "passive"))
      (node (ref "J15") (pin "65") (pinfunction "B5_65") (pintype "passive"))
      (node (ref "J15") (pin "66") (pinfunction "B6_66") (pintype "passive"))
      (node (ref "J15") (pin "67") (pinfunction "B7_67") (pintype "passive"))
      (node (ref "J15") (pin "68") (pinfunction "B8_68") (pintype "passive"))
      (node (ref "J15") (pin "69") (pinfunction "B9_69") (pintype "passive"))
      (node (ref "J15") (pin "7") (pinfunction "A7_7") (pintype "passive"))
      (node (ref "J15") (pin "70") (pinfunction "B10_70") (pintype "passive"))
      (node (ref "J15") (pin "71") (pinfunction "B11_71") (pintype "passive"))
      (node (ref "J15") (pin "72") (pinfunction "B12_72") (pintype "passive"))
      (node (ref "J15") (pin "8") (pinfunction "A8_8") (pintype "passive"))
      (node (ref "J15") (pin "81") (pinfunction "B21_81") (pintype "passive"))
      (node (ref "J15") (pin "9") (pinfunction "A9_9") (pintype "passive"))
      (node (ref "J15") (pin "90") (pinfunction "B30_90") (pintype "passive"))
      (node (ref "J15") (pin "99") (pinfunction "B39_99") (pintype "passive"))
      (node (ref "J16") (pin "10") (pinfunction "A10_10") (pintype "passive"))
      (node (ref "J16") (pin "108") (pinfunction "B48_108") (pintype "passive"))
      (node (ref "J16") (pin "11") (pinfunction "A11_11") (pintype "passive"))
      (node (ref "J16") (pin "12") (pinfunction "A12_12") (pintype "passive"))
      (node (ref "J16") (pin "2") (pinfunction "A2_2") (pintype "passive"))
      (node (ref "J16") (pin "21") (pinfunction "A21_21") (pintype "passive"))
      (node (ref "J16") (pin "3") (pinfunction "A3_3") (pintype "passive"))
      (node (ref "J16") (pin "30") (pinfunction "A30_30") (pintype "passive"))
      (node (ref "J16") (pin "39") (pinfunction "A39_39") (pintype "passive"))
      (node (ref "J16") (pin "4") (pinfunction "A4_4") (pintype "passive"))
      (node (ref "J16") (pin "48") (pinfunction "A48_48") (pintype "passive"))
      (node (ref "J16") (pin "5") (pinfunction "A5_5") (pintype "passive"))
      (node (ref "J16") (pin "6") (pinfunction "A6_6") (pintype "passive"))
      (node (ref "J16") (pin "62") (pinfunction "B2_62") (pintype "passive"))
      (node (ref "J16") (pin "63") (pinfunction "B3_63") (pintype "passive"))
      (node (ref "J16") (pin "64") (pinfunction "B4_64") (pintype "passive"))
      (node (ref "J16") (pin "65") (pinfunction "B5_65") (pintype "passive"))
      (node (ref "J16") (pin "66") (pinfunction "B6_66") (pintype "passive"))
      (node (ref "J16") (pin "67") (pinfunction "B7_67") (pintype "passive"))
      (node (ref "J16") (pin "68") (pinfunction "B8_68") (pintype "passive"))
      (node (ref "J16") (pin "69") (pinfunction "B9_69") (pintype "passive"))
      (node (ref "J16") (pin "7") (pinfunction "A7_7") (pintype "passive"))
      (node (ref "J16") (pin "70") (pinfunction "B10_70") (pintype "passive"))
      (node (ref "J16") (pin "71") (pinfunction "B11_71") (pintype "passive"))
      (node (ref "J16") (pin "72") (pinfunction "B12_72") (pintype "passive"))
      (node (ref "J16") (pin "8") (pinfunction "A8_8") (pintype "passive"))
      (node (ref "J16") (pin "81") (pinfunction "B21_81") (pintype "passive"))
      (node (ref "J16") (pin "9") (pinfunction "A9_9") (pintype "passive"))
      (node (ref "J16") (pin "90") (pinfunction "B30_90") (pintype "passive"))
      (node (ref "J16") (pin "99") (pinfunction "B39_99") (pintype "passive"))
      (node (ref "J2") (pin "10") (pinfunction "A10_10") (pintype "passive"))
      (node (ref "J2") (pin "108") (pinfunction "B48_108") (pintype "passive"))
      (node (ref "J2") (pin "11") (pinfunction "A11_11") (pintype "passive"))
      (node (ref "J2") (pin "12") (pinfunction "A12_12") (pintype "passive"))
      (node (ref "J2") (pin "2") (pinfunction "A2_2") (pintype "passive"))
      (node (ref "J2") (pin "21") (pinfunction "A21_21") (pintype "passive"))
      (node (ref "J2") (pin "3") (pinfunction "A3_3") (pintype "passive"))
      (node (ref "J2") (pin "30") (pinfunction "A30_30") (pintype "passive"))
      (node (ref "J2") (pin "39") (pinfunction "A39_39") (pintype "passive"))
      (node (ref "J2") (pin "4") (pinfunction "A4_4") (pintype "passive"))
      (node (ref "J2") (pin "48") (pinfunction "A48_48") (pintype "passive"))
      (node (ref "J2") (pin "5") (pinfunction "A5_5") (pintype "passive"))
      (node (ref "J2") (pin "6") (pinfunction "A6_6") (pintype "passive"))
      (node (ref "J2") (pin "62") (pinfunction "B2_62") (pintype "passive"))
      (node (ref "J2") (pin "63") (pinfunction "B3_63") (pintype "passive"))
      (node (ref "J2") (pin "64") (pinfunction "B4_64") (pintype "passive"))
      (node (ref "J2") (pin "65") (pinfunction "B5_65") (pintype "passive"))
      (node (ref "J2") (pin "66") (pinfunction "B6_66") (pintype "passive"))
      (node (ref "J2") (pin "67") (pinfunction "B7_67") (pintype "passive"))
      (node (ref "J2") (pin "68") (pinfunction "B8_68") (pintype "passive"))
      (node (ref "J2") (pin "69") (pinfunction "B9_69") (pintype "passive"))
      (node (ref "J2") (pin "7") (pinfunction "A7_7") (pintype "passive"))
      (node (ref "J2") (pin "70") (pinfunction "B10_70") (pintype "passive"))
      (node (ref "J2") (pin "71") (pinfunction "B11_71") (pintype "passive"))
      (node (ref "J2") (pin "72") (pinfunction "B12_72") (pintype "passive"))
      (node (ref "J2") (pin "8") (pinfunction "A8_8") (pintype "passive"))
      (node (ref "J2") (pin "81") (pinfunction "B21_81") (pintype "passive"))
      (node (ref "J2") (pin "9") (pinfunction "A9_9") (pintype "passive"))
      (node (ref "J2") (pin "90") (pinfunction "B30_90") (pintype "passive"))
      (node (ref "J2") (pin "99") (pinfunction "B39_99") (pintype "passive"))
      (node (ref "J3") (pin "10") (pinfunction "A10_10") (pintype "passive"))
      (node (ref "J3") (pin "108") (pinfunction "B48_108") (pintype "passive"))
      (node (ref "J3") (pin "11") (pinfunction "A11_11") (pintype "passive"))
      (node (ref "J3") (pin "12") (pinfunction "A12_12") (pintype "passive"))
      (node (ref "J3") (pin "2") (pinfunction "A2_2") (pintype "passive"))
      (node (ref "J3") (pin "21") (pinfunction "A21_21") (pintype "passive"))
      (node (ref "J3") (pin "3") (pinfunction "A3_3") (pintype "passive"))
      (node (ref "J3") (pin "30") (pinfunction "A30_30") (pintype "passive"))
      (node (ref "J3") (pin "39") (pinfunction "A39_39") (pintype "passive"))
      (node (ref "J3") (pin "4") (pinfunction "A4_4") (pintype "passive"))
      (node (ref "J3") (pin "48") (pinfunction "A48_48") (pintype "passive"))
      (node (ref "J3") (pin "5") (pinfunction "A5_5") (pintype "passive"))
      (node (ref "J3") (pin "6") (pinfunction "A6_6") (pintype "passive"))
      (node (ref "J3") (pin "62") (pinfunction "B2_62") (pintype "passive"))
      (node (ref "J3") (pin "63") (pinfunction "B3_63") (pintype "passive"))
      (node (ref "J3") (pin "64") (pinfunction "B4_64") (pintype "passive"))
      (node (ref "J3") (pin "65") (pinfunction "B5_65") (pintype "passive"))
      (node (ref "J3") (pin "66") (pinfunction "B6_66") (pintype "passive"))
      (node (ref "J3") (pin "67") (pinfunction "B7_67") (pintype "passive"))
      (node (ref "J3") (pin "68") (pinfunction "B8_68") (pintype "passive"))
      (node (ref "J3") (pin "69") (pinfunction "B9_69") (pintype "passive"))
      (node (ref "J3") (pin "7") (pinfunction "A7_7") (pintype "passive"))
      (node (ref "J3") (pin "70") (pinfunction "B10_70") (pintype "passive"))
      (node (ref "J3") (pin "71") (pinfunction "B11_71") (pintype "passive"))
      (node (ref "J3") (pin "72") (pinfunction "B12_72") (pintype "passive"))
      (node (ref "J3") (pin "8") (pinfunction "A8_8") (pintype "passive"))
      (node (ref "J3") (pin "81") (pinfunction "B21_81") (pintype "passive"))
      (node (ref "J3") (pin "9") (pinfunction "A9_9") (pintype "passive"))
      (node (ref "J3") (pin "90") (pinfunction "B30_90") (pintype "passive"))
      (node (ref "J3") (pin "99") (pinfunction "B39_99") (pintype "passive"))
      (node (ref "J4") (pin "10") (pinfunction "A10_10") (pintype "passive"))
      (node (ref "J4") (pin "108") (pinfunction "B48_108") (pintype "passive"))
      (node (ref "J4") (pin "11") (pinfunction "A11_11") (pintype "passive"))
      (node (ref "J4") (pin "12") (pinfunction "A12_12") (pintype "passive"))
      (node (ref "J4") (pin "2") (pinfunction "A2_2") (pintype "passive"))
      (node (ref "J4") (pin "21") (pinfunction "A21_21") (pintype "passive"))
      (node (ref "J4") (pin "3") (pinfunction "A3_3") (pintype "passive"))
      (node (ref "J4") (pin "30") (pinfunction "A30_30") (pintype "passive"))
      (node (ref "J4") (pin "39") (pinfunction "A39_39") (pintype "passive"))
      (node (ref "J4") (pin "4") (pinfunction "A4_4") (pintype "passive"))
      (node (ref "J4") (pin "48") (pinfunction "A48_48") (pintype "passive"))
      (node (ref "J4") (pin "5") (pinfunction "A5_5") (pintype "passive"))
      (node (ref "J4") (pin "6") (pinfunction "A6_6") (pintype "passive"))
      (node (ref "J4") (pin "62") (pinfunction "B2_62") (pintype "passive"))
      (node (ref "J4") (pin "63") (pinfunction "B3_63") (pintype "passive"))
      (node (ref "J4") (pin "64") (pinfunction "B4_64") (pintype "passive"))
      (node (ref "J4") (pin "65") (pinfunction "B5_65") (pintype "passive"))
      (node (ref "J4") (pin "66") (pinfunction "B6_66") (pintype "passive"))
      (node (ref "J4") (pin "67") (pinfunction "B7_67") (pintype "passive"))
      (node (ref "J4") (pin "68") (pinfunction "B8_68") (pintype "passive"))
      (node (ref "J4") (pin "69") (pinfunction "B9_69") (pintype "passive"))
      (node (ref "J4") (pin "7") (pinfunction "A7_7") (pintype "passive"))
      (node (ref "J4") (pin "70") (pinfunction "B10_70") (pintype "passive"))
      (node (ref "J4") (pin "71") (pinfunction "B11_71") (pintype "passive"))
      (node (ref "J4") (pin "72") (pinfunction "B12_72") (pintype "passive"))
      (node (ref "J4") (pin "8") (pinfunction "A8_8") (pintype "passive"))
      (node (ref "J4") (pin "81") (pinfunction "B21_81") (pintype "passive"))
      (node (ref "J4") (pin "9") (pinfunction "A9_9") (pintype "passive"))
      (node (ref "J4") (pin "90") (pinfunction "B30_90") (pintype "passive"))
      (node (ref "J4") (pin "99") (pinfunction "B39_99") (pintype "passive"))
      (node (ref "J5") (pin "10") (pinfunction "A10_10") (pintype "passive"))
      (node (ref "J5") (pin "108") (pinfunction "B48_108") (pintype "passive"))
      (node (ref "J5") (pin "11") (pinfunction "A11_11") (pintype "passive"))
      (node (ref "J5") (pin "12") (pinfunction "A12_12") (pintype "passive"))
      (node (ref "J5") (pin "2") (pinfunction "A2_2") (pintype "passive"))
      (node (ref "J5") (pin "21") (pinfunction "A21_21") (pintype "passive"))
      (node (ref "J5") (pin "3") (pinfunction "A3_3") (pintype "passive"))
      (node (ref "J5") (pin "30") (pinfunction "A30_30") (pintype "passive"))
      (node (ref "J5") (pin "39") (pinfunction "A39_39") (pintype "passive"))
      (node (ref "J5") (pin "4") (pinfunction "A4_4") (pintype "passive"))
      (node (ref "J5") (pin "48") (pinfunction "A48_48") (pintype "passive"))
      (node (ref "J5") (pin "5") (pinfunction "A5_5") (pintype "passive"))
      (node (ref "J5") (pin "6") (pinfunction "A6_6") (pintype "passive"))
      (node (ref "J5") (pin "62") (pinfunction "B2_62") (pintype "passive"))
      (node (ref "J5") (pin "63") (pinfunction "B3_63") (pintype "passive"))
      (node (ref "J5") (pin "64") (pinfunction "B4_64") (pintype "passive"))
      (node (ref "J5") (pin "65") (pinfunction "B5_65") (pintype "passive"))
      (node (ref "J5") (pin "66") (pinfunction "B6_66") (pintype "passive"))
      (node (ref "J5") (pin "67") (pinfunction "B7_67") (pintype "passive"))
      (node (ref "J5") (pin "68") (pinfunction "B8_68") (pintype "passive"))
      (node (ref "J5") (pin "69") (pinfunction "B9_69") (pintype "passive"))
      (node (ref "J5") (pin "7") (pinfunction "A7_7") (pintype "passive"))
      (node (ref "J5") (pin "70") (pinfunction "B10_70") (pintype "passive"))
      (node (ref "J5") (pin "71") (pinfunction "B11_71") (pintype "passive"))
      (node (ref "J5") (pin "72") (pinfunction "B12_72") (pintype "passive"))
      (node (ref "J5") (pin "8") (pinfunction "A8_8") (pintype "passive"))
      (node (ref "J5") (pin "81") (pinfunction "B21_81") (pintype "passive"))
      (node (ref "J5") (pin "9") (pinfunction "A9_9") (pintype "passive"))
      (node (ref "J5") (pin "90") (pinfunction "B30_90") (pintype "passive"))
      (node (ref "J5") (pin "99") (pinfunction "B39_99") (pintype "passive"))
      (node (ref "J6") (pin "10") (pinfunction "A10_10") (pintype "passive"))
      (node (ref "J6") (pin "108") (pinfunction "B48_108") (pintype "passive"))
      (node (ref "J6") (pin "11") (pinfunction "A11_11") (pintype "passive"))
      (node (ref "J6") (pin "12") (pinfunction "A12_12") (pintype "passive"))
      (node (ref "J6") (pin "2") (pinfunction "A2_2") (pintype "passive"))
      (node (ref "J6") (pin "21") (pinfunction "A21_21") (pintype "passive"))
      (node (ref "J6") (pin "3") (pinfunction "A3_3") (pintype "passive"))
      (node (ref "J6") (pin "30") (pinfunction "A30_30") (pintype "passive"))
      (node (ref "J6") (pin "39") (pinfunction "A39_39") (pintype "passive"))
      (node (ref "J6") (pin "4") (pinfunction "A4_4") (pintype "passive"))
      (node (ref "J6") (pin "48") (pinfunction "A48_48") (pintype "passive"))
      (node (ref "J6") (pin "5") (pinfunction "A5_5") (pintype "passive"))
      (node (ref "J6") (pin "6") (pinfunction "A6_6") (pintype "passive"))
      (node (ref "J6") (pin "62") (pinfunction "B2_62") (pintype "passive"))
      (node (ref "J6") (pin "63") (pinfunction "B3_63") (pintype "passive"))
      (node (ref "J6") (pin "64") (pinfunction "B4_64") (pintype "passive"))
      (node (ref "J6") (pin "65") (pinfunction "B5_65") (pintype "passive"))
      (node (ref "J6") (pin "66") (pinfunction "B6_66") (pintype "passive"))
      (node (ref "J6") (pin "67") (pinfunction "B7_67") (pintype "passive"))
      (node (ref "J6") (pin "68") (pinfunction "B8_68") (pintype "passive"))
      (node (ref "J6") (pin "69") (pinfunction "B9_69") (pintype "passive"))
      (node (ref "J6") (pin "7") (pinfunction "A7_7") (pintype "passive"))
      (node (ref "J6") (pin "70") (pinfunction "B10_70") (pintype "passive"))
      (node (ref "J6") (pin "71") (pinfunction "B11_71") (pintype "passive"))
      (node (ref "J6") (pin "72") (pinfunction "B12_72") (pintype "passive"))
      (node (ref "J6") (pin "8") (pinfunction "A8_8") (pintype "passive"))
      (node (ref "J6") (pin "81") (pinfunction "B21_81") (pintype "passive"))
      (node (ref "J6") (pin "9") (pinfunction "A9_9") (pintype "passive"))
      (node (ref "J6") (pin "90") (pinfunction "B30_90") (pintype "passive"))
      (node (ref "J6") (pin "99") (pinfunction "B39_99") (pintype "passive"))
      (node (ref "J7") (pin "10") (pinfunction "A10_10") (pintype "passive"))
      (node (ref "J7") (pin "108") (pinfunction "B48_108") (pintype "passive"))
      (node (ref "J7") (pin "11") (pinfunction "A11_11") (pintype "passive"))
      (node (ref "J7") (pin "12") (pinfunction "A12_12") (pintype "passive"))
      (node (ref "J7") (pin "2") (pinfunction "A2_2") (pintype "passive"))
      (node (ref "J7") (pin "21") (pinfunction "A21_21") (pintype "passive"))
      (node (ref "J7") (pin "3") (pinfunction "A3_3") (pintype "passive"))
      (node (ref "J7") (pin "30") (pinfunction "A30_30") (pintype "passive"))
      (node (ref "J7") (pin "39") (pinfunction "A39_39") (pintype "passive"))
      (node (ref "J7") (pin "4") (pinfunction "A4_4") (pintype "passive"))
      (node (ref "J7") (pin "48") (pinfunction "A48_48") (pintype "passive"))
      (node (ref "J7") (pin "5") (pinfunction "A5_5") (pintype "passive"))
      (node (ref "J7") (pin "6") (pinfunction "A6_6") (pintype "passive"))
      (node (ref "J7") (pin "62") (pinfunction "B2_62") (pintype "passive"))
      (node (ref "J7") (pin "63") (pinfunction "B3_63") (pintype "passive"))
      (node (ref "J7") (pin "64") (pinfunction "B4_64") (pintype "passive"))
      (node (ref "J7") (pin "65") (pinfunction "B5_65") (pintype "passive"))
      (node (ref "J7") (pin "66") (pinfunction "B6_66") (pintype "passive"))
      (node (ref "J7") (pin "67") (pinfunction "B7_67") (pintype "passive"))
      (node (ref "J7") (pin "68") (pinfunction "B8_68") (pintype "passive"))
      (node (ref "J7") (pin "69") (pinfunction "B9_69") (pintype "passive"))
      (node (ref "J7") (pin "7") (pinfunction "A7_7") (pintype "passive"))
      (node (ref "J7") (pin "70") (pinfunction "B10_70") (pintype "passive"))
      (node (ref "J7") (pin "71") (pinfunction "B11_71") (pintype "passive"))
      (node (ref "J7") (pin "72") (pinfunction "B12_72") (pintype "passive"))
      (node (ref "J7") (pin "8") (pinfunction "A8_8") (pintype "passive"))
      (node (ref "J7") (pin "81") (pinfunction "B21_81") (pintype "passive"))
      (node (ref "J7") (pin "9") (pinfunction "A9_9") (pintype "passive"))
      (node (ref "J7") (pin "90") (pinfunction "B30_90") (pintype "passive"))
      (node (ref "J7") (pin "99") (pinfunction "B39_99") (pintype "passive"))
      (node (ref "J8") (pin "10") (pinfunction "A10_10") (pintype "passive"))
      (node (ref "J8") (pin "108") (pinfunction "B48_108") (pintype "passive"))
      (node (ref "J8") (pin "11") (pinfunction "A11_11") (pintype "passive"))
      (node (ref "J8") (pin "12") (pinfunction "A12_12") (pintype "passive"))
      (node (ref "J8") (pin "2") (pinfunction "A2_2") (pintype "passive"))
      (node (ref "J8") (pin "21") (pinfunction "A21_21") (pintype "passive"))
      (node (ref "J8") (pin "3") (pinfunction "A3_3") (pintype "passive"))
      (node (ref "J8") (pin "30") (pinfunction "A30_30") (pintype "passive"))
      (node (ref "J8") (pin "39") (pinfunction "A39_39") (pintype "passive"))
      (node (ref "J8") (pin "4") (pinfunction "A4_4") (pintype "passive"))
      (node (ref "J8") (pin "48") (pinfunction "A48_48") (pintype "passive"))
      (node (ref "J8") (pin "5") (pinfunction "A5_5") (pintype "passive"))
      (node (ref "J8") (pin "6") (pinfunction "A6_6") (pintype "passive"))
      (node (ref "J8") (pin "62") (pinfunction "B2_62") (pintype "passive"))
      (node (ref "J8") (pin "63") (pinfunction "B3_63") (pintype "passive"))
      (node (ref "J8") (pin "64") (pinfunction "B4_64") (pintype "passive"))
      (node (ref "J8") (pin "65") (pinfunction "B5_65") (pintype "passive"))
      (node (ref "J8") (pin "66") (pinfunction "B6_66") (pintype "passive"))
      (node (ref "J8") (pin "67") (pinfunction "B7_67") (pintype "passive"))
      (node (ref "J8") (pin "68") (pinfunction "B8_68") (pintype "passive"))
      (node (ref "J8") (pin "69") (pinfunction "B9_69") (pintype "passive"))
      (node (ref "J8") (pin "7") (pinfunction "A7_7") (pintype "passive"))
      (node (ref "J8") (pin "70") (pinfunction "B10_70") (pintype "passive"))
      (node (ref "J8") (pin "71") (pinfunction "B11_71") (pintype "passive"))
      (node (ref "J8") (pin "72") (pinfunction "B12_72") (pintype "passive"))
      (node (ref "J8") (pin "8") (pinfunction "A8_8") (pintype "passive"))
      (node (ref "J8") (pin "81") (pinfunction "B21_81") (pintype "passive"))
      (node (ref "J8") (pin "9") (pinfunction "A9_9") (pintype "passive"))
      (node (ref "J8") (pin "90") (pinfunction "B30_90") (pintype "passive"))
      (node (ref "J8") (pin "99") (pinfunction "B39_99") (pintype "passive"))
      (node (ref "J9") (pin "10") (pinfunction "A10_10") (pintype "passive"))
      (node (ref "J9") (pin "108") (pinfunction "B48_108") (pintype "passive"))
      (node (ref "J9") (pin "11") (pinfunction "A11_11") (pintype "passive"))
      (node (ref "J9") (pin "12") (pinfunction "A12_12") (pintype "passive"))
      (node (ref "J9") (pin "2") (pinfunction "A2_2") (pintype "passive"))
      (node (ref "J9") (pin "21") (pinfunction "A21_21") (pintype "passive"))
      (node (ref "J9") (pin "3") (pinfunction "A3_3") (pintype "passive"))
      (node (ref "J9") (pin "30") (pinfunction "A30_30") (pintype "passive"))
      (node (ref "J9") (pin "39") (pinfunction "A39_39") (pintype "passive"))
      (node (ref "J9") (pin "4") (pinfunction "A4_4") (pintype "passive"))
      (node (ref "J9") (pin "48") (pinfunction "A48_48") (pintype "passive"))
      (node (ref "J9") (pin "5") (pinfunction "A5_5") (pintype "passive"))
      (node (ref "J9") (pin "6") (pinfunction "A6_6") (pintype "passive"))
      (node (ref "J9") (pin "62") (pinfunction "B2_62") (pintype "passive"))
      (node (ref "J9") (pin "63") (pinfunction "B3_63") (pintype "passive"))
      (node (ref "J9") (pin "64") (pinfunction "B4_64") (pintype "passive"))
      (node (ref "J9") (pin "65") (pinfunction "B5_65") (pintype "passive"))
      (node (ref "J9") (pin "66") (pinfunction "B6_66") (pintype "passive"))
      (node (ref "J9") (pin "67") (pinfunction "B7_67") (pintype "passive"))
      (node (ref "J9") (pin "68") (pinfunction "B8_68") (pintype "passive"))
      (node (ref "J9") (pin "69") (pinfunction "B9_69") (pintype "passive"))
      (node (ref "J9") (pin "7") (pinfunction "A7_7") (pintype "passive"))
      (node (ref "J9") (pin "70") (pinfunction "B10_70") (pintype "passive"))
      (node (ref "J9") (pin "71") (pinfunction "B11_71") (pintype "passive"))
      (node (ref "J9") (pin "72") (pinfunction "B12_72") (pintype "passive"))
      (node (ref "J9") (pin "8") (pinfunction "A8_8") (pintype "passive"))
      (node (ref "J9") (pin "81") (pinfunction "B21_81") (pintype "passive"))
      (node (ref "J9") (pin "9") (pinfunction "A9_9") (pintype "passive"))
      (node (ref "J9") (pin "90") (pinfunction "B30_90") (pintype "passive"))
      (node (ref "J9") (pin "99") (pinfunction "B39_99") (pintype "passive"))
      (node (ref "P1") (pin "2") (pinfunction "Y_2") (pintype "passive"))
      (node (ref "P10") (pin "15") (pinfunction "15_15") (pintype "passive"))
      (node (ref "P10") (pin "38") (pinfunction "38_38") (pintype "passive"))
      (node (ref "P10") (pin "40") (pinfunction "40_40") (pintype "passive"))
      (node (ref "P2") (pin "2") (pinfunction "Y_2") (pintype "passive"))
      (node (ref "P3") (pin "2") (pinfunction "Y_2") (pintype "passive"))
      (node (ref "P4") (pin "2") (pinfunction "Y_2") (pintype "passive"))
      (node (ref "P5") (pin "1") (pinfunction "1_1") (pintype "passive"))
      (node (ref "P5") (pin "40") (pinfunction "40_40") (pintype "passive"))
      (node (ref "P6") (pin "1") (pinfunction "1_1") (pintype "passive"))
      (node (ref "P6") (pin "20") (pinfunction "20_20") (pintype "passive"))
      (node (ref "P7") (pin "1") (pinfunction "1_1") (pintype "passive"))
      (node (ref "P7") (pin "13") (pinfunction "13_13") (pintype "passive"))
      (node (ref "P7") (pin "14") (pinfunction "14_14") (pintype "passive"))
      (node (ref "P7") (pin "36") (pinfunction "36_36") (pintype "passive"))
      (node (ref "P8") (pin "14") (pinfunction "14_14") (pintype "passive"))
      (node (ref "P8") (pin "2") (pinfunction "2_2") (pintype "passive"))
      (node (ref "P8") (pin "35") (pinfunction "35_35") (pintype "passive"))
      (node (ref "P9") (pin "16") (pinfunction "16_16") (pintype "passive"))
      (node (ref "P9") (pin "38") (pinfunction "38_38") (pintype "passive"))
      (node (ref "P9") (pin "40") (pinfunction "40_40") (pintype "passive"))
      (node (ref "R41") (pin "1") (pinfunction "1_1") (pintype "passive"))
      (node (ref "R42") (pin "1") (pinfunction "1_1") (pintype "passive"))
      (node (ref "R43") (pin "1") (pinfunction "1_1") (pintype "passive"))
      (node (ref "R44") (pin "1") (pinfunction "1_1") (pintype "passive"))
      (node (ref "R45") (pin "1") (pinfunction "1_1") (pintype "passive"))
      (node (ref "R46") (pin "1") (pinfunction "1_1") (pintype "passive"))
      (node (ref "R47") (pin "1") (pinfunction "1_1") (pintype "passive"))
      (node (ref "R48") (pin "1") (pinfunction "1_1") (pintype "passive"))
      (node (ref "U1") (pin "8") (pinfunction "GND_8") (pintype "passive"))
      (node (ref "U10") (pin "12") (pinfunction "EN#_12") (pintype "passive"))
      (node (ref "U10") (pin "8") (pinfunction "GND_8") (pintype "passive"))
      (node (ref "U11") (pin "1A2") (pinfunction "GND_1A2") (pintype "passive"))
      (node (ref "U11") (pin "1B2") (pinfunction "GND_1B2") (pintype "passive"))
      (node (ref "U11") (pin "1B39") (pinfunction "GND_1B39") (pintype "passive"))
      (node (ref "U11") (pin "1C2") (pinfunction "GND_1C2") (pintype "passive"))
      (node (ref "U11") (pin "1C39") (pinfunction "GND_1C39") (pintype "passive"))
      (node (ref "U11") (pin "2A2") (pinfunction "GND_2A2") (pintype "passive"))
      (node (ref "U11") (pin "2A39") (pinfunction "GND_2A39") (pintype "passive"))
      (node (ref "U11") (pin "2B2") (pinfunction "GND_2B2") (pintype "passive"))
      (node (ref "U11") (pin "2B39") (pinfunction "GND_2B39") (pintype "passive"))
      (node (ref "U11") (pin "2C2") (pinfunction "GND_2C2") (pintype "passive"))
      (node (ref "U11") (pin "2C39") (pinfunction "GND_2C39") (pintype "passive"))
      (node (ref "U12") (pin "2") (pinfunction "GND_2") (pintype "passive"))
      (node (ref "U13") (pin "2") (pinfunction "GND_2") (pintype "passive"))
      (node (ref "U14") (pin "2") (pinfunction "GND_2") (pintype "passive"))
      (node (ref "U15") (pin "2") (pinfunction "GND_2") (pintype "passive"))
      (node (ref "U2") (pin "8") (pinfunction "GND_8") (pintype "passive"))
      (node (ref "U3") (pin "12") (pinfunction "EN#_12") (pintype "passive"))
      (node (ref "U3") (pin "8") (pinfunction "GND_8") (pintype "passive"))
      (node (ref "U4") (pin "12") (pinfunction "EN#_12") (pintype "passive"))
      (node (ref "U4") (pin "8") (pinfunction "GND_8") (pintype "passive"))
      (node (ref "U5") (pin "12") (pinfunction "EN#_12") (pintype "passive"))
      (node (ref "U5") (pin "8") (pinfunction "GND_8") (pintype "passive"))
      (node (ref "U6") (pin "12") (pinfunction "EN#_12") (pintype "passive"))
      (node (ref "U6") (pin "8") (pinfunction "GND_8") (pintype "passive"))
      (node (ref "U7") (pin "12") (pinfunction "EN#_12") (pintype "passive"))
      (node (ref "U7") (pin "8") (pinfunction "GND_8") (pintype "passive"))
      (node (ref "U8") (pin "12") (pinfunction "EN#_12") (pintype "passive"))
      (node (ref "U8") (pin "8") (pinfunction "GND_8") (pintype "passive"))
      (node (ref "U9") (pin "12") (pinfunction "EN#_12") (pintype "passive"))
      (node (ref "U9") (pin "8") (pinfunction "GND_8") (pintype "passive"))
    )
    (net (code "193") (name "Net-(D1-K)") (class "Default")
      (node (ref "D1") (pin "2") (pinfunction "K_2") (pintype "passive"))
      (node (ref "R41") (pin "2") (pinfunction "2_2") (pintype "passive"))
    )
    (net (code "194") (name "Net-(D2-K)") (class "Default")
      (node (ref "D2") (pin "2") (pinfunction "K_2") (pintype "passive"))
      (node (ref "R42") (pin "2") (pinfunction "2_2") (pintype "passive"))
    )
    (net (code "195") (name "Net-(D3-K)") (class "Default")
      (node (ref "D3") (pin "2") (pinfunction "K_2") (pintype "passive"))
      (node (ref "R43") (pin "2") (pinfunction "2_2") (pintype "passive"))
    )
    (net (code "196") (name "Net-(D4-K)") (class "Default")
      (node (ref "D4") (pin "2") (pinfunction "K_2") (pintype "passive"))
      (node (ref "R44") (pin "2") (pinfunction "2_2") (pintype "passive"))
    )
    (net (code "197") (name "Net-(D5-K)") (class "Default")
      (node (ref "D5") (pin "2") (pinfunction "K_2") (pintype "passive"))
      (node (ref "R45") (pin "2") (pinfunction "2_2") (pintype "passive"))
    )
    (net (code "198") (name "Net-(D6-K)") (class "Default")
      (node (ref "D6") (pin "2") (pinfunction "K_2") (pintype "passive"))
      (node (ref "R46") (pin "2") (pinfunction "2_2") (pintype "passive"))
    )
    (net (code "199") (name "Net-(D7-K)") (class "Default")
      (node (ref "D7") (pin "2") (pinfunction "K_2") (pintype "passive"))
      (node (ref "R47") (pin "2") (pinfunction "2_2") (pintype "passive"))
    )
    (net (code "200") (name "Net-(D8-K)") (class "Default")
      (node (ref "D8") (pin "2") (pinfunction "K_2") (pintype "passive"))
      (node (ref "R48") (pin "2") (pinfunction "2_2") (pintype "passive"))
    )
    (net (code "201") (name "Net-(P1-X)") (class "Default")
      (node (ref "P1") (pin "1") (pinfunction "X_1") (pintype "passive"))
      (node (ref "U12") (pin "3") (pinfunction "A_3") (pintype "passive"))
    )
    (net (code "202") (name "Net-(P2-X)") (class "Default")
      (node (ref "P2") (pin "1") (pinfunction "X_1") (pintype "passive"))
      (node (ref "U13") (pin "3") (pinfunction "A_3") (pintype "passive"))
    )
    (net (code "203") (name "Net-(P3-X)") (class "Default")
      (node (ref "P3") (pin "1") (pinfunction "X_1") (pintype "passive"))
      (node (ref "U14") (pin "3") (pinfunction "A_3") (pintype "passive"))
    )
    (net (code "204") (name "Net-(P4-X)") (class "Default")
      (node (ref "P4") (pin "1") (pinfunction "X_1") (pintype "passive"))
      (node (ref "U15") (pin "3") (pinfunction "A_3") (pintype "passive"))
    )
    (net (code "205") (name "unconnected-(P5-Pad38)") (class "Default")
      (node (ref "P5") (pin "38") (pinfunction "38_38") (pintype "passive"))
    )
    (net (code "206") (name "unconnected-(P5-Pad39)") (class "Default")
      (node (ref "P5") (pin "39") (pinfunction "39_39") (pintype "passive"))
    )
    (net (code "207") (name "unconnected-(P7-Pad3)") (class "Default")
      (node (ref "P7") (pin "3") (pinfunction "3_3") (pintype "passive"))
    )
    (net (code "208") (name "unconnected-(P7-Pad5)") (class "Default")
      (node (ref "P7") (pin "5") (pinfunction "5_5") (pintype "passive"))
    )
    (net (code "209") (name "unconnected-(P7-Pad7)") (class "Default")
      (node (ref "P7") (pin "7") (pinfunction "7_7") (pintype "passive"))
    )
    (net (code "210") (name "unconnected-(P7-Pad8)") (class "Default")
      (node (ref "P7") (pin "8") (pinfunction "8_8") (pintype "passive"))
    )
    (net (code "211") (name "unconnected-(P7-Pad9)") (class "Default")
      (node (ref "P7") (pin "9") (pinfunction "9_9") (pintype "passive"))
    )
    (net (code "212") (name "unconnected-(P7-Pad10)") (class "Default")
      (node (ref "P7") (pin "10") (pinfunction "10_10") (pintype "passive"))
    )
    (net (code "213") (name "unconnected-(P7-Pad12)") (class "Default")
      (node (ref "P7") (pin "12") (pinfunction "12_12") (pintype "passive"))
    )
    (net (code "214") (name "unconnected-(P7-Pad21)") (class "Default")
      (node (ref "P7") (pin "21") (pinfunction "21_21") (pintype "passive"))
    )
    (net (code "215") (name "unconnected-(P7-Pad22)") (class "Default")
      (node (ref "P7") (pin "22") (pinfunction "22_22") (pintype "passive"))
    )
    (net (code "216") (name "unconnected-(P7-Pad23)") (class "Default")
      (node (ref "P7") (pin "23") (pinfunction "23_23") (pintype "passive"))
    )
    (net (code "217") (name "unconnected-(P7-Pad24)") (class "Default")
      (node (ref "P7") (pin "24") (pinfunction "24_24") (pintype "passive"))
    )
    (net (code "218") (name "unconnected-(P7-Pad35)") (class "Default")
      (node (ref "P7") (pin "35") (pinfunction "35_35") (pintype "passive"))
    )
    (net (code "219") (name "unconnected-(P7-Pad37)") (class "Default")
      (node (ref "P7") (pin "37") (pinfunction "37_37") (pintype "passive"))
    )
    (net (code "220") (name "unconnected-(P7-Pad38)") (class "Default")
      (node (ref "P7") (pin "38") (pinfunction "38_38") (pintype "passive"))
    )
    (net (code "221") (name "unconnected-(P7-Pad39)") (class "Default")
      (node (ref "P7") (pin "39") (pinfunction "39_39") (pintype "passive"))
    )
    (net (code "222") (name "unconnected-(P7-Pad40)") (class "Default")
      (node (ref "P7") (pin "40") (pinfunction "40_40") (pintype "passive"))
    )
    (net (code "223") (name "unconnected-(P8-Pad1)") (class "Default")
      (node (ref "P8") (pin "1") (pinfunction "1_1") (pintype "passive"))
    )
    (net (code "224") (name "unconnected-(P8-Pad3)") (class "Default")
      (node (ref "P8") (pin "3") (pinfunction "3_3") (pintype "passive"))
    )
    (net (code "225") (name "unconnected-(P8-Pad4)") (class "Default")
      (node (ref "P8") (pin "4") (pinfunction "4_4") (pintype "passive"))
    )
    (net (code "226") (name "unconnected-(P8-Pad5)") (class "Default")
      (node (ref "P8") (pin "5") (pinfunction "5_5") (pintype "passive"))
    )
    (net (code "227") (name "unconnected-(P8-Pad6)") (class "Default")
      (node (ref "P8") (pin "6") (pinfunction "6_6") (pintype "passive"))
    )
    (net (code "228") (name "unconnected-(P8-Pad7)") (class "Default")
      (node (ref "P8") (pin "7") (pinfunction "7_7") (pintype "passive"))
    )
    (net (code "229") (name "unconnected-(P8-Pad8)") (class "Default")
      (node (ref "P8") (pin "8") (pinfunction "8_8") (pintype "passive"))
    )
    (net (code "230") (name "unconnected-(P8-Pad9)") (class "Default")
      (node (ref "P8") (pin "9") (pinfunction "9_9") (pintype "passive"))
    )
    (net (code "231") (name "unconnected-(P8-Pad10)") (class "Default")
      (node (ref "P8") (pin "10") (pinfunction "10_10") (pintype "passive"))
    )
    (net (code "232") (name "unconnected-(P8-Pad11)") (class "Default")
      (node (ref "P8") (pin "11") (pinfunction "11_11") (pintype "passive"))
    )
    (net (code "233") (name "unconnected-(P8-Pad12)") (class "Default")
      (node (ref "P8") (pin "12") (pinfunction "12_12") (pintype "passive"))
    )
    (net (code "234") (name "unconnected-(P8-Pad13)") (class "Default")
      (node (ref "P8") (pin "13") (pinfunction "13_13") (pintype "passive"))
    )
    (net (code "235") (name "unconnected-(P8-Pad15)") (class "Default")
      (node (ref "P8") (pin "15") (pinfunction "15_15") (pintype "passive"))
    )
    (net (code "236") (name "unconnected-(P8-Pad16)") (class "Default")
      (node (ref "P8") (pin "16") (pinfunction "16_16") (pintype "passive"))
    )
    (net (code "237") (name "unconnected-(P8-Pad17)") (class "Default")
      (node (ref "P8") (pin "17") (pinfunction "17_17") (pintype "passive"))
    )
    (net (code "238") (name "unconnected-(P8-Pad18)") (class "Default")
      (node (ref "P8") (pin "18") (pinfunction "18_18") (pintype "passive"))
    )
    (net (code "239") (name "unconnected-(P8-Pad36)") (class "Default")
      (node (ref "P8") (pin "36") (pinfunction "36_36") (pintype "passive"))
    )
    (net (code "240") (name "unconnected-(P8-Pad39)") (class "Default")
      (node (ref "P8") (pin "39") (pinfunction "39_39") (pintype "passive"))
    )
    (net (code "241") (name "unconnected-(P8-Pad40)") (class "Default")
      (node (ref "P8") (pin "40") (pinfunction "40_40") (pintype "passive"))
    )
    (net (code "242") (name "unconnected-(P9-Pad15)") (class "Default")
      (node (ref "P9") (pin "15") (pinfunction "15_15") (pintype "passive"))
    )
    (net (code "243") (name "unconnected-(P9-Pad27)") (class "Default")
      (node (ref "P9") (pin "27") (pinfunction "27_27") (pintype "passive"))
    )
    (net (code "244") (name "unconnected-(P9-Pad28)") (class "Default")
      (node (ref "P9") (pin "28") (pinfunction "28_28") (pintype "passive"))
    )
    (net (code "245") (name "unconnected-(P9-Pad29)") (class "Default")
      (node (ref "P9") (pin "29") (pinfunction "29_29") (pintype "passive"))
    )
    (net (code "246") (name "unconnected-(P9-Pad30)") (class "Default")
      (node (ref "P9") (pin "30") (pinfunction "30_30") (pintype "passive"))
    )
    (net (code "247") (name "unconnected-(P9-Pad31)") (class "Default")
      (node (ref "P9") (pin "31") (pinfunction "31_31") (pintype "passive"))
    )
    (net (code "248") (name "unconnected-(P9-Pad33)") (class "Default")
      (node (ref "P9") (pin "33") (pinfunction "33_33") (pintype "passive"))
    )
    (net (code "249") (name "unconnected-(P9-Pad35)") (class "Default")
      (node (ref "P9") (pin "35") (pinfunction "35_35") (pintype "passive"))
    )
    (net (code "250") (name "unconnected-(P9-Pad37)") (class "Default")
      (node (ref "P9") (pin "37") (pinfunction "37_37") (pintype "passive"))
    )
    (net (code "251") (name "unconnected-(P9-Pad39)") (class "Default")
      (node (ref "P9") (pin "39") (pinfunction "39_39") (pintype "passive"))
    )
    (net (code "252") (name "unconnected-(P10-Pad16)") (class "Default")
      (node (ref "P10") (pin "16") (pinfunction "16_16") (pintype "passive"))
    )
    (net (code "253") (name "unconnected-(P10-Pad37)") (class "Default")
      (node (ref "P10") (pin "37") (pinfunction "37_37") (pintype "passive"))
    )
    (net (code "254") (name "unconnected-(P10-Pad39)") (class "Default")
      (node (ref "P10") (pin "39") (pinfunction "39_39") (pintype "passive"))
    )
    (net (code "255") (name "unconnected-(U11-1.2V-Pad1A4)") (class "Default")
      (node (ref "U11") (pin "1A4") (pinfunction "1.2V_1A4") (pintype "passive"))
    )
    (net (code "256") (name "unconnected-(U11-1.8V-Pad1A6)") (class "Default")
      (node (ref "U11") (pin "1A6") (pinfunction "1.8V_1A6") (pintype "passive"))
    )
    (net (code "257") (name "unconnected-(U11-2.5V-Pad2A18)") (class "Default")
      (node (ref "U11") (pin "2A18") (pinfunction "2.5V_2A18") (pintype "passive"))
    )
    (net (code "258") (name "unconnected-(U11-3.3V-Pad1B1)") (class "Default")
      (node (ref "U11") (pin "1B1") (pinfunction "3.3V_1B1") (pintype "passive"))
    )
    (net (code "259") (name "unconnected-(U11-3.3V-Pad2A1)") (class "Default")
      (node (ref "U11") (pin "2A1") (pinfunction "3.3V_2A1") (pintype "passive"))
    )
    (net (code "260") (name "unconnected-(U11-3.3V-Pad2B1)") (class "Default")
      (node (ref "U11") (pin "2B1") (pinfunction "3.3V_2B1") (pintype "passive"))
    )
    (net (code "261") (name "unconnected-(U11-3.3V-Pad2C1)") (class "Default")
      (node (ref "U11") (pin "2C1") (pinfunction "3.3V_2C1") (pintype "passive"))
    )
    (net (code "262") (name "unconnected-(U11-AA1{slash}L31n-Pad1B32)") (class "Default")
      (node (ref "U11") (pin "1B32") (pinfunction "AA1/L31n_1B32") (pintype "passive"))
    )
    (net (code "263") (name "unconnected-(U11-AA3{slash}CLKOUT-Pad1A19)") (class "Default")
      (node (ref "U11") (pin "1A19") (pinfunction "AA3/CLKOUT_1A19") (pintype "passive"))
    )
    (net (code "264") (name "unconnected-(U11-AA13{slash}B23p-Pad2A32)") (class "Default")
      (node (ref "U11") (pin "2A32") (pinfunction "AA13/B23p_2A32") (pintype "passive"))
    )
    (net (code "265") (name "unconnected-(U11-AB3{slash}CLKOUT-Pad1A21)") (class "Default")
      (node (ref "U11") (pin "1A21") (pinfunction "AB3/CLKOUT_1A21") (pintype "passive"))
    )
    (net (code "266") (name "unconnected-(U11-AB13{slash}B23n-Pad2A34)") (class "Default")
      (node (ref "U11") (pin "2A34") (pinfunction "AB13/B23n_2A34") (pintype "passive"))
    )
    (net (code "267") (name "unconnected-(U11-AB18{slash}IO-Pad2A30)") (class "Default")
      (node (ref "U11") (pin "2A30") (pinfunction "AB18/IO_2A30") (pintype "passive"))
    )
    (net (code "268") (name "unconnected-(U11-B11{slash}CLKIN-Pad1A13)") (class "Default")
      (node (ref "U11") (pin "1A13") (pinfunction "B11/CLKIN_1A13") (pintype "passive"))
    )
    (net (code "269") (name "unconnected-(U11-B21{slash}R3p-Pad2C23)") (class "Default")
      (node (ref "U11") (pin "2C23") (pinfunction "B21/R3p_2C23") (pintype "passive"))
    )
    (net (code "270") (name "unconnected-(U11-B22{slash}R3n-Pad2C25)") (class "Default")
      (node (ref "U11") (pin "2C25") (pinfunction "B22/R3n_2C25") (pintype "passive"))
    )
    (net (code "271") (name "unconnected-(U11-C20{slash}R2n-Pad2C29)") (class "Default")
      (node (ref "U11") (pin "2C29") (pinfunction "C20/R2n_2C29") (pintype "passive"))
    )
    (net (code "272") (name "unconnected-(U11-C22{slash}R4n-Pad2C21)") (class "Default")
      (node (ref "U11") (pin "2C21") (pinfunction "C22/R4n_2C21") (pintype "passive"))
    )
    (net (code "273") (name "unconnected-(U11-CHARGE_DET-Pad2A17)") (class "Default")
      (node (ref "U11") (pin "2A17") (pinfunction "CHARGE_DET_2A17") (pintype "passive"))
    )
    (net (code "274") (name "unconnected-(U11-D20{slash}R2p-Pad2C27)") (class "Default")
      (node (ref "U11") (pin "2C27") (pinfunction "D20/R2p_2C27") (pintype "passive"))
    )
    (net (code "275") (name "unconnected-(U11-F17{slash}R1n-Pad2C33)") (class "Default")
      (node (ref "U11") (pin "2C33") (pinfunction "F17/R1n_2C33") (pintype "passive"))
    )
    (net (code "276") (name "unconnected-(U11-G17{slash}R1p-Pad2C31)") (class "Default")
      (node (ref "U11") (pin "2C31") (pinfunction "G17/R1p_2C31") (pintype "passive"))
    )
    (net (code "277") (name "unconnected-(U11-GND-Pad1A39)") (class "Default")
      (node (ref "U11") (pin "1A39") (pinfunction "GND_1A39") (pintype "passive"))
    )
    (net (code "278") (name "unconnected-(U11-HSMC_VS0-Pad1A10)") (class "Default")
      (node (ref "U11") (pin "1A10") (pinfunction "HSMC_VS0_1A10") (pintype "passive"))
    )
    (net (code "279") (name "unconnected-(U11-HSMC_VS0-Pad2A10)") (class "Default")
      (node (ref "U11") (pin "2A10") (pinfunction "HSMC_VS0_2A10") (pintype "passive"))
    )
    (net (code "280") (name "unconnected-(U11-HSMC_VS1-Pad1A12)") (class "Default")
      (node (ref "U11") (pin "1A12") (pinfunction "HSMC_VS1_1A12") (pintype "passive"))
    )
    (net (code "281") (name "unconnected-(U11-HSMC_VS1-Pad2A12)") (class "Default")
      (node (ref "U11") (pin "2A12") (pinfunction "HSMC_VS1_2A12") (pintype "passive"))
    )
    (net (code "282") (name "unconnected-(U11-HSMC_VS2-Pad1A14)") (class "Default")
      (node (ref "U11") (pin "1A14") (pinfunction "HSMC_VS2_1A14") (pintype "passive"))
    )
    (net (code "283") (name "unconnected-(U11-HSMC_VS2-Pad2A14)") (class "Default")
      (node (ref "U11") (pin "2A14") (pinfunction "HSMC_VS2_2A14") (pintype "passive"))
    )
    (net (code "284") (name "unconnected-(U11-J17{slash}IO-Pad2C38)") (class "Default")
      (node (ref "U11") (pin "2C38") (pinfunction "J17/IO_2C38") (pintype "passive"))
    )
    (net (code "285") (name "unconnected-(U11-J18{slash}R12n-Pad2C36)") (class "Default")
      (node (ref "U11") (pin "2C36") (pinfunction "J18/R12n_2C36") (pintype "passive"))
    )
    (net (code "286") (name "unconnected-(U11-J19{slash}R10p-Pad2A35)") (class "Default")
      (node (ref "U11") (pin "2A35") (pinfunction "J19/R10p_2A35") (pintype "passive"))
    )
    (net (code "287") (name "unconnected-(U11-J20{slash}R10n-Pad2A37)") (class "Default")
      (node (ref "U11") (pin "2A37") (pinfunction "J20/R10n_2A37") (pintype "passive"))
    )
    (net (code "288") (name "unconnected-(U11-JTAG_TCK-Pad1A25)") (class "Default")
      (node (ref "U11") (pin "1A25") (pinfunction "JTAG_TCK_1A25") (pintype "passive"))
    )
    (net (code "289") (name "unconnected-(U11-JTAG_TCK-Pad2A25)") (class "Default")
      (node (ref "U11") (pin "2A25") (pinfunction "JTAG_TCK_2A25") (pintype "passive"))
    )
    (net (code "290") (name "unconnected-(U11-JTAG_TDI-Pad1A24)") (class "Default")
      (node (ref "U11") (pin "1A24") (pinfunction "JTAG_TDI_1A24") (pintype "passive"))
    )
    (net (code "291") (name "unconnected-(U11-JTAG_TDI-Pad2A24)") (class "Default")
      (node (ref "U11") (pin "2A24") (pinfunction "JTAG_TDI_2A24") (pintype "passive"))
    )
    (net (code "292") (name "unconnected-(U11-JTAG_TDO-Pad1A27)") (class "Default")
      (node (ref "U11") (pin "1A27") (pinfunction "JTAG_TDO_1A27") (pintype "passive"))
    )
    (net (code "293") (name "unconnected-(U11-JTAG_TDO-Pad2A27)") (class "Default")
      (node (ref "U11") (pin "2A27") (pinfunction "JTAG_TDO_2A27") (pintype "passive"))
    )
    (net (code "294") (name "unconnected-(U11-JTAG_TMC-Pad1A22)") (class "Default")
      (node (ref "U11") (pin "1A22") (pinfunction "JTAG_TMC_1A22") (pintype "passive"))
    )
    (net (code "295") (name "unconnected-(U11-JTAG_TMC-Pad2A22)") (class "Default")
      (node (ref "U11") (pin "2A22") (pinfunction "JTAG_TMC_2A22") (pintype "passive"))
    )
    (net (code "296") (name "unconnected-(U11-K21{slash}R16p-Pad2C35)") (class "Default")
      (node (ref "U11") (pin "2C35") (pinfunction "K21/R16p_2C35") (pintype "passive"))
    )
    (net (code "297") (name "unconnected-(U11-K22{slash}R16n-Pad2C37)") (class "Default")
      (node (ref "U11") (pin "2C37") (pinfunction "K22/R16n_2C37") (pintype "passive"))
    )
    (net (code "298") (name "unconnected-(U11-N5{slash}L22n-Pad1C36)") (class "Default")
      (node (ref "U11") (pin "1C36") (pinfunction "N5/L22n_1C36") (pintype "passive"))
    )
    (net (code "299") (name "unconnected-(U11-N7{slash}L30p-Pad1C15)") (class "Default")
      (node (ref "U11") (pin "1C15") (pinfunction "N7/L30p_1C15") (pintype "passive"))
    )
    (net (code "300") (name "unconnected-(U11-N17{slash}R21n-Pad2C26)") (class "Default")
      (node (ref "U11") (pin "2C26") (pinfunction "N17/R21n_2C26") (pintype "passive"))
    )
    (net (code "301") (name "unconnected-(U11-N18{slash}R21p-Pad2C24)") (class "Default")
      (node (ref "U11") (pin "2C24") (pinfunction "N18/R21p_2C24") (pintype "passive"))
    )
    (net (code "302") (name "unconnected-(U11-N20{slash}R22n-Pad2C22)") (class "Default")
      (node (ref "U11") (pin "2C22") (pinfunction "N20/R22n_2C22") (pintype "passive"))
    )
    (net (code "303") (name "unconnected-(U11-OVP_FLAG-Pad1A17)") (class "Default")
      (node (ref "U11") (pin "1A17") (pinfunction "OVP_FLAG_1A17") (pintype "passive"))
    )
    (net (code "304") (name "unconnected-(U11-P5{slash}L26p-Pad1C38)") (class "Default")
      (node (ref "U11") (pin "1C38") (pinfunction "P5/L26p_1C38") (pintype "passive"))
    )
    (net (code "305") (name "unconnected-(U11-P6{slash}L32p-Pad1C19)") (class "Default")
      (node (ref "U11") (pin "1C19") (pinfunction "P6/L32p_1C19") (pintype "passive"))
    )
    (net (code "306") (name "unconnected-(U11-P7{slash}L30n-Pad1C17)") (class "Default")
      (node (ref "U11") (pin "1C17") (pinfunction "P7/L30n_1C17") (pintype "passive"))
    )
    (net (code "307") (name "unconnected-(U11-Pad1A8)") (class "Default")
      (node (ref "U11") (pin "1A8") (pintype "passive"))
    )
    (net (code "308") (name "unconnected-(U11-Pad1A15)") (class "Default")
      (node (ref "U11") (pin "1A15") (pintype "passive"))
    )
    (net (code "309") (name "unconnected-(U11-Pad1A16)") (class "Default")
      (node (ref "U11") (pin "1A16") (pintype "passive"))
    )
    (net (code "310") (name "unconnected-(U11-Pad1A18)") (class "Default")
      (node (ref "U11") (pin "1A18") (pintype "passive"))
    )
    (net (code "311") (name "unconnected-(U11-Pad1A36)") (class "Default")
      (node (ref "U11") (pin "1A36") (pintype "passive"))
    )
    (net (code "312") (name "unconnected-(U11-Pad1A38)") (class "Default")
      (node (ref "U11") (pin "1A38") (pintype "passive"))
    )
    (net (code "313") (name "unconnected-(U11-R4{slash}L27p-Pad1C3)") (class "Default")
      (node (ref "U11") (pin "1C3") (pinfunction "R4/L27p_1C3") (pintype "passive"))
    )
    (net (code "314") (name "unconnected-(U11-R5{slash}L32n-Pad1C21)") (class "Default")
      (node (ref "U11") (pin "1C21") (pinfunction "R5/L32n_1C21") (pintype "passive"))
    )
    (net (code "315") (name "unconnected-(U11-R6{slash}L33n-Pad1C37)") (class "Default")
      (node (ref "U11") (pin "1C37") (pinfunction "R6/L33n_1C37") (pintype "passive"))
    )
    (net (code "316") (name "unconnected-(U11-R14{slash}B41p-Pad2C28)") (class "Default")
      (node (ref "U11") (pin "2C28") (pinfunction "R14/B41p_2C28") (pintype "passive"))
    )
    (net (code "317") (name "unconnected-(U11-R15{slash}B41n-Pad2C30)") (class "Default")
      (node (ref "U11") (pin "2C30") (pinfunction "R15/B41n_2C30") (pintype "passive"))
    )
    (net (code "318") (name "unconnected-(U11-R16{slash}IO{slash}CLKOUT-Pad2A21)") (class "Default")
      (node (ref "U11") (pin "2A21") (pinfunction "R16/IO/CLKOUT_2A21") (pintype "passive"))
    )
    (net (code "319") (name "unconnected-(U11-R17{slash}R30n-Pad1C22)") (class "Default")
      (node (ref "U11") (pin "1C22") (pinfunction "R17/R30n_1C22") (pintype "passive"))
    )
    (net (code "320") (name "unconnected-(U11-R18{slash}R26n-Pad1B33)") (class "Default")
      (node (ref "U11") (pin "1B33") (pinfunction "R18/R26n_1B33") (pintype "passive"))
    )
    (net (code "321") (name "unconnected-(U11-T5{slash}L33p-Pad1C35)") (class "Default")
      (node (ref "U11") (pin "1C35") (pinfunction "T5/L33p_1C35") (pintype "passive"))
    )
    (net (code "322") (name "unconnected-(U11-T10{slash}B13p-Pad1B36)") (class "Default")
      (node (ref "U11") (pin "1B36") (pinfunction "T10/B13p_1B36") (pintype "passive"))
    )
    (net (code "323") (name "unconnected-(U11-T11{slash}B13n-Pad1B38)") (class "Default")
      (node (ref "U11") (pin "1B38") (pinfunction "T11/B13n_1B38") (pintype "passive"))
    )
    (net (code "324") (name "unconnected-(U11-T16{slash}IO{slash}CLKOUT-Pad2A19)") (class "Default")
      (node (ref "U11") (pin "2A19") (pinfunction "T16/IO/CLKOUT_2A19") (pintype "passive"))
    )
    (net (code "325") (name "unconnected-(U11-T19{slash}R31p-Pad1C24)") (class "Default")
      (node (ref "U11") (pin "1C24") (pinfunction "T19/R31p_1C24") (pintype "passive"))
    )
    (net (code "326") (name "unconnected-(U11-T20{slash}R31n-Pad1C26)") (class "Default")
      (node (ref "U11") (pin "1C26") (pinfunction "T20/R31n_1C26") (pintype "passive"))
    )
    (net (code "327") (name "unconnected-(U11-T21{slash}CLKIN-Pad1A26)") (class "Default")
      (node (ref "U11") (pin "1A26") (pinfunction "T21/CLKIN_1A26") (pintype "passive"))
    )
    (net (code "328") (name "unconnected-(U11-T22{slash}CLKIN-Pad2A26)") (class "Default")
      (node (ref "U11") (pin "2A26") (pinfunction "T22/CLKIN_2A26") (pintype "passive"))
    )
    (net (code "329") (name "unconnected-(U11-U11{slash}B19p-Pad1C12)") (class "Default")
      (node (ref "U11") (pin "1C12") (pinfunction "U11/B19p_1C12") (pintype "passive"))
    )
    (net (code "330") (name "unconnected-(U11-U12{slash}B28p-Pad2A31)") (class "Default")
      (node (ref "U11") (pin "2A31") (pinfunction "U12/B28p_2A31") (pintype "passive"))
    )
    (net (code "331") (name "unconnected-(U11-U13{slash}B32p-Pad2A28)") (class "Default")
      (node (ref "U11") (pin "2A28") (pinfunction "U13/B32p_2A28") (pintype "passive"))
    )
    (net (code "332") (name "unconnected-(U11-U15{slash}B34p-Pad2C32)") (class "Default")
      (node (ref "U11") (pin "2C32") (pinfunction "U15/B34p_2C32") (pintype "passive"))
    )
    (net (code "333") (name "unconnected-(U11-U19{slash}R34p-Pad1C23)") (class "Default")
      (node (ref "U11") (pin "1C23") (pinfunction "U19/R34p_1C23") (pintype "passive"))
    )
    (net (code "334") (name "unconnected-(U11-U20{slash}R34n-Pad1C25)") (class "Default")
      (node (ref "U11") (pin "1C25") (pinfunction "U20/R34n_1C25") (pintype "passive"))
    )
    (net (code "335") (name "unconnected-(U11-U21{slash}R27p-Pad1C32)") (class "Default")
      (node (ref "U11") (pin "1C32") (pinfunction "U21/R27p_1C32") (pintype "passive"))
    )
    (net (code "336") (name "unconnected-(U11-U22{slash}R27n-Pad1C34)") (class "Default")
      (node (ref "U11") (pin "1C34") (pinfunction "U22/R27n_1C34") (pintype "passive"))
    )
    (net (code "337") (name "unconnected-(U11-V1{slash}L25n-Pad1B37)") (class "Default")
      (node (ref "U11") (pin "1B37") (pinfunction "V1/L25n_1B37") (pintype "passive"))
    )
    (net (code "338") (name "unconnected-(U11-V2{slash}L25p-Pad1B35)") (class "Default")
      (node (ref "U11") (pin "1B35") (pinfunction "V2/L25p_1B35") (pintype "passive"))
    )
    (net (code "339") (name "unconnected-(U11-V11{slash}B19n-Pad1C14)") (class "Default")
      (node (ref "U11") (pin "1C14") (pinfunction "V11/B19n_1C14") (pintype "passive"))
    )
    (net (code "340") (name "unconnected-(U11-V13{slash}B31p-Pad2A29)") (class "Default")
      (node (ref "U11") (pin "2A29") (pinfunction "V13/B31p_2A29") (pintype "passive"))
    )
    (net (code "341") (name "unconnected-(U11-V15{slash}B43n-Pad2C34)") (class "Default")
      (node (ref "U11") (pin "2C34") (pinfunction "V15/B43n_2C34") (pintype "passive"))
    )
    (net (code "342") (name "unconnected-(U11-V21{slash}R29p-Pad1C28)") (class "Default")
      (node (ref "U11") (pin "1C28") (pinfunction "V21/R29p_1C28") (pintype "passive"))
    )
    (net (code "343") (name "unconnected-(U11-V22{slash}R29n-Pad1C30)") (class "Default")
      (node (ref "U11") (pin "1C30") (pinfunction "V22/R29n_1C30") (pintype "passive"))
    )
    (net (code "344") (name "unconnected-(U11-VCCIO-Pad1A3)") (class "Default")
      (node (ref "U11") (pin "1A3") (pinfunction "VCCIO_1A3") (pintype "passive"))
    )
    (net (code "345") (name "unconnected-(U11-VCCIO-Pad1A5)") (class "Default")
      (node (ref "U11") (pin "1A5") (pinfunction "VCCIO_1A5") (pintype "passive"))
    )
    (net (code "346") (name "unconnected-(U11-VCCIO-Pad1A40)") (class "Default")
      (node (ref "U11") (pin "1A40") (pinfunction "VCCIO_1A40") (pintype "passive"))
    )
    (net (code "347") (name "unconnected-(U11-VCCIO-Pad1B40)") (class "Default")
      (node (ref "U11") (pin "1B40") (pinfunction "VCCIO_1B40") (pintype "passive"))
    )
    (net (code "348") (name "unconnected-(U11-VCCIO-Pad1C40)") (class "Default")
      (node (ref "U11") (pin "1C40") (pinfunction "VCCIO_1C40") (pintype "passive"))
    )
    (net (code "349") (name "unconnected-(U11-VCCIO-Pad2A7)") (class "Default")
      (node (ref "U11") (pin "2A7") (pinfunction "VCCIO_2A7") (pintype "passive"))
    )
    (net (code "350") (name "unconnected-(U11-VCCIO-Pad2A9)") (class "Default")
      (node (ref "U11") (pin "2A9") (pinfunction "VCCIO_2A9") (pintype "passive"))
    )
    (net (code "351") (name "unconnected-(U11-VCCIO-Pad2A11)") (class "Default")
      (node (ref "U11") (pin "2A11") (pinfunction "VCCIO_2A11") (pintype "passive"))
    )
    (net (code "352") (name "unconnected-(U11-VCCIO-Pad2A40)") (class "Default")
      (node (ref "U11") (pin "2A40") (pinfunction "VCCIO_2A40") (pintype "passive"))
    )
    (net (code "353") (name "unconnected-(U11-VCCIO-Pad2B40)") (class "Default")
      (node (ref "U11") (pin "2B40") (pinfunction "VCCIO_2B40") (pintype "passive"))
    )
    (net (code "354") (name "unconnected-(U11-VCCIO-Pad2C40)") (class "Default")
      (node (ref "U11") (pin "2C40") (pinfunction "VCCIO_2C40") (pintype "passive"))
    )
    (net (code "355") (name "unconnected-(U11-VDC-Pad2A3)") (class "Default")
      (node (ref "U11") (pin "2A3") (pinfunction "VDC_2A3") (pintype "passive"))
    )
    (net (code "356") (name "unconnected-(U11-VDC-Pad2A5)") (class "Default")
      (node (ref "U11") (pin "2A5") (pinfunction "VDC_2A5") (pintype "passive"))
    )
    (net (code "357") (name "unconnected-(U11-VREF-Pad1A7)") (class "Default")
      (node (ref "U11") (pin "1A7") (pinfunction "VREF_1A7") (pintype "passive"))
    )
    (net (code "358") (name "unconnected-(U11-VREF-Pad1A9)") (class "Default")
      (node (ref "U11") (pin "1A9") (pinfunction "VREF_1A9") (pintype "passive"))
    )
    (net (code "359") (name "unconnected-(U11-VREF-Pad2A13)") (class "Default")
      (node (ref "U11") (pin "2A13") (pinfunction "VREF_2A13") (pintype "passive"))
    )
    (net (code "360") (name "unconnected-(U11-VREF-Pad2A15)") (class "Default")
      (node (ref "U11") (pin "2A15") (pinfunction "VREF_2A15") (pintype "passive"))
    )
    (net (code "361") (name "unconnected-(U11-VREF-Pad2A16)") (class "Default")
      (node (ref "U11") (pin "2A16") (pinfunction "VREF_2A16") (pintype "passive"))
    )
    (net (code "362") (name "unconnected-(U11-W15{slash}B35p-Pad2A33)") (class "Default")
      (node (ref "U11") (pin "2A33") (pinfunction "W15/B35p_2A33") (pintype "passive"))
    )
    (net (code "363") (name "unconnected-(U11-W21{slash}R32p-Pad1C31)") (class "Default")
      (node (ref "U11") (pin "1C31") (pinfunction "W21/R32p_1C31") (pintype "passive"))
    )
    (net (code "364") (name "unconnected-(U11-W22{slash}R32n-Pad1C33)") (class "Default")
      (node (ref "U11") (pin "1C33") (pinfunction "W22/R32n_1C33") (pintype "passive"))
    )
    (net (code "365") (name "unconnected-(U11-Y1{slash}L29n-Pad1C13)") (class "Default")
      (node (ref "U11") (pin "1C13") (pinfunction "Y1/L29n_1C13") (pintype "passive"))
    )
    (net (code "366") (name "unconnected-(U11-Y4{slash}B3p-Pad2A23)") (class "Default")
      (node (ref "U11") (pin "2A23") (pinfunction "Y4/B3p_2A23") (pintype "passive"))
    )
    (net (code "367") (name "unconnected-(U11-Y8{slash}B11p-Pad1B34)") (class "Default")
      (node (ref "U11") (pin "1B34") (pinfunction "Y8/B11p_1B34") (pintype "passive"))
    )
    (net (code "368") (name "unconnected-(U11-Y21{slash}R35p-Pad1C27)") (class "Default")
      (node (ref "U11") (pin "1C27") (pinfunction "Y21/R35p_1C27") (pintype "passive"))
    )
    (net (code "369") (name "unconnected-(U11-Y22{slash}R35n-Pad1C29)") (class "Default")
      (node (ref "U11") (pin "1C29") (pinfunction "Y22/R35n_1C29") (pintype "passive"))
    )
    (net (code "370") (name "unconnected-(U11-n{slash}c-Pad2A4)") (class "Default")
      (node (ref "U11") (pin "2A4") (pinfunction "n/c_2A4") (pintype "passive"))
    )
    (net (code "371") (name "unconnected-(U11-n{slash}c-Pad2A6)") (class "Default")
      (node (ref "U11") (pin "2A6") (pinfunction "n/c_2A6") (pintype "passive"))
    )
    (net (code "372") (name "unconnected-(U11-n{slash}c-Pad2A8)") (class "Default")
      (node (ref "U11") (pin "2A8") (pinfunction "n/c_2A8") (pintype "passive"))
    )
    (net (code "373") (name "unconnected-(U11-n{slash}c-Pad2A20)") (class "Default")
      (node (ref "U11") (pin "2A20") (pinfunction "n/c_2A20") (pintype "passive"))
    )
    (net (code "374") (name "unconnected-(U11-n{slash}c-Pad2A36)") (class "Default")
      (node (ref "U11") (pin "2A36") (pinfunction "n/c_2A36") (pintype "passive"))
    )
    (net (code "375") (name "unconnected-(U11-n{slash}c-Pad2A38)") (class "Default")
      (node (ref "U11") (pin "2A38") (pinfunction "n/c_2A38") (pintype "passive"))
    )
  )
)
